# ProPrj_ZYNQ7020_V1_2024-12-31.net
KiCad netlist of a schematic drawn in EasyEDA Pro
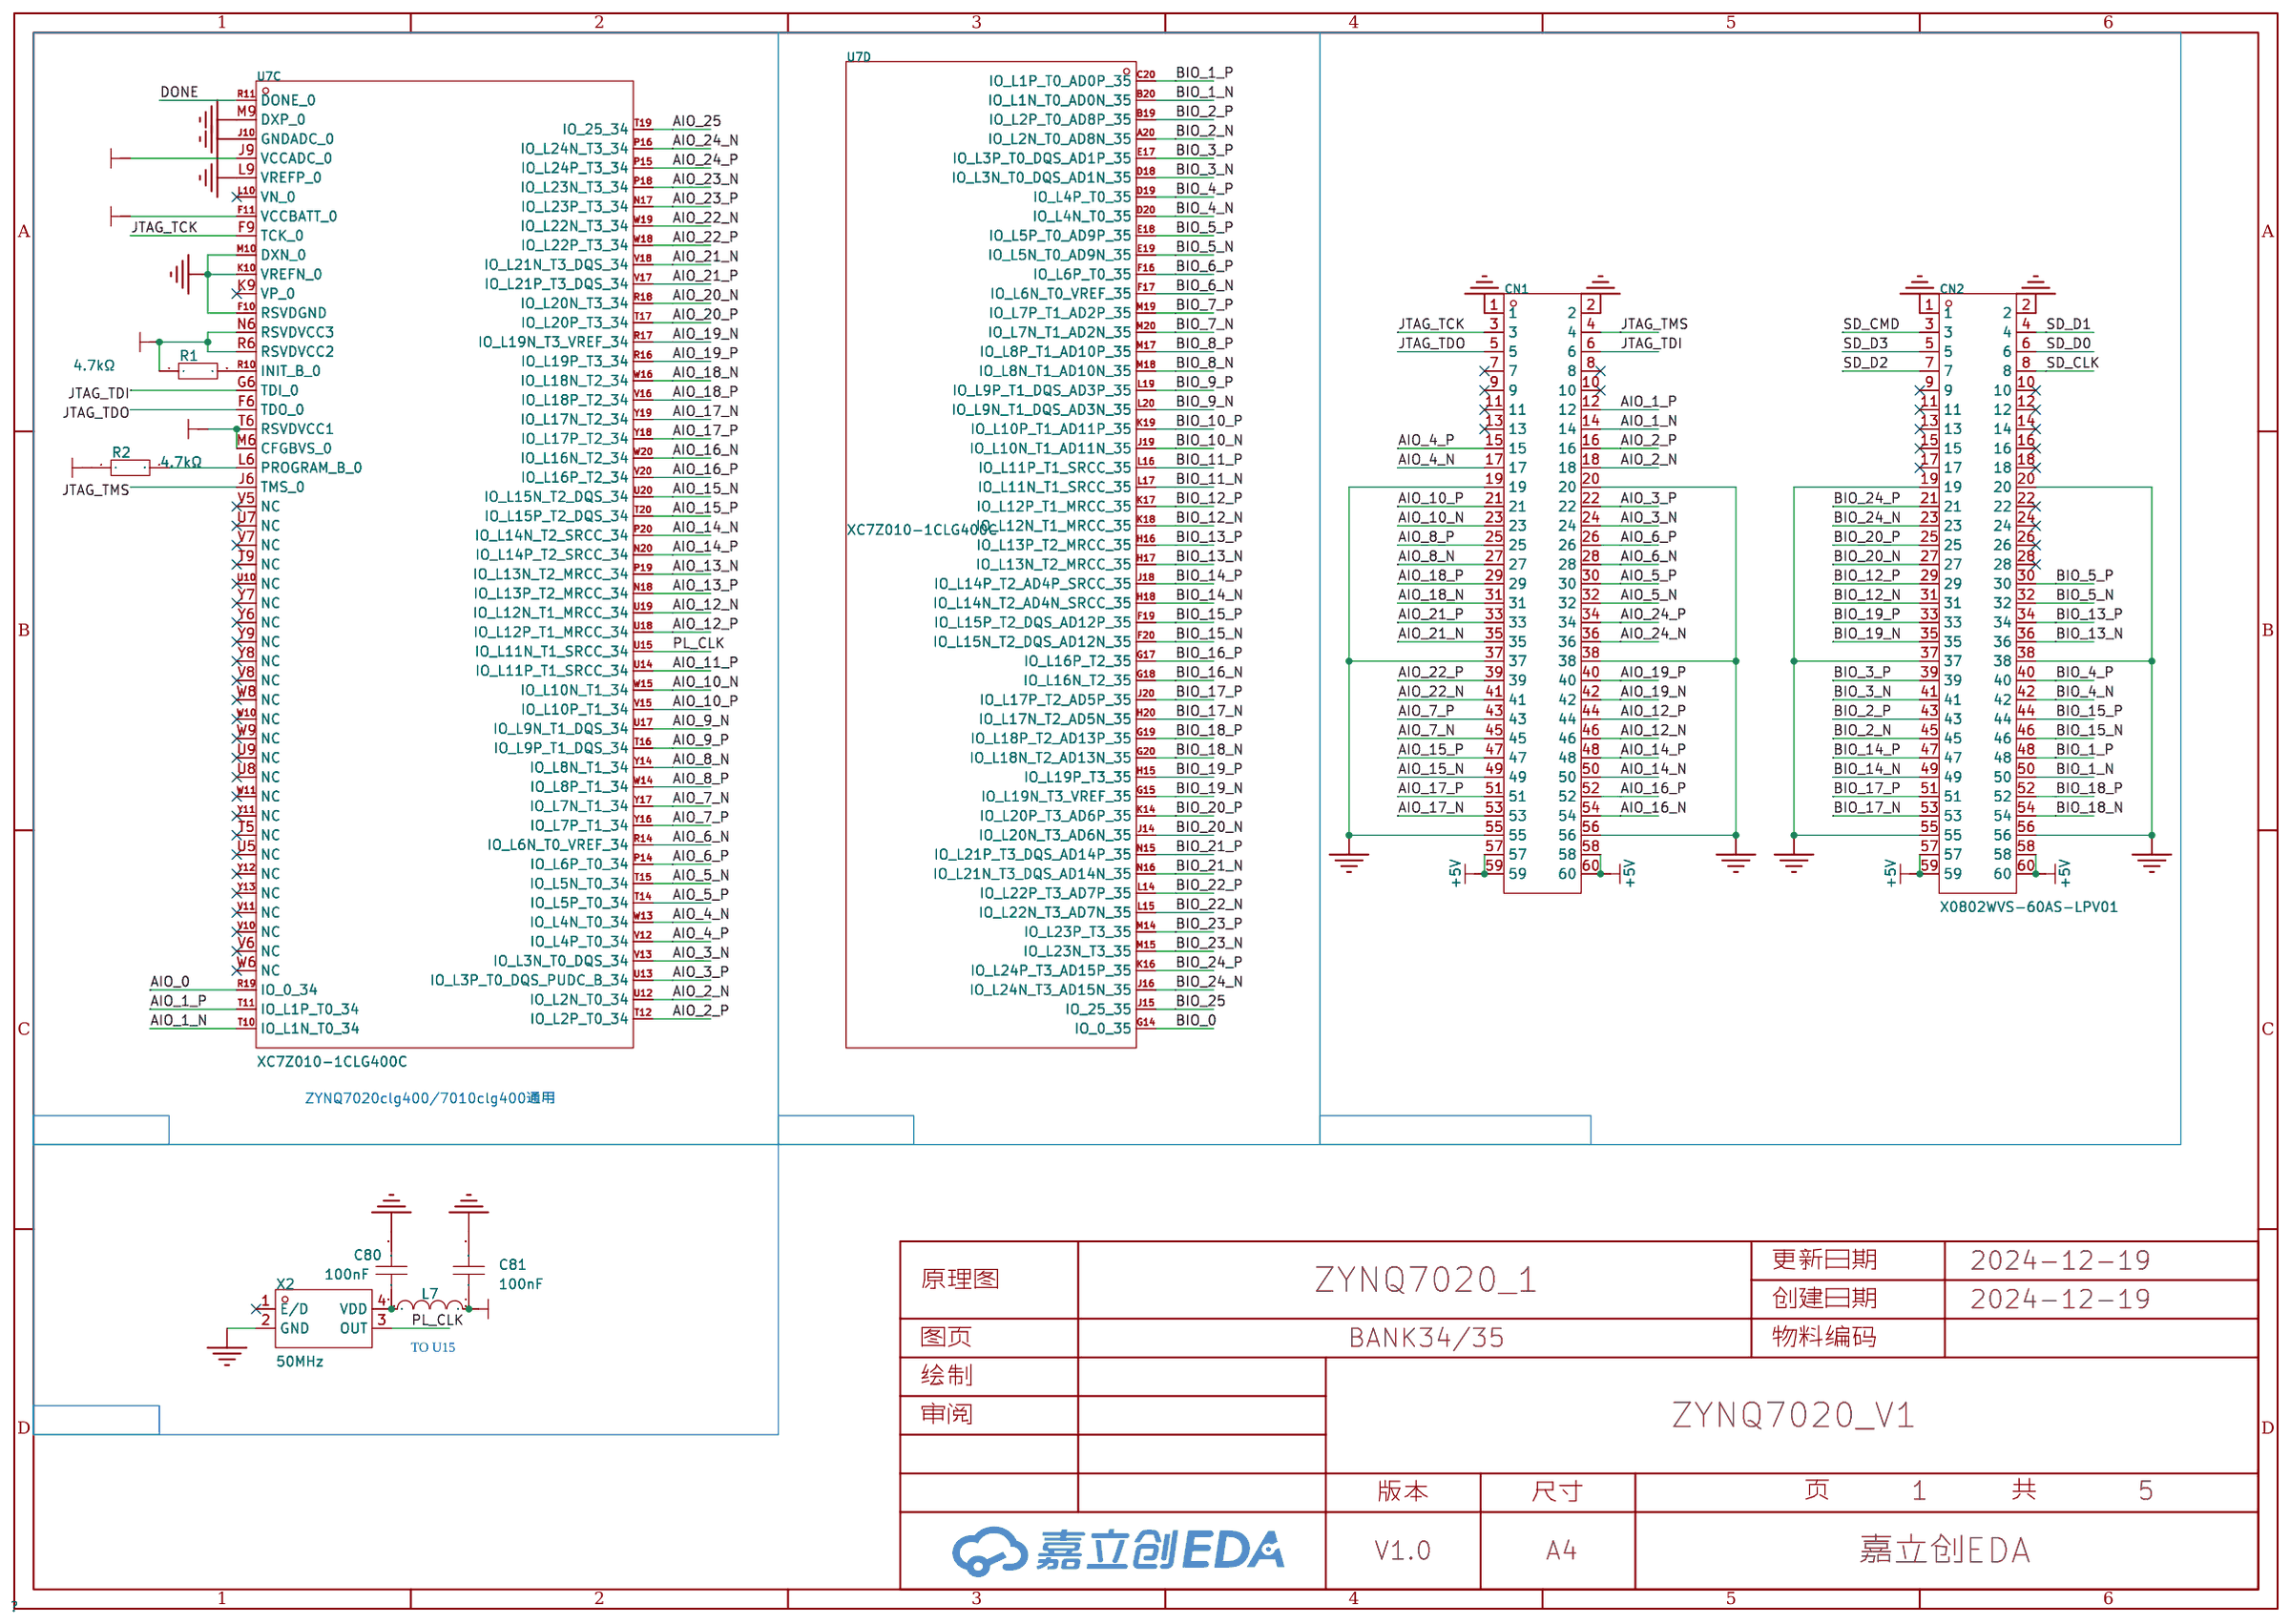
[diagram p0: BANK34/35]
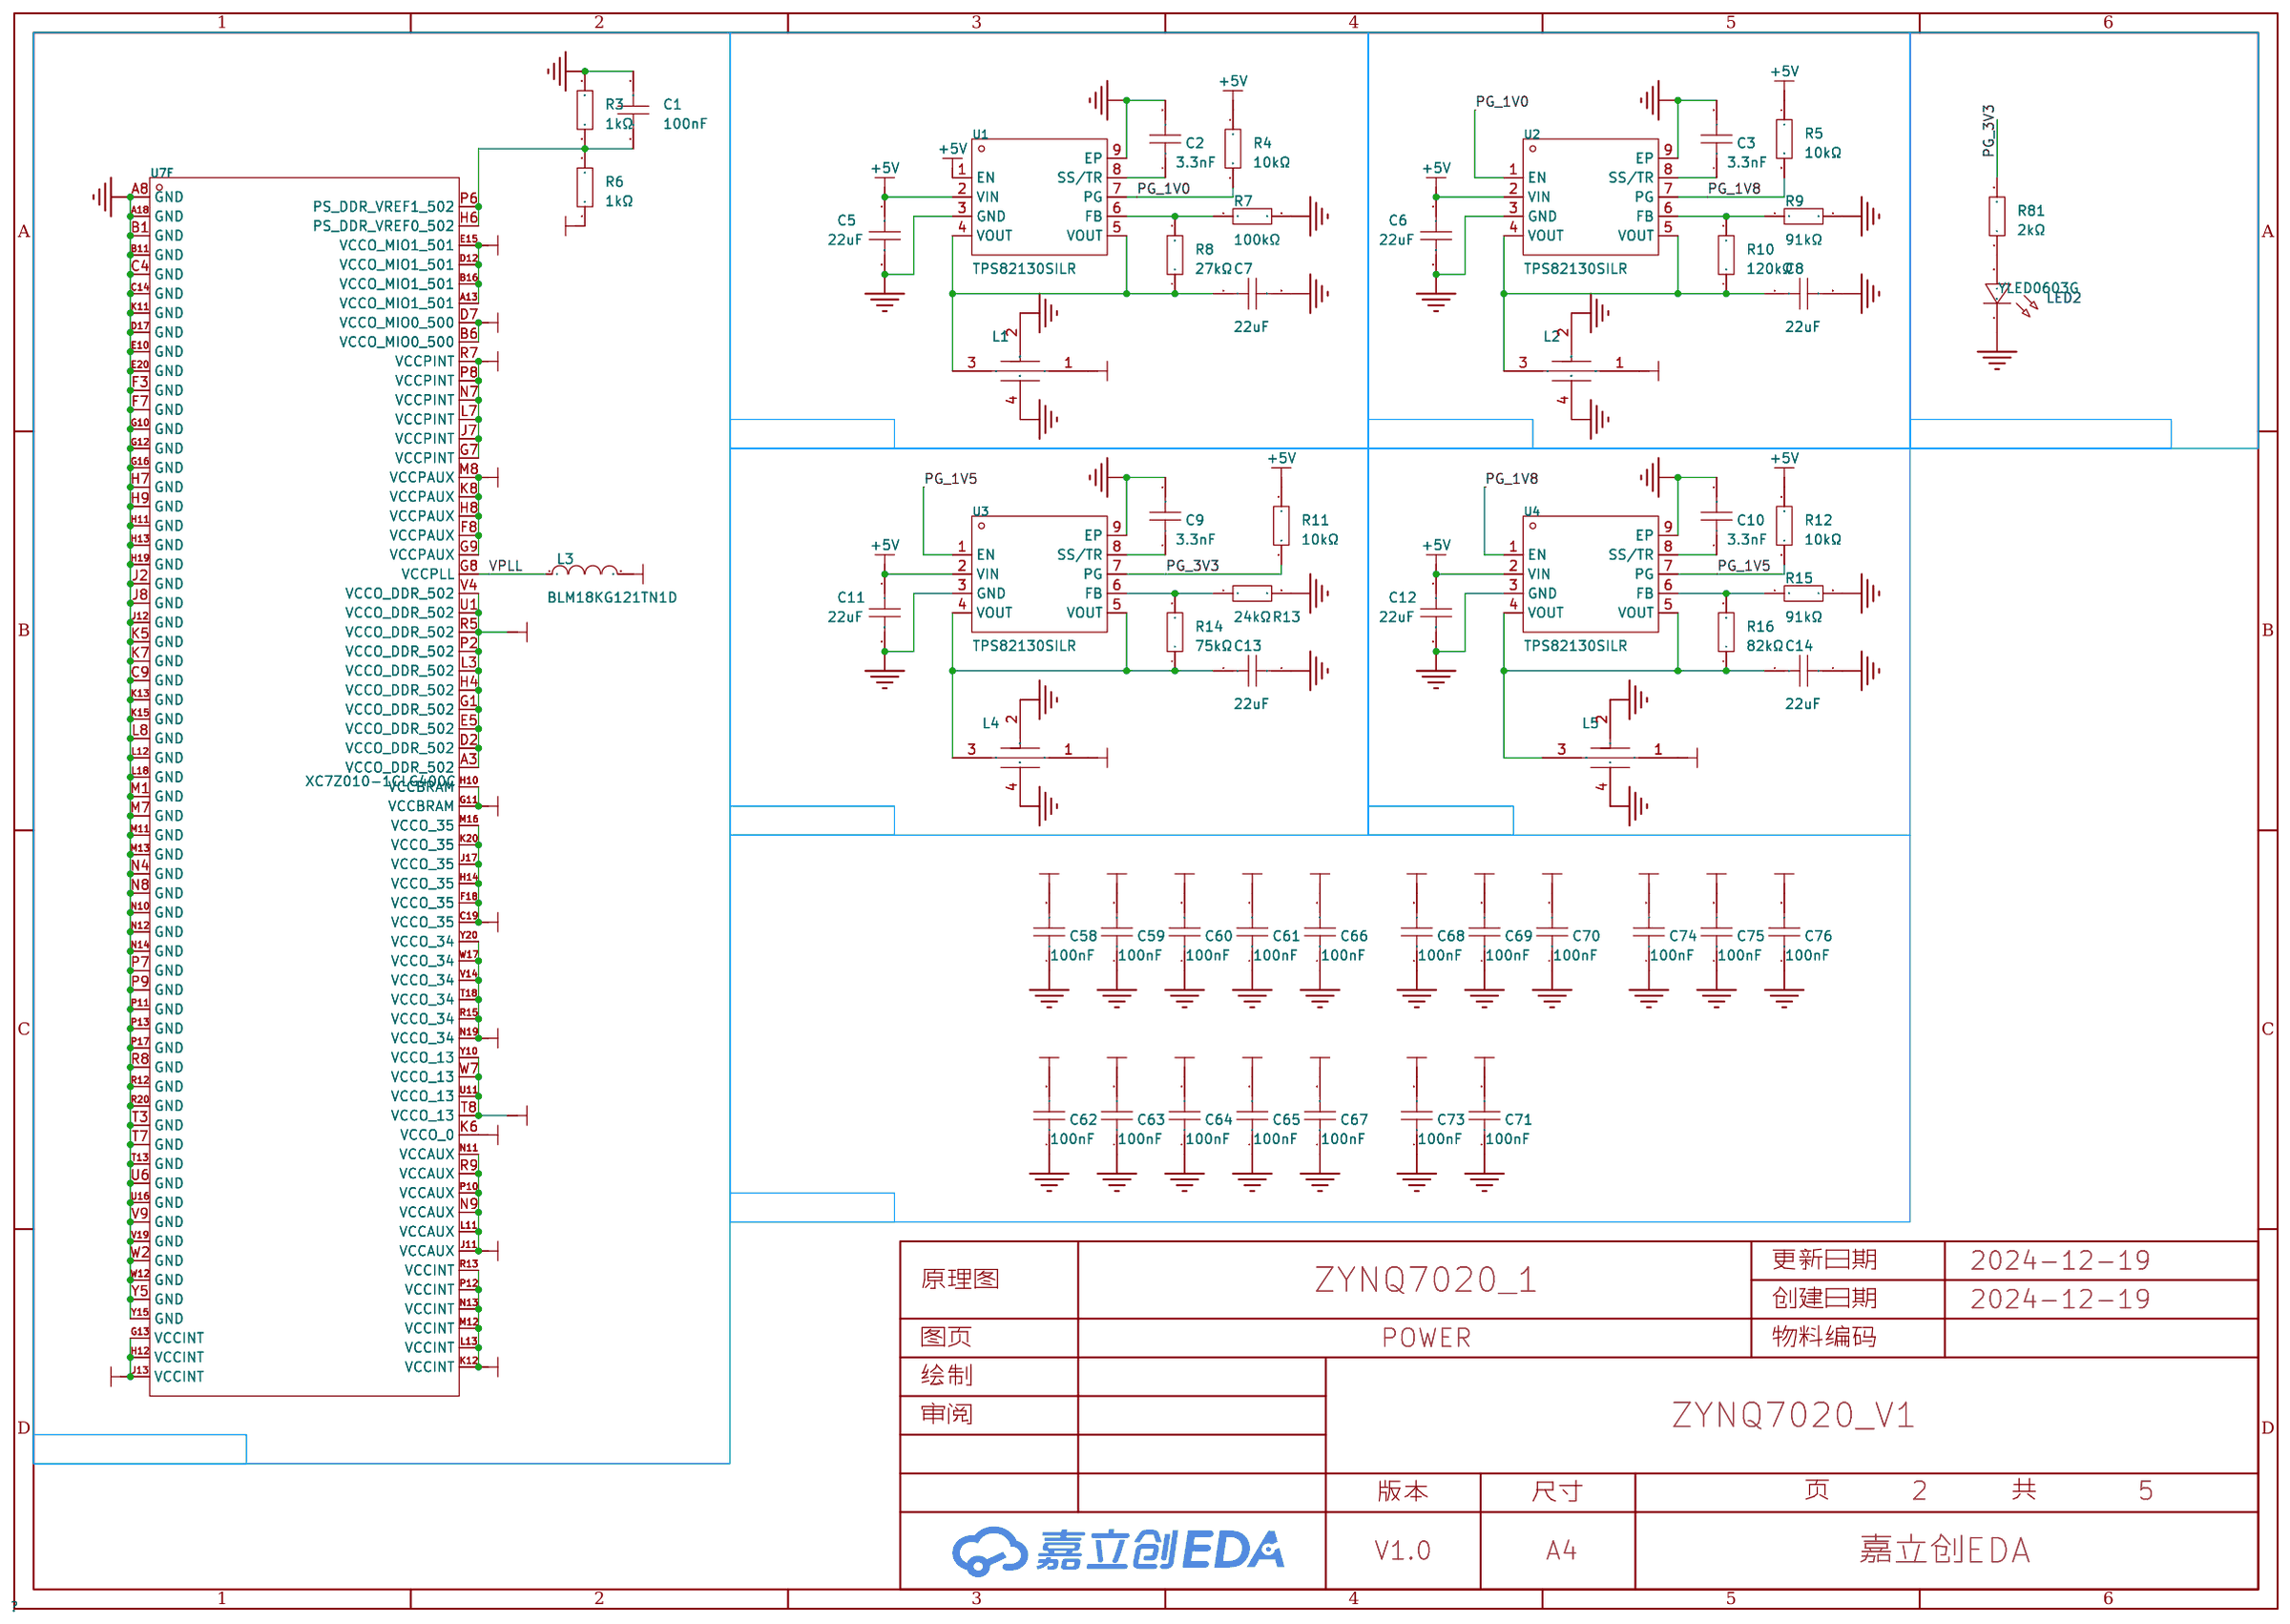
[diagram p1: POWER]
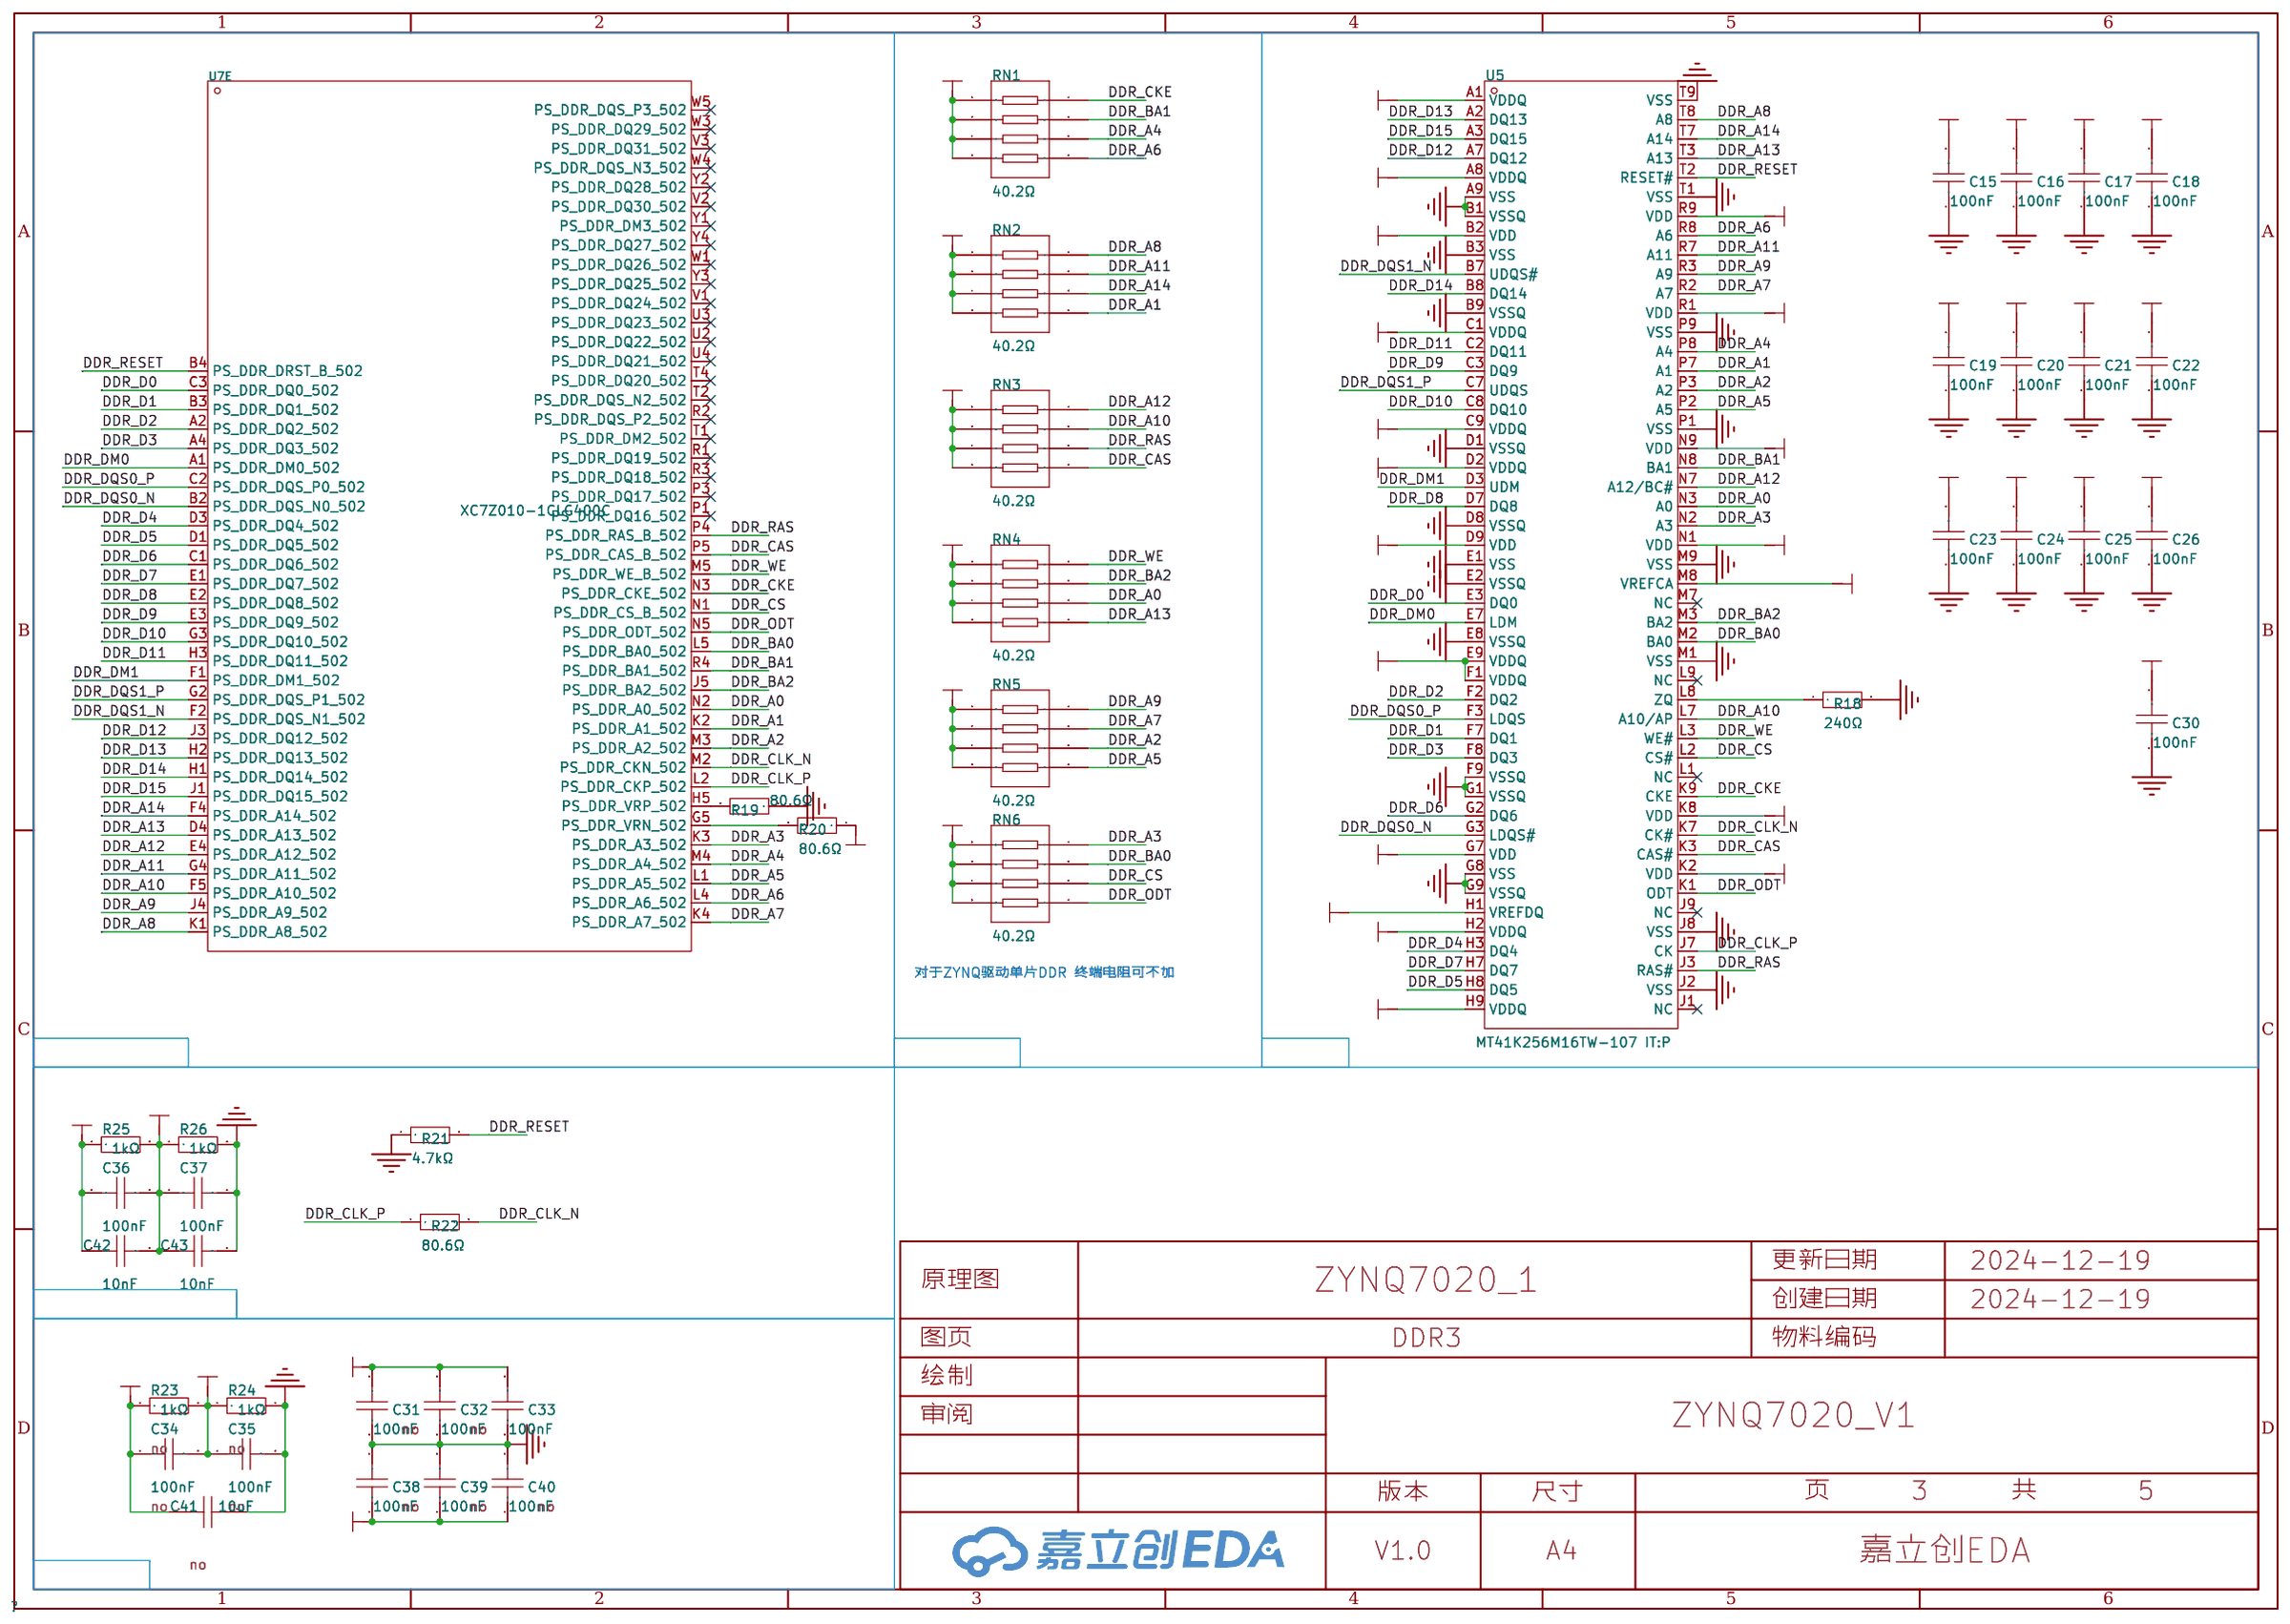
[diagram p2: DDR3]
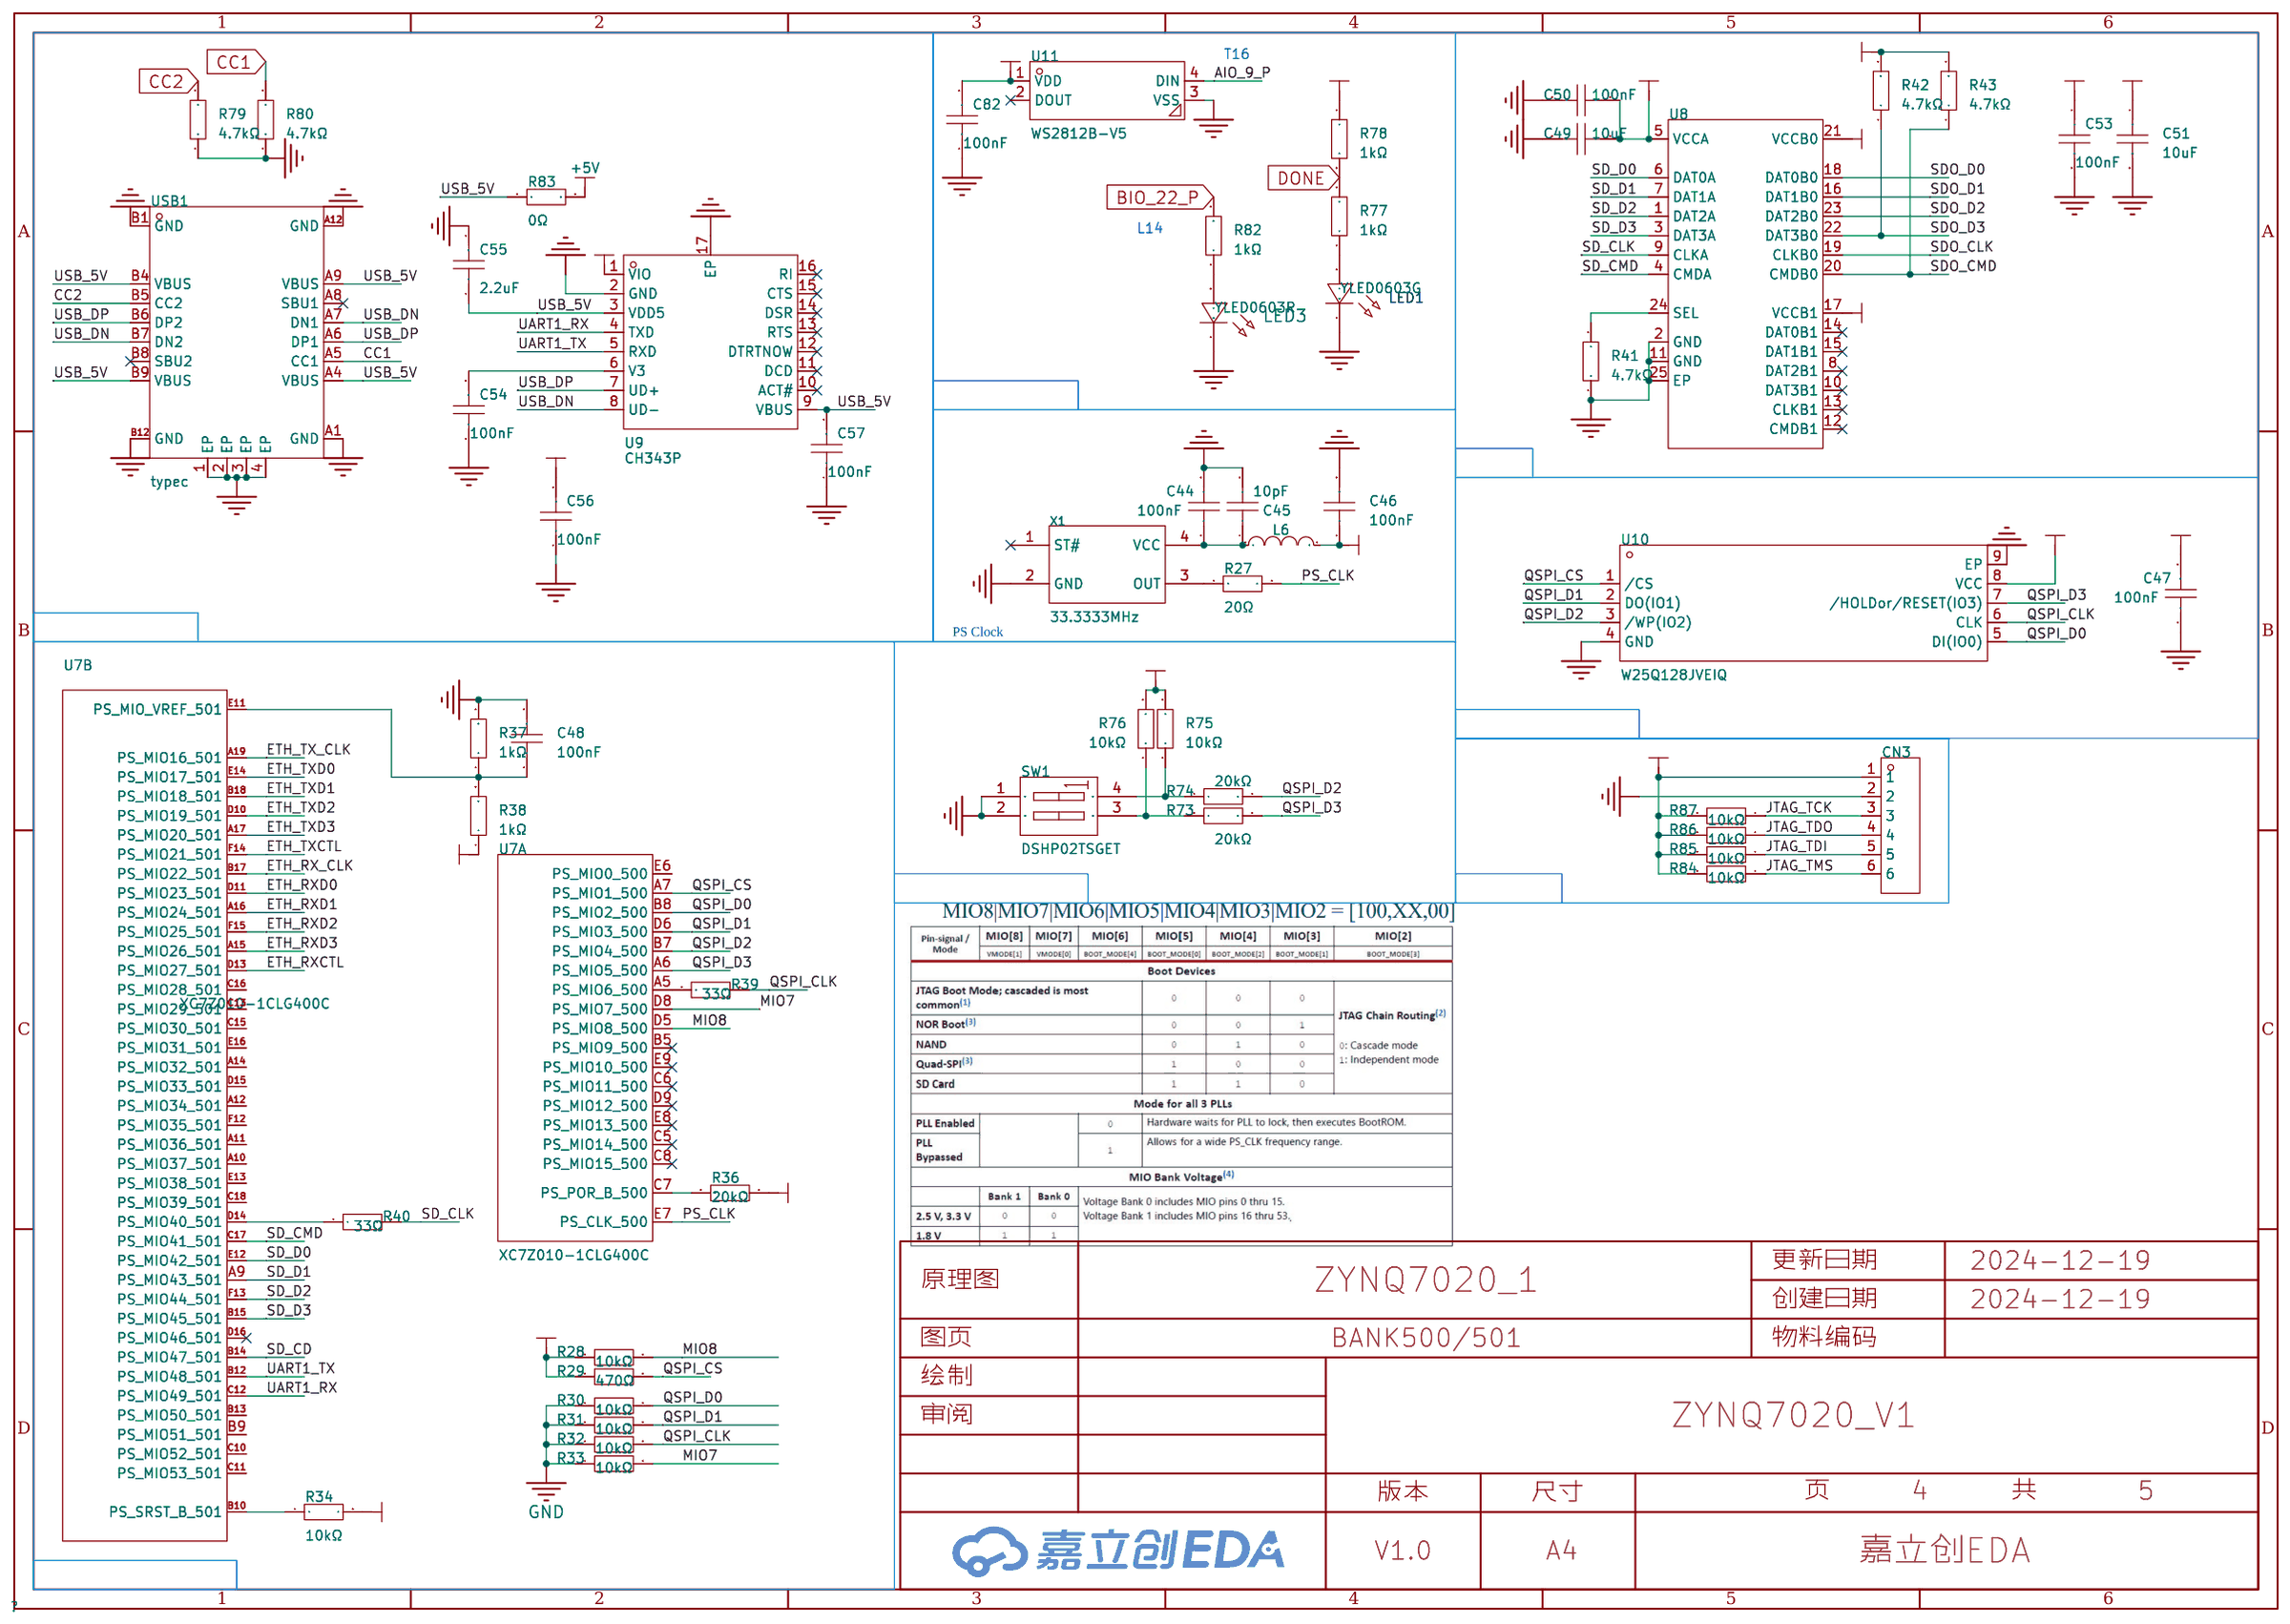
[diagram p3: BANK500/501]
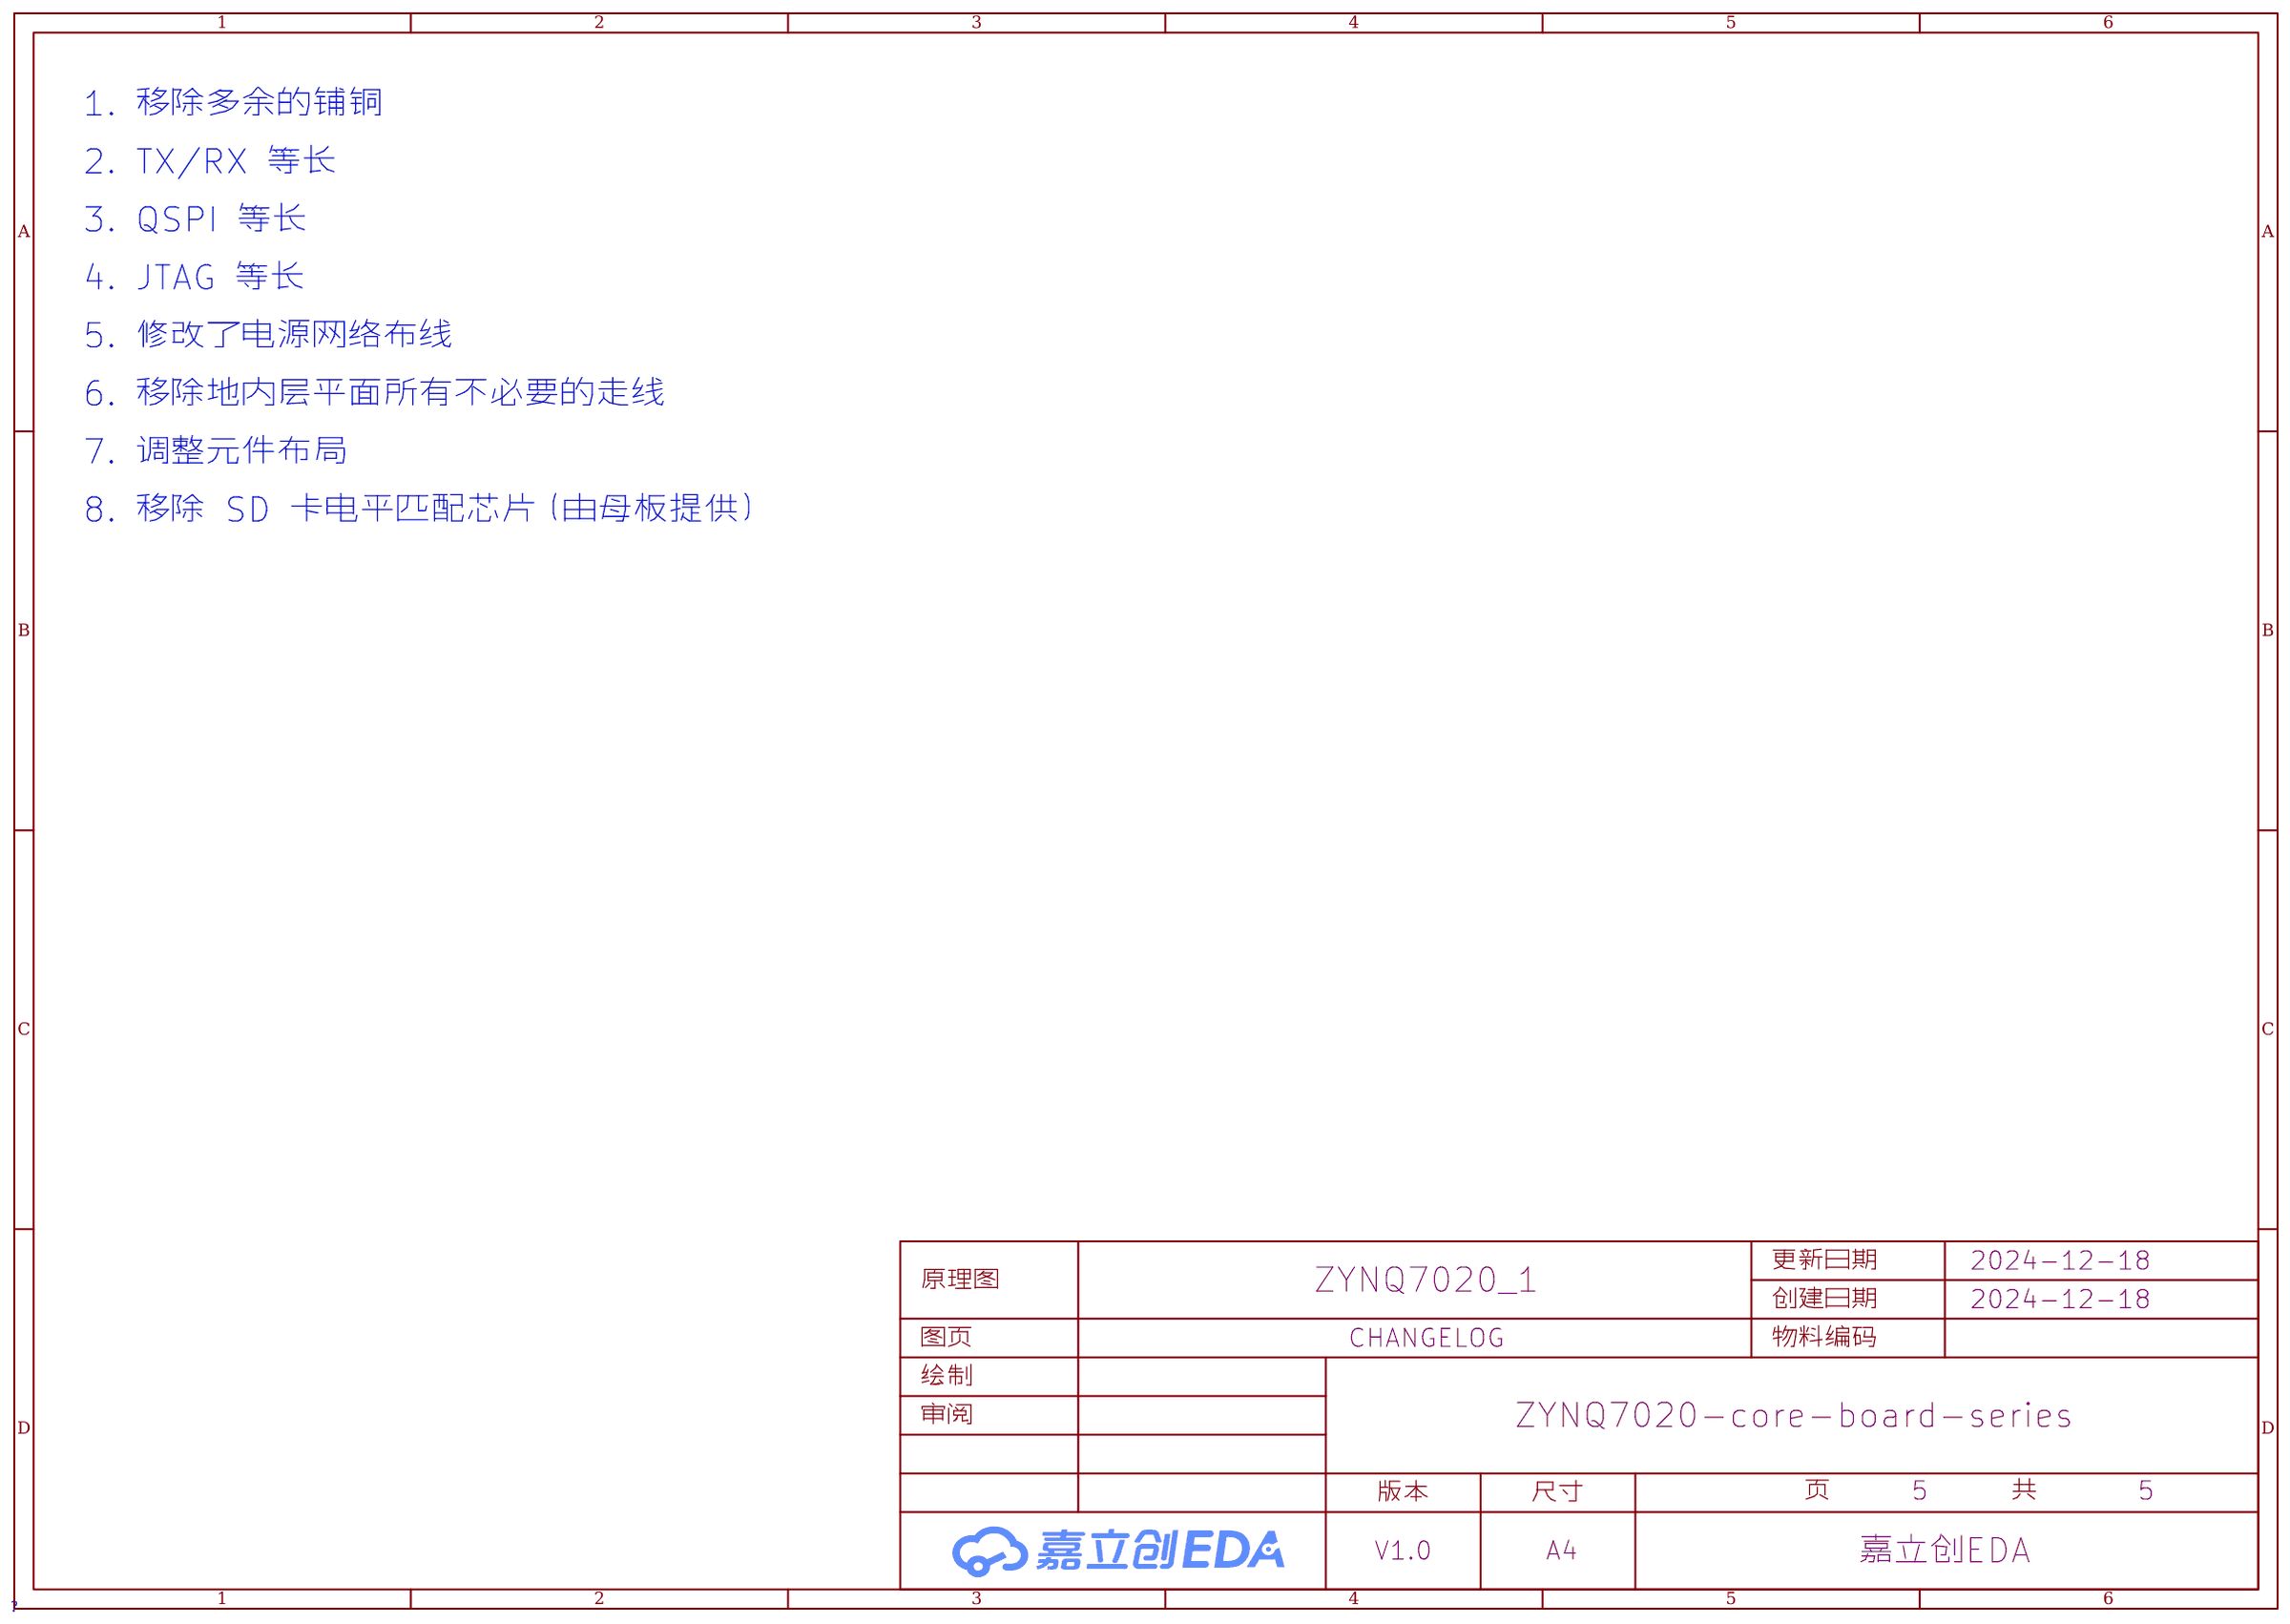
[diagram p4: CHANGELOG]

(export (version "E")
  (design (tool "Eeschema 10.0.6"))
  (components
    (comp (ref "C80")
      (value "100nF")
      (footprint "easyedapro:C0402")
      (fields
        (field (name "Manufacturer Part") "GRM155R71H104KE14D")
        (field (name "Manufacturer") "muRata(村田)")
      )
      (libsource (lib "easyedapro") (part "CapAcitance"))
    )
    (comp (ref "C81")
      (value "100nF")
      (footprint "easyedapro:C0402")
      (fields
        (field (name "Manufacturer Part") "GRM155R71H104KE14D")
        (field (name "Manufacturer") "muRata(村田)")
      )
      (libsource (lib "easyedapro") (part "CapAcitance"))
    )
    (comp (ref "CN1")
      (value "X0802WVS-60AS-LPV01")
      (footprint "easyedapro:CONN-SMD_60P-P0.80_XKB_X0802WVS-60ADS-LPV01")
      (description "PIN总数:60P;间距:0.8mm;公母:公;安装方式:立贴;行数:2;额定电流:500mA;工作温度范围:-25℃~+85℃;")
      (fields (field (name "Manufacturer") "XKB Connection(中国星坤)"))
      (libsource (lib "easyedapro") (part "X0802WVS-60ADS-LPV01"))
    )
    (comp (ref "CN2")
      (value "X0802WVS-60AS-LPV01")
      (footprint "easyedapro:CONN-SMD_60P-P0.80_XKB_X0802WVS-60ADS-LPV01")
      (description "PIN总数:60P;间距:0.8mm;公母:公;安装方式:立贴;行数:2;额定电流:500mA;工作温度范围:-25℃~+85℃;")
      (fields (field (name "Manufacturer") "XKB Connection(中国星坤)"))
      (libsource (lib "easyedapro") (part "X0802WVS-60ADS-LPV01"))
    )
    (comp (ref "L7")
      (value "BLM18KG121TN1D")
      (footprint "easyedapro:L0603")
      (fields (field (name "Manufacturer") "muRata(村田)"))
      (libsource (lib "easyedapro") (part "SDFL1608S100KTF"))
    )
    (comp (ref "R1")
      (value "4.7kΩ")
      (footprint "easyedapro:R0402")
      (fields
        (field (name "Manufacturer Part") "0402WGF4701TCE")
        (field (name "Manufacturer") "UNI-ROYAL(厚声)")
      )
      (libsource (lib "easyedapro") (part "电阻"))
    )
    (comp (ref "R2")
      (value "4.7kΩ")
      (footprint "easyedapro:R0402")
      (fields
        (field (name "Manufacturer Part") "0402WGF4701TCE")
        (field (name "Manufacturer") "UNI-ROYAL(厚声)")
      )
      (libsource (lib "easyedapro") (part "电阻"))
    )
    (comp (ref "U7")
      (value "XC7Z010-1CLG400C")
      (footprint "easyedapro:FBGA-400_L17.0-W17.0-R20-C20-P0.80-TL")
      (fields (field (name "Manufacturer") "XILINX(赛灵思)"))
      (libsource (lib "easyedapro") (part "XC7Z010-1CLG400C"))
    )
    (comp (ref "X2")
      (value "50MHz")
      (footprint "easyedapro:OSC-SMD_4P-L2.5-W2.0-BL")
      (description "频率:50MHz;工作电压:1.8V~3.3V;频率稳定度:±10ppm;")
      (fields (field (name "Manufacturer Part") "OT252050MJBA4SL") (field (name "Manufacturer") "YXC(扬兴晶振)"))
      (libsource (lib "easyedapro") (part "OT252050MJBA4SL"))
    )
    (comp (ref "C1")
      (value "100nF")
      (footprint "easyedapro:C0402")
      (fields
        (field (name "Manufacturer Part") "GRM155R71H104KE14D")
        (field (name "Manufacturer") "muRata(村田)")
      )
      (libsource (lib "easyedapro") (part "CapAcitance"))
    )
    (comp (ref "C2")
      (value "3.3nF")
      (footprint "easyedapro:C0402")
      (fields
        (field (name "Manufacturer Part") "CC0402KRX7R9BB332")
        (field (name "Manufacturer") "YAGEO(国巨)")
      )
      (libsource (lib "easyedapro") (part "CapAcitance"))
    )
    (comp (ref "C3")
      (value "3.3nF")
      (footprint "easyedapro:C0402")
      (fields
        (field (name "Manufacturer Part") "CC0402KRX7R9BB332")
        (field (name "Manufacturer") "YAGEO(国巨)")
      )
      (libsource (lib "easyedapro") (part "CapAcitance"))
    )
    (comp (ref "C5")
      (value "22uF")
      (footprint "easyedapro:C0402")
      (fields
        (field (name "Manufacturer Part") "CL21A226MAQNNNE")
        (field (name "Manufacturer") "SAMSUNG(三星)")
      )
      (libsource (lib "easyedapro") (part "CapAcitance"))
    )
    (comp (ref "C6")
      (value "22uF")
      (footprint "easyedapro:C0402")
      (fields
        (field (name "Manufacturer Part") "CL21A226MAQNNNE")
        (field (name "Manufacturer") "SAMSUNG(三星)")
      )
      (libsource (lib "easyedapro") (part "CapAcitance"))
    )
    (comp (ref "C7")
      (value "22uF")
      (footprint "easyedapro:C0402")
      (fields
        (field (name "Manufacturer Part") "CL21A226MAQNNNE")
        (field (name "Manufacturer") "SAMSUNG(三星)")
      )
      (libsource (lib "easyedapro") (part "CapAcitance"))
    )
    (comp (ref "C8")
      (value "22uF")
      (footprint "easyedapro:C0402")
      (fields
        (field (name "Manufacturer Part") "CL21A226MAQNNNE")
        (field (name "Manufacturer") "SAMSUNG(三星)")
      )
      (libsource (lib "easyedapro") (part "CapAcitance"))
    )
    (comp (ref "C9")
      (value "3.3nF")
      (footprint "easyedapro:C0402")
      (fields
        (field (name "Manufacturer Part") "CC0402KRX7R9BB332")
        (field (name "Manufacturer") "YAGEO(国巨)")
      )
      (libsource (lib "easyedapro") (part "CapAcitance"))
    )
    (comp (ref "C10")
      (value "3.3nF")
      (footprint "easyedapro:C0402")
      (fields
        (field (name "Manufacturer Part") "CC0402KRX7R9BB332")
        (field (name "Manufacturer") "YAGEO(国巨)")
      )
      (libsource (lib "easyedapro") (part "CapAcitance"))
    )
    (comp (ref "C11")
      (value "22uF")
      (footprint "easyedapro:C0402")
      (fields
        (field (name "Manufacturer Part") "CL21A226MAQNNNE")
        (field (name "Manufacturer") "SAMSUNG(三星)")
      )
      (libsource (lib "easyedapro") (part "CapAcitance"))
    )
    (comp (ref "C12")
      (value "22uF")
      (footprint "easyedapro:C0402")
      (fields
        (field (name "Manufacturer Part") "CL21A226MAQNNNE")
        (field (name "Manufacturer") "SAMSUNG(三星)")
      )
      (libsource (lib "easyedapro") (part "CapAcitance"))
    )
    (comp (ref "C13")
      (value "22uF")
      (footprint "easyedapro:C0402")
      (fields
        (field (name "Manufacturer Part") "CL21A226MAQNNNE")
        (field (name "Manufacturer") "SAMSUNG(三星)")
      )
      (libsource (lib "easyedapro") (part "CapAcitance"))
    )
    (comp (ref "C14")
      (value "22uF")
      (footprint "easyedapro:C0402")
      (fields
        (field (name "Manufacturer Part") "CL21A226MAQNNNE")
        (field (name "Manufacturer") "SAMSUNG(三星)")
      )
      (libsource (lib "easyedapro") (part "CapAcitance"))
    )
    (comp (ref "C58")
      (value "100nF")
      (footprint "easyedapro:C0402")
      (fields
        (field (name "Manufacturer Part") "GRM155R71H104KE14D")
        (field (name "Manufacturer") "muRata(村田)")
      )
      (libsource (lib "easyedapro") (part "CapAcitance"))
    )
    (comp (ref "C59")
      (value "100nF")
      (footprint "easyedapro:C0402")
      (fields
        (field (name "Manufacturer Part") "GRM155R71H104KE14D")
        (field (name "Manufacturer") "muRata(村田)")
      )
      (libsource (lib "easyedapro") (part "CapAcitance"))
    )
    (comp (ref "C60")
      (value "100nF")
      (footprint "easyedapro:C0402")
      (fields
        (field (name "Manufacturer Part") "GRM155R71H104KE14D")
        (field (name "Manufacturer") "muRata(村田)")
      )
      (libsource (lib "easyedapro") (part "CapAcitance"))
    )
    (comp (ref "C61")
      (value "100nF")
      (footprint "easyedapro:C0402")
      (fields
        (field (name "Manufacturer Part") "GRM155R71H104KE14D")
        (field (name "Manufacturer") "muRata(村田)")
      )
      (libsource (lib "easyedapro") (part "CapAcitance"))
    )
    (comp (ref "C62")
      (value "100nF")
      (footprint "easyedapro:C0402")
      (fields
        (field (name "Manufacturer Part") "GRM155R71H104KE14D")
        (field (name "Manufacturer") "muRata(村田)")
      )
      (libsource (lib "easyedapro") (part "CapAcitance"))
    )
    (comp (ref "C63")
      (value "100nF")
      (footprint "easyedapro:C0402")
      (fields
        (field (name "Manufacturer Part") "GRM155R71H104KE14D")
        (field (name "Manufacturer") "muRata(村田)")
      )
      (libsource (lib "easyedapro") (part "CapAcitance"))
    )
    (comp (ref "C64")
      (value "100nF")
      (footprint "easyedapro:C0402")
      (fields
        (field (name "Manufacturer Part") "GRM155R71H104KE14D")
        (field (name "Manufacturer") "muRata(村田)")
      )
      (libsource (lib "easyedapro") (part "CapAcitance"))
    )
    (comp (ref "C65")
      (value "100nF")
      (footprint "easyedapro:C0402")
      (fields
        (field (name "Manufacturer Part") "GRM155R71H104KE14D")
        (field (name "Manufacturer") "muRata(村田)")
      )
      (libsource (lib "easyedapro") (part "CapAcitance"))
    )
    (comp (ref "C66")
      (value "100nF")
      (footprint "easyedapro:C0402")
      (fields
        (field (name "Manufacturer Part") "GRM155R71H104KE14D")
        (field (name "Manufacturer") "muRata(村田)")
      )
      (libsource (lib "easyedapro") (part "CapAcitance"))
    )
    (comp (ref "C67")
      (value "100nF")
      (footprint "easyedapro:C0402")
      (fields
        (field (name "Manufacturer Part") "GRM155R71H104KE14D")
        (field (name "Manufacturer") "muRata(村田)")
      )
      (libsource (lib "easyedapro") (part "CapAcitance"))
    )
    (comp (ref "C68")
      (value "100nF")
      (footprint "easyedapro:C0402")
      (fields
        (field (name "Manufacturer Part") "GRM155R71H104KE14D")
        (field (name "Manufacturer") "muRata(村田)")
      )
      (libsource (lib "easyedapro") (part "CapAcitance"))
    )
    (comp (ref "C69")
      (value "100nF")
      (footprint "easyedapro:C0402")
      (fields
        (field (name "Manufacturer Part") "GRM155R71H104KE14D")
        (field (name "Manufacturer") "muRata(村田)")
      )
      (libsource (lib "easyedapro") (part "CapAcitance"))
    )
    (comp (ref "C70")
      (value "100nF")
      (footprint "easyedapro:C0402")
      (fields
        (field (name "Manufacturer Part") "GRM155R71H104KE14D")
        (field (name "Manufacturer") "muRata(村田)")
      )
      (libsource (lib "easyedapro") (part "CapAcitance"))
    )
    (comp (ref "C71")
      (value "100nF")
      (footprint "easyedapro:C0402")
      (fields
        (field (name "Manufacturer Part") "GRM155R71H104KE14D")
        (field (name "Manufacturer") "muRata(村田)")
      )
      (libsource (lib "easyedapro") (part "CapAcitance"))
    )
    (comp (ref "C73")
      (value "100nF")
      (footprint "easyedapro:C0402")
      (fields
        (field (name "Manufacturer Part") "GRM155R71H104KE14D")
        (field (name "Manufacturer") "muRata(村田)")
      )
      (libsource (lib "easyedapro") (part "CapAcitance"))
    )
    (comp (ref "C74")
      (value "100nF")
      (footprint "easyedapro:C0402")
      (fields
        (field (name "Manufacturer Part") "GRM155R71H104KE14D")
        (field (name "Manufacturer") "muRata(村田)")
      )
      (libsource (lib "easyedapro") (part "CapAcitance"))
    )
    (comp (ref "C75")
      (value "100nF")
      (footprint "easyedapro:C0402")
      (fields
        (field (name "Manufacturer Part") "GRM155R71H104KE14D")
        (field (name "Manufacturer") "muRata(村田)")
      )
      (libsource (lib "easyedapro") (part "CapAcitance"))
    )
    (comp (ref "C76")
      (value "100nF")
      (footprint "easyedapro:C0402")
      (fields
        (field (name "Manufacturer Part") "GRM155R71H104KE14D")
        (field (name "Manufacturer") "muRata(村田)")
      )
      (libsource (lib "easyedapro") (part "CapAcitance"))
    )
    (comp (ref "L1")
      (value "NFM21PC104R1E3D")
      (footprint "easyedapro:CAP-SMD_4P-L2.0-W1.25")
      (description "电容量:100nF;精度:±20%;直流电阻:30mΩ;")
      (fields (field (name "Manufacturer") "muRata(村田)"))
      (libsource (lib "easyedapro") (part "NFM21PC104R1E3D"))
    )
    (comp (ref "L2")
      (value "NFM21PC104R1E3D")
      (footprint "easyedapro:CAP-SMD_4P-L2.0-W1.25")
      (description "电容量:100nF;精度:±20%;直流电阻:30mΩ;")
      (fields (field (name "Manufacturer") "muRata(村田)"))
      (libsource (lib "easyedapro") (part "NFM21PC104R1E3D"))
    )
    (comp (ref "L3")
      (value "BLM18KG121TN1D")
      (footprint "easyedapro:L0603")
      (fields (field (name "Manufacturer") "muRata(村田)"))
      (libsource (lib "easyedapro") (part "SDFL1608S100KTF"))
    )
    (comp (ref "L4")
      (value "NFM21PC104R1E3D")
      (footprint "easyedapro:CAP-SMD_4P-L2.0-W1.25")
      (description "电容量:100nF;精度:±20%;直流电阻:30mΩ;")
      (fields (field (name "Manufacturer") "muRata(村田)"))
      (libsource (lib "easyedapro") (part "NFM21PC104R1E3D"))
    )
    (comp (ref "L5")
      (value "NFM21PC104R1E3D")
      (footprint "easyedapro:CAP-SMD_4P-L2.0-W1.25")
      (description "电容量:100nF;精度:±20%;直流电阻:30mΩ;")
      (fields (field (name "Manufacturer") "muRata(村田)"))
      (libsource (lib "easyedapro") (part "NFM21PC104R1E3D"))
    )
    (comp (ref "LED2")
      (value "YLED0603G")
      (footprint "easyedapro:LED_0603")
      (fields (field (name "Manufacturer") "YONGYUTAI(永裕泰)"))
      (libsource (lib "easyedapro") (part "LED_G"))
    )
    (comp (ref "R3")
      (value "1kΩ")
      (footprint "easyedapro:R0402")
      (fields
        (field (name "Manufacturer Part") "0402WGF1001TCE")
        (field (name "Manufacturer") "UNI-ROYAL(厚声)")
      )
      (libsource (lib "easyedapro") (part "电阻"))
    )
    (comp (ref "R4")
      (value "10kΩ")
      (footprint "easyedapro:R0402")
      (fields
        (field (name "Manufacturer Part") "0402WGF1002TCE")
        (field (name "Manufacturer") "UNI-ROYAL(厚声)")
      )
      (libsource (lib "easyedapro") (part "电阻"))
    )
    (comp (ref "R5")
      (value "10kΩ")
      (footprint "easyedapro:R0402")
      (fields
        (field (name "Manufacturer Part") "0402WGF1002TCE")
        (field (name "Manufacturer") "UNI-ROYAL(厚声)")
      )
      (libsource (lib "easyedapro") (part "电阻"))
    )
    (comp (ref "R6")
      (value "1kΩ")
      (footprint "easyedapro:R0402")
      (fields
        (field (name "Manufacturer Part") "0402WGF1001TCE")
        (field (name "Manufacturer") "UNI-ROYAL(厚声)")
      )
      (libsource (lib "easyedapro") (part "电阻"))
    )
    (comp (ref "R7")
      (value "100kΩ")
      (footprint "easyedapro:R0402")
      (fields (field (name "Manufacturer Part") "RC0402FR-07100KL") (field (name "Manufacturer") "YAGEO(国巨)"))
      (libsource (lib "easyedapro") (part "电阻"))
    )
    (comp (ref "R8")
      (value "27kΩ")
      (footprint "easyedapro:R0402")
      (fields
        (field (name "Manufacturer Part") "0402WGF2702TCE")
        (field (name "Manufacturer") "UNI-ROYAL(厚声)")
      )
      (libsource (lib "easyedapro") (part "电阻"))
    )
    (comp (ref "R9")
      (value "91kΩ")
      (footprint "easyedapro:R0402")
      (fields
        (field (name "Manufacturer Part") "0402WGF9102TCE")
        (field (name "Manufacturer") "UNI-ROYAL(厚声)")
      )
      (libsource (lib "easyedapro") (part "电阻"))
    )
    (comp (ref "R10")
      (value "120kΩ")
      (footprint "easyedapro:R0402")
      (fields
        (field (name "Manufacturer Part") "0402WGF1203TCE")
        (field (name "Manufacturer") "UNI-ROYAL(厚声)")
      )
      (libsource (lib "easyedapro") (part "电阻"))
    )
    (comp (ref "R11")
      (value "10kΩ")
      (footprint "easyedapro:R0402")
      (fields
        (field (name "Manufacturer Part") "0402WGF1002TCE")
        (field (name "Manufacturer") "UNI-ROYAL(厚声)")
      )
      (libsource (lib "easyedapro") (part "电阻"))
    )
    (comp (ref "R12")
      (value "10kΩ")
      (footprint "easyedapro:R0402")
      (fields
        (field (name "Manufacturer Part") "0402WGF1002TCE")
        (field (name "Manufacturer") "UNI-ROYAL(厚声)")
      )
      (libsource (lib "easyedapro") (part "电阻"))
    )
    (comp (ref "R13")
      (value "24kΩ")
      (footprint "easyedapro:R0402")
      (fields
        (field (name "Manufacturer Part") "0402WGF2402TCE")
        (field (name "Manufacturer") "UNI-ROYAL(厚声)")
      )
      (libsource (lib "easyedapro") (part "电阻"))
    )
    (comp (ref "R14")
      (value "75kΩ")
      (footprint "easyedapro:R0402")
      (fields
        (field (name "Manufacturer Part") "0402WGF7502TCE")
        (field (name "Manufacturer") "UNI-ROYAL(厚声)")
      )
      (libsource (lib "easyedapro") (part "电阻"))
    )
    (comp (ref "R15")
      (value "91kΩ")
      (footprint "easyedapro:R0402")
      (fields
        (field (name "Manufacturer Part") "0402WGF9102TCE")
        (field (name "Manufacturer") "UNI-ROYAL(厚声)")
      )
      (libsource (lib "easyedapro") (part "电阻"))
    )
    (comp (ref "R16")
      (value "82kΩ")
      (footprint "easyedapro:R0402")
      (fields (field (name "Manufacturer Part") "RC0402FR-0782KL") (field (name "Manufacturer") "YAGEO(国巨)"))
      (libsource (lib "easyedapro") (part "电阻"))
    )
    (comp (ref "R81")
      (value "2kΩ")
      (footprint "easyedapro:R0402")
      (fields
        (field (name "Manufacturer Part") "0402WGF2001TCE")
        (field (name "Manufacturer") "UNI-ROYAL(厚声)")
      )
      (libsource (lib "easyedapro") (part "电阻"))
    )
    (comp (ref "U1")
      (value "TPS82130SILR")
      (footprint "easyedapro:USIP-8_L3.0-W2.8-P0.65-TL-EP")
      (description "输入电压(DC):3V~17V;输出电压:900mV~6V;输出电流(最大值):3A;")
      (fields (field (name "Manufacturer") "TI(德州仪器)"))
      (libsource (lib "easyedapro") (part "TPS82130SILR"))
    )
    (comp (ref "U2")
      (value "TPS82130SILR")
      (footprint "easyedapro:USIP-8_L3.0-W2.8-P0.65-TL-EP")
      (description "输入电压(DC):3V~17V;输出电压:900mV~6V;输出电流(最大值):3A;")
      (fields (field (name "Manufacturer") "TI(德州仪器)"))
      (libsource (lib "easyedapro") (part "TPS82130SILR"))
    )
    (comp (ref "U3")
      (value "TPS82130SILR")
      (footprint "easyedapro:USIP-8_L3.0-W2.8-P0.65-TL-EP")
      (description "输入电压(DC):3V~17V;输出电压:900mV~6V;输出电流(最大值):3A;")
      (fields (field (name "Manufacturer") "TI(德州仪器)"))
      (libsource (lib "easyedapro") (part "TPS82130SILR"))
    )
    (comp (ref "U4")
      (value "TPS82130SILR")
      (footprint "easyedapro:USIP-8_L3.0-W2.8-P0.65-TL-EP")
      (description "输入电压(DC):3V~17V;输出电压:900mV~6V;输出电流(最大值):3A;")
      (fields (field (name "Manufacturer") "TI(德州仪器)"))
      (libsource (lib "easyedapro") (part "TPS82130SILR"))
    )
    (comp (ref "C15")
      (value "100nF")
      (footprint "easyedapro:C0402")
      (fields
        (field (name "Manufacturer Part") "GRM155R71H104KE14D")
        (field (name "Manufacturer") "muRata(村田)")
      )
      (libsource (lib "easyedapro") (part "CapAcitance"))
    )
    (comp (ref "C16")
      (value "100nF")
      (footprint "easyedapro:C0402")
      (fields
        (field (name "Manufacturer Part") "GRM155R71H104KE14D")
        (field (name "Manufacturer") "muRata(村田)")
      )
      (libsource (lib "easyedapro") (part "CapAcitance"))
    )
    (comp (ref "C17")
      (value "100nF")
      (footprint "easyedapro:C0402")
      (fields
        (field (name "Manufacturer Part") "GRM155R71H104KE14D")
        (field (name "Manufacturer") "muRata(村田)")
      )
      (libsource (lib "easyedapro") (part "CapAcitance"))
    )
    (comp (ref "C18")
      (value "100nF")
      (footprint "easyedapro:C0402")
      (fields
        (field (name "Manufacturer Part") "GRM155R71H104KE14D")
        (field (name "Manufacturer") "muRata(村田)")
      )
      (libsource (lib "easyedapro") (part "CapAcitance"))
    )
    (comp (ref "C19")
      (value "100nF")
      (footprint "easyedapro:C0402")
      (fields
        (field (name "Manufacturer Part") "GRM155R71H104KE14D")
        (field (name "Manufacturer") "muRata(村田)")
      )
      (libsource (lib "easyedapro") (part "CapAcitance"))
    )
    (comp (ref "C20")
      (value "100nF")
      (footprint "easyedapro:C0402")
      (fields
        (field (name "Manufacturer Part") "GRM155R71H104KE14D")
        (field (name "Manufacturer") "muRata(村田)")
      )
      (libsource (lib "easyedapro") (part "CapAcitance"))
    )
    (comp (ref "C21")
      (value "100nF")
      (footprint "easyedapro:C0402")
      (fields
        (field (name "Manufacturer Part") "GRM155R71H104KE14D")
        (field (name "Manufacturer") "muRata(村田)")
      )
      (libsource (lib "easyedapro") (part "CapAcitance"))
    )
    (comp (ref "C22")
      (value "100nF")
      (footprint "easyedapro:C0402")
      (fields
        (field (name "Manufacturer Part") "GRM155R71H104KE14D")
        (field (name "Manufacturer") "muRata(村田)")
      )
      (libsource (lib "easyedapro") (part "CapAcitance"))
    )
    (comp (ref "C23")
      (value "100nF")
      (footprint "easyedapro:C0402")
      (fields
        (field (name "Manufacturer Part") "GRM155R71H104KE14D")
        (field (name "Manufacturer") "muRata(村田)")
      )
      (libsource (lib "easyedapro") (part "CapAcitance"))
    )
    (comp (ref "C24")
      (value "100nF")
      (footprint "easyedapro:C0402")
      (fields
        (field (name "Manufacturer Part") "GRM155R71H104KE14D")
        (field (name "Manufacturer") "muRata(村田)")
      )
      (libsource (lib "easyedapro") (part "CapAcitance"))
    )
    (comp (ref "C25")
      (value "100nF")
      (footprint "easyedapro:C0402")
      (fields
        (field (name "Manufacturer Part") "GRM155R71H104KE14D")
        (field (name "Manufacturer") "muRata(村田)")
      )
      (libsource (lib "easyedapro") (part "CapAcitance"))
    )
    (comp (ref "C26")
      (value "100nF")
      (footprint "easyedapro:C0402")
      (fields
        (field (name "Manufacturer Part") "GRM155R71H104KE14D")
        (field (name "Manufacturer") "muRata(村田)")
      )
      (libsource (lib "easyedapro") (part "CapAcitance"))
    )
    (comp (ref "C30")
      (value "100nF")
      (footprint "easyedapro:C0402")
      (fields
        (field (name "Manufacturer Part") "GRM155R71H104KE14D")
        (field (name "Manufacturer") "muRata(村田)")
      )
      (libsource (lib "easyedapro") (part "CapAcitance"))
    )
    (comp (ref "C31")
      (value "100nF")
      (footprint "easyedapro:C0402")
      (fields
        (field (name "Manufacturer Part") "GRM155R71H104KE14D")
        (field (name "Manufacturer") "muRata(村田)")
        (field (name "Convert to PCB") "no")
      )
      (libsource (lib "easyedapro") (part "CapAcitance"))
    )
    (comp (ref "C32")
      (value "100nF")
      (footprint "easyedapro:C0402")
      (fields
        (field (name "Manufacturer Part") "GRM155R71H104KE14D")
        (field (name "Manufacturer") "muRata(村田)")
        (field (name "Convert to PCB") "no")
      )
      (libsource (lib "easyedapro") (part "CapAcitance"))
    )
    (comp (ref "C33")
      (value "100nF")
      (footprint "easyedapro:C0402")
      (fields
        (field (name "Manufacturer Part") "GRM155R71H104KE14D")
        (field (name "Manufacturer") "muRata(村田)")
      )
      (libsource (lib "easyedapro") (part "CapAcitance"))
    )
    (comp (ref "C34")
      (value "100nF")
      (footprint "easyedapro:C0402")
      (fields
        (field (name "Manufacturer Part") "GRM155R71H104KE14D")
        (field (name "Manufacturer") "muRata(村田)")
        (field (name "Convert to PCB") "no")
      )
      (libsource (lib "easyedapro") (part "CapAcitance"))
    )
    (comp (ref "C35")
      (value "100nF")
      (footprint "easyedapro:C0402")
      (fields
        (field (name "Manufacturer Part") "GRM155R71H104KE14D")
        (field (name "Manufacturer") "muRata(村田)")
        (field (name "Convert to PCB") "no")
      )
      (libsource (lib "easyedapro") (part "CapAcitance"))
    )
    (comp (ref "C36")
      (value "100nF")
      (footprint "easyedapro:C0402")
      (fields
        (field (name "Manufacturer Part") "GRM155R71H104KE14D")
        (field (name "Manufacturer") "muRata(村田)")
      )
      (libsource (lib "easyedapro") (part "CapAcitance"))
    )
    (comp (ref "C37")
      (value "100nF")
      (footprint "easyedapro:C0402")
      (fields
        (field (name "Manufacturer Part") "GRM155R71H104KE14D")
        (field (name "Manufacturer") "muRata(村田)")
      )
      (libsource (lib "easyedapro") (part "CapAcitance"))
    )
    (comp (ref "C38")
      (value "100nF")
      (footprint "easyedapro:C0402")
      (fields
        (field (name "Manufacturer Part") "GRM155R71H104KE14D")
        (field (name "Manufacturer") "muRata(村田)")
        (field (name "Convert to PCB") "no")
      )
      (libsource (lib "easyedapro") (part "CapAcitance"))
    )
    (comp (ref "C39")
      (value "100nF")
      (footprint "easyedapro:C0402")
      (fields
        (field (name "Manufacturer Part") "GRM155R71H104KE14D")
        (field (name "Manufacturer") "muRata(村田)")
        (field (name "Convert to PCB") "no")
      )
      (libsource (lib "easyedapro") (part "CapAcitance"))
    )
    (comp (ref "C40")
      (value "100nF")
      (footprint "easyedapro:C0402")
      (fields
        (field (name "Manufacturer Part") "GRM155R71H104KE14D")
        (field (name "Manufacturer") "muRata(村田)")
        (field (name "Convert to PCB") "no")
      )
      (libsource (lib "easyedapro") (part "CapAcitance"))
    )
    (comp (ref "C41")
      (value "10uF")
      (footprint "easyedapro:C0402")
      (fields
        (field (name "Manufacturer Part") "CL05A106MP5NUNC")
        (field (name "Manufacturer") "SAMSUNG(三星)")
        (field (name "Convert to PCB") "no")
      )
      (libsource (lib "easyedapro") (part "CapAcitance"))
    )
    (comp (ref "C42")
      (value "10nF")
      (footprint "easyedapro:C0402")
      (fields
        (field (name "Manufacturer Part") "CC0402KRX7R9BB103")
        (field (name "Manufacturer") "YAGEO(国巨)")
      )
      (libsource (lib "easyedapro") (part "CapAcitance"))
    )
    (comp (ref "C43")
      (value "10nF")
      (footprint "easyedapro:C0402")
      (fields
        (field (name "Manufacturer Part") "CC0402KRX7R9BB103")
        (field (name "Manufacturer") "YAGEO(国巨)")
      )
      (libsource (lib "easyedapro") (part "CapAcitance"))
    )
    (comp (ref "R18")
      (value "240Ω")
      (footprint "easyedapro:R0402")
      (fields
        (field (name "Manufacturer Part") "0402WGF2400TCE")
        (field (name "Manufacturer") "UNI-ROYAL(厚声)")
      )
      (libsource (lib "easyedapro") (part "电阻"))
    )
    (comp (ref "R19")
      (value "80.6Ω")
      (footprint "easyedapro:R0402")
      (fields
        (field (name "Manufacturer Part") "0402WGF806JTCE")
        (field (name "Manufacturer") "UNI-ROYAL(厚声)")
      )
      (libsource (lib "easyedapro") (part "电阻"))
    )
    (comp (ref "R20")
      (value "80.6Ω")
      (footprint "easyedapro:R0402")
      (fields
        (field (name "Manufacturer Part") "0402WGF806JTCE")
        (field (name "Manufacturer") "UNI-ROYAL(厚声)")
      )
      (libsource (lib "easyedapro") (part "电阻"))
    )
    (comp (ref "R21")
      (value "4.7kΩ")
      (footprint "easyedapro:R0402")
      (fields
        (field (name "Manufacturer Part") "0402WGF4701TCE")
        (field (name "Manufacturer") "UNI-ROYAL(厚声)")
      )
      (libsource (lib "easyedapro") (part "电阻"))
    )
    (comp (ref "R22")
      (value "80.6Ω")
      (footprint "easyedapro:R0402")
      (fields
        (field (name "Manufacturer Part") "0402WGF806JTCE")
        (field (name "Manufacturer") "UNI-ROYAL(厚声)")
      )
      (libsource (lib "easyedapro") (part "电阻"))
    )
    (comp (ref "R23")
      (value "1kΩ")
      (footprint "easyedapro:R0402")
      (fields
        (field (name "Manufacturer Part") "0402WGF1001TCE")
        (field (name "Manufacturer") "UNI-ROYAL(厚声)")
        (field (name "Convert to PCB") "no")
      )
      (libsource (lib "easyedapro") (part "电阻"))
    )
    (comp (ref "R24")
      (value "1kΩ")
      (footprint "easyedapro:R0402")
      (fields
        (field (name "Manufacturer Part") "0402WGF1001TCE")
        (field (name "Manufacturer") "UNI-ROYAL(厚声)")
        (field (name "Convert to PCB") "no")
      )
      (libsource (lib "easyedapro") (part "电阻"))
    )
    (comp (ref "R25")
      (value "1kΩ")
      (footprint "easyedapro:R0402")
      (fields
        (field (name "Manufacturer Part") "0402WGF1001TCE")
        (field (name "Manufacturer") "UNI-ROYAL(厚声)")
      )
      (libsource (lib "easyedapro") (part "电阻"))
    )
    (comp (ref "R26")
      (value "1kΩ")
      (footprint "easyedapro:R0402")
      (fields
        (field (name "Manufacturer Part") "0402WGF1001TCE")
        (field (name "Manufacturer") "UNI-ROYAL(厚声)")
      )
      (libsource (lib "easyedapro") (part "电阻"))
    )
    (comp (ref "RN1")
      (value "40.2Ω")
      (footprint "easyedapro:RES-ARRAY-SMD_0402-8P-L2.0-W1.0-BL")
      (description "阻值:49.9Ω;精度:±1%;单个元件功率:62.5mW;电阻器数:4;")
      (fields (field (name "Manufacturer Part") "YC124-FR-0740R2L") (field (name "Manufacturer") "YAGEO(国巨)"))
      (libsource (lib "easyedapro") (part "YC124-FR-0749R9L"))
    )
    (comp (ref "RN2")
      (value "40.2Ω")
      (footprint "easyedapro:RES-ARRAY-SMD_0402-8P-L2.0-W1.0-BL")
      (description "阻值:49.9Ω;精度:±1%;单个元件功率:62.5mW;电阻器数:4;")
      (fields (field (name "Manufacturer Part") "YC124-FR-0740R2L") (field (name "Manufacturer") "YAGEO(国巨)"))
      (libsource (lib "easyedapro") (part "YC124-FR-0749R9L"))
    )
    (comp (ref "RN3")
      (value "40.2Ω")
      (footprint "easyedapro:RES-ARRAY-SMD_0402-8P-L2.0-W1.0-BL")
      (description "阻值:49.9Ω;精度:±1%;单个元件功率:62.5mW;电阻器数:4;")
      (fields (field (name "Manufacturer Part") "YC124-FR-0740R2L") (field (name "Manufacturer") "YAGEO(国巨)"))
      (libsource (lib "easyedapro") (part "YC124-FR-0749R9L"))
    )
    (comp (ref "RN4")
      (value "40.2Ω")
      (footprint "easyedapro:RES-ARRAY-SMD_0402-8P-L2.0-W1.0-BL")
      (description "阻值:49.9Ω;精度:±1%;单个元件功率:62.5mW;电阻器数:4;")
      (fields (field (name "Manufacturer Part") "YC124-FR-0740R2L") (field (name "Manufacturer") "YAGEO(国巨)"))
      (libsource (lib "easyedapro") (part "YC124-FR-0749R9L"))
    )
    (comp (ref "RN5")
      (value "40.2Ω")
      (footprint "easyedapro:RES-ARRAY-SMD_0402-8P-L2.0-W1.0-BL")
      (description "阻值:49.9Ω;精度:±1%;单个元件功率:62.5mW;电阻器数:4;")
      (fields (field (name "Manufacturer Part") "YC124-FR-0740R2L") (field (name "Manufacturer") "YAGEO(国巨)"))
      (libsource (lib "easyedapro") (part "YC124-FR-0749R9L"))
    )
    (comp (ref "RN6")
      (value "40.2Ω")
      (footprint "easyedapro:RES-ARRAY-SMD_0402-8P-L2.0-W1.0-BL")
      (description "阻值:49.9Ω;精度:±1%;单个元件功率:62.5mW;电阻器数:4;")
      (fields (field (name "Manufacturer Part") "YC124-FR-0740R2L") (field (name "Manufacturer") "YAGEO(国巨)"))
      (libsource (lib "easyedapro") (part "YC124-FR-0749R9L"))
    )
    (comp (ref "U5")
      (value "MT41K256M16TW-107 IT:P")
      (footprint "easyedapro:FBGA-96_L14.0-W8.0-R16-C6-P0.80-TL")
      (fields (field (name "Manufacturer") "micron(镁光)"))
      (libsource (lib "easyedapro") (part "MT41K256M16TW-107IT{colon}P"))
    )
    (comp (ref "C44")
      (value "100nF")
      (footprint "easyedapro:C0402")
      (fields
        (field (name "Manufacturer Part") "GRM155R71H104KE14D")
        (field (name "Manufacturer") "muRata(村田)")
      )
      (libsource (lib "easyedapro") (part "CapAcitance"))
    )
    (comp (ref "C45")
      (value "10pF")
      (footprint "easyedapro:C0402")
      (fields
        (field (name "Manufacturer Part") "GJM1555C1H100FB01D")
        (field (name "Manufacturer") "muRata(村田)")
      )
      (libsource (lib "easyedapro") (part "CapAcitance"))
    )
    (comp (ref "C46")
      (value "100nF")
      (footprint "easyedapro:C0402")
      (fields
        (field (name "Manufacturer Part") "GRM155R71H104KE14D")
        (field (name "Manufacturer") "muRata(村田)")
      )
      (libsource (lib "easyedapro") (part "CapAcitance"))
    )
    (comp (ref "C47")
      (value "100nF")
      (footprint "easyedapro:C0402")
      (fields
        (field (name "Manufacturer Part") "GRM155R71H104KE14D")
        (field (name "Manufacturer") "muRata(村田)")
      )
      (libsource (lib "easyedapro") (part "CapAcitance"))
    )
    (comp (ref "C48")
      (value "100nF")
      (footprint "easyedapro:C0402")
      (fields
        (field (name "Manufacturer Part") "GRM155R71H104KE14D")
        (field (name "Manufacturer") "muRata(村田)")
      )
      (libsource (lib "easyedapro") (part "CapAcitance"))
    )
    (comp (ref "C49")
      (value "10uF")
      (footprint "easyedapro:C0402")
      (fields
        (field (name "Manufacturer Part") "CL05A106MP5NUNC")
        (field (name "Manufacturer") "SAMSUNG(三星)")
      )
      (libsource (lib "easyedapro") (part "CapAcitance"))
    )
    (comp (ref "C50")
      (value "100nF")
      (footprint "easyedapro:C0402")
      (fields
        (field (name "Manufacturer Part") "GRM155R71H104KE14D")
        (field (name "Manufacturer") "muRata(村田)")
      )
      (libsource (lib "easyedapro") (part "CapAcitance"))
    )
    (comp (ref "C51")
      (value "10uF")
      (footprint "easyedapro:C0402")
      (fields
        (field (name "Manufacturer Part") "CL05A106MP5NUNC")
        (field (name "Manufacturer") "SAMSUNG(三星)")
      )
      (libsource (lib "easyedapro") (part "CapAcitance"))
    )
    (comp (ref "C53")
      (value "100nF")
      (footprint "easyedapro:C0402")
      (fields
        (field (name "Manufacturer Part") "GRM155R71H104KE14D")
        (field (name "Manufacturer") "muRata(村田)")
      )
      (libsource (lib "easyedapro") (part "CapAcitance"))
    )
    (comp (ref "C54")
      (value "100nF")
      (footprint "easyedapro:C0402")
      (fields
        (field (name "Manufacturer Part") "GRM155R71H104KE14D")
        (field (name "Manufacturer") "muRata(村田)")
      )
      (libsource (lib "easyedapro") (part "CapAcitance"))
    )
    (comp (ref "C55")
      (value "2.2uF")
      (footprint "easyedapro:C0402")
      (fields
        (field (name "Manufacturer Part") "GRM155R61E225KE11D")
        (field (name "Manufacturer") "muRata(村田)")
      )
      (libsource (lib "easyedapro") (part "CapAcitance"))
    )
    (comp (ref "C56")
      (value "100nF")
      (footprint "easyedapro:C0402")
      (fields
        (field (name "Manufacturer Part") "GRM155R71H104KE14D")
        (field (name "Manufacturer") "muRata(村田)")
      )
      (libsource (lib "easyedapro") (part "CapAcitance"))
    )
    (comp (ref "C57")
      (value "100nF")
      (footprint "easyedapro:C0402")
      (fields
        (field (name "Manufacturer Part") "GRM155R71H104KE14D")
        (field (name "Manufacturer") "muRata(村田)")
      )
      (libsource (lib "easyedapro") (part "CapAcitance"))
    )
    (comp (ref "C82")
      (value "100nF")
      (footprint "easyedapro:C0402")
      (fields
        (field (name "Manufacturer Part") "GRM155R71H104KE14D")
        (field (name "Manufacturer") "muRata(村田)")
      )
      (libsource (lib "easyedapro") (part "CapAcitance"))
    )
    (comp (ref "CN3")
      (value "X6511WRS-06H-C60D48")
      (footprint "easyedapro:HDR-SMD_6P-P2.54-H-M-W13.3-N")
      (fields (field (name "Manufacturer") "XKB Connection(中国星坤)"))
      (libsource (lib "easyedapro") (part "X6511WRS-06H-C60D48"))
    )
    (comp (ref "L6")
      (value "BLM18KG121TN1D")
      (footprint "easyedapro:L0603")
      (fields (field (name "Manufacturer") "muRata(村田)"))
      (libsource (lib "easyedapro") (part "SDFL1608S100KTF"))
    )
    (comp (ref "LED1")
      (value "YLED0603G")
      (footprint "easyedapro:LED_0603")
      (fields (field (name "Manufacturer") "YONGYUTAI(永裕泰)"))
      (libsource (lib "easyedapro") (part "LED_G"))
    )
    (comp (ref "LED3")
      (value "YLED0603R")
      (footprint "easyedapro:LED_0603")
      (fields (field (name "Manufacturer") "YONGYUTAI(永裕泰)"))
      (libsource (lib "easyedapro") (part "LED_R"))
    )
    (comp (ref "R27")
      (value "20Ω")
      (footprint "easyedapro:R0402")
      (fields
        (field (name "Manufacturer Part") "0402WGF200JTCE")
        (field (name "Manufacturer") "UNI-ROYAL(厚声)")
      )
      (libsource (lib "easyedapro") (part "电阻"))
    )
    (comp (ref "R28")
      (value "10kΩ")
      (footprint "easyedapro:R0402")
      (description "电阻类型:厚膜电阻;阻值:20kΩ;精度:±1%;功率:62.5mW;")
      (fields
        (field (name "Manufacturer Part") "0402WGF1002TCE")
        (field (name "Manufacturer") "UNI-ROYAL(厚声)")
      )
      (libsource (lib "easyedapro") (part "0402WGF2002TCE"))
    )
    (comp (ref "R29")
      (value "470Ω")
      (footprint "easyedapro:R0402")
      (description "电阻类型:厚膜电阻;阻值:20kΩ;精度:±1%;功率:62.5mW;")
      (fields
        (field (name "Manufacturer Part") "0402WGF4700TCE")
        (field (name "Manufacturer") "UNI-ROYAL(厚声)")
      )
      (libsource (lib "easyedapro") (part "0402WGF2002TCE"))
    )
    (comp (ref "R30")
      (value "10kΩ")
      (footprint "easyedapro:R0402")
      (description "电阻类型:厚膜电阻;阻值:20kΩ;精度:±1%;功率:62.5mW;")
      (fields
        (field (name "Manufacturer Part") "0402WGF1002TCE")
        (field (name "Manufacturer") "UNI-ROYAL(厚声)")
      )
      (libsource (lib "easyedapro") (part "0402WGF2002TCE"))
    )
    (comp (ref "R31")
      (value "10kΩ")
      (footprint "easyedapro:R0402")
      (description "电阻类型:厚膜电阻;阻值:20kΩ;精度:±1%;功率:62.5mW;")
      (fields
        (field (name "Manufacturer Part") "0402WGF1002TCE")
        (field (name "Manufacturer") "UNI-ROYAL(厚声)")
      )
      (libsource (lib "easyedapro") (part "0402WGF2002TCE"))
    )
    (comp (ref "R32")
      (value "10kΩ")
      (footprint "easyedapro:R0402")
      (description "电阻类型:厚膜电阻;阻值:20kΩ;精度:±1%;功率:62.5mW;")
      (fields
        (field (name "Manufacturer Part") "0402WGF1002TCE")
        (field (name "Manufacturer") "UNI-ROYAL(厚声)")
      )
      (libsource (lib "easyedapro") (part "0402WGF2002TCE"))
    )
    (comp (ref "R33")
      (value "10kΩ")
      (footprint "easyedapro:R0402")
      (description "电阻类型:厚膜电阻;阻值:20kΩ;精度:±1%;功率:62.5mW;")
      (fields
        (field (name "Manufacturer Part") "0402WGF1002TCE")
        (field (name "Manufacturer") "UNI-ROYAL(厚声)")
      )
      (libsource (lib "easyedapro") (part "0402WGF2002TCE"))
    )
    (comp (ref "R34")
      (value "10kΩ")
      (footprint "easyedapro:R0402")
      (fields
        (field (name "Manufacturer Part") "0402WGF1002TCE")
        (field (name "Manufacturer") "UNI-ROYAL(厚声)")
      )
      (libsource (lib "easyedapro") (part "电阻"))
    )
    (comp (ref "R36")
      (value "20kΩ")
      (footprint "easyedapro:R0402")
      (description "电阻类型:厚膜电阻;阻值:20kΩ;精度:±1%;功率:62.5mW;最大工作电压:50V;温度系数:±100ppm/℃;")
      (fields
        (field (name "Manufacturer Part") "0402WGF2002TCE")
        (field (name "Manufacturer") "UNI-ROYAL(厚声)")
      )
      (libsource (lib "easyedapro") (part "电阻"))
    )
    (comp (ref "R37")
      (value "1kΩ")
      (footprint "easyedapro:R0402")
      (fields
        (field (name "Manufacturer Part") "0402WGF1001TCE")
        (field (name "Manufacturer") "UNI-ROYAL(厚声)")
      )
      (libsource (lib "easyedapro") (part "电阻"))
    )
    (comp (ref "R38")
      (value "1kΩ")
      (footprint "easyedapro:R0402")
      (fields
        (field (name "Manufacturer Part") "0402WGF1001TCE")
        (field (name "Manufacturer") "UNI-ROYAL(厚声)")
      )
      (libsource (lib "easyedapro") (part "电阻"))
    )
    (comp (ref "R39")
      (value "33Ω")
      (footprint "easyedapro:R0402")
      (fields
        (field (name "Manufacturer Part") "0402WGF330JTCE")
        (field (name "Manufacturer") "UNI-ROYAL(厚声)")
      )
      (libsource (lib "easyedapro") (part "电阻"))
    )
    (comp (ref "R40")
      (value "33Ω")
      (footprint "easyedapro:R0402")
      (fields
        (field (name "Manufacturer Part") "0402WGF330JTCE")
        (field (name "Manufacturer") "UNI-ROYAL(厚声)")
      )
      (libsource (lib "easyedapro") (part "电阻"))
    )
    (comp (ref "R41")
      (value "4.7kΩ")
      (footprint "easyedapro:R0402")
      (fields
        (field (name "Manufacturer Part") "0402WGF4701TCE")
        (field (name "Manufacturer") "UNI-ROYAL(厚声)")
      )
      (libsource (lib "easyedapro") (part "电阻"))
    )
    (comp (ref "R42")
      (value "4.7kΩ")
      (footprint "easyedapro:R0402")
      (fields
        (field (name "Manufacturer Part") "0402WGF4701TCE")
        (field (name "Manufacturer") "UNI-ROYAL(厚声)")
      )
      (libsource (lib "easyedapro") (part "电阻"))
    )
    (comp (ref "R43")
      (value "4.7kΩ")
      (footprint "easyedapro:R0402")
      (fields
        (field (name "Manufacturer Part") "0402WGF4701TCE")
        (field (name "Manufacturer") "UNI-ROYAL(厚声)")
      )
      (libsource (lib "easyedapro") (part "电阻"))
    )
    (comp (ref "R73")
      (value "20kΩ")
      (footprint "easyedapro:R0402")
      (description "电阻类型:厚膜电阻;阻值:20kΩ;精度:±1%;功率:62.5mW;最大工作电压:50V;温度系数:±100ppm/℃;")
      (fields
        (field (name "Manufacturer Part") "0402WGF2002TCE")
        (field (name "Manufacturer") "UNI-ROYAL(厚声)")
      )
      (libsource (lib "easyedapro") (part "0402WGF2002TCE"))
    )
    (comp (ref "R74")
      (value "20kΩ")
      (footprint "easyedapro:R0402")
      (description "电阻类型:厚膜电阻;阻值:20kΩ;精度:±1%;功率:62.5mW;最大工作电压:50V;温度系数:±100ppm/℃;")
      (fields
        (field (name "Manufacturer Part") "0402WGF2002TCE")
        (field (name "Manufacturer") "UNI-ROYAL(厚声)")
      )
      (libsource (lib "easyedapro") (part "0402WGF2002TCE"))
    )
    (comp (ref "R75")
      (value "10kΩ")
      (footprint "easyedapro:R0402")
      (description "电阻类型:厚膜电阻;阻值:20kΩ;精度:±1%;功率:62.5mW;")
      (fields
        (field (name "Manufacturer Part") "0402WGF1002TCE")
        (field (name "Manufacturer") "UNI-ROYAL(厚声)")
      )
      (libsource (lib "easyedapro") (part "0402WGF2002TCE"))
    )
    (comp (ref "R76")
      (value "10kΩ")
      (footprint "easyedapro:R0402")
      (description "电阻类型:厚膜电阻;阻值:20kΩ;精度:±1%;功率:62.5mW;")
      (fields
        (field (name "Manufacturer Part") "0402WGF1002TCE")
        (field (name "Manufacturer") "UNI-ROYAL(厚声)")
      )
      (libsource (lib "easyedapro") (part "0402WGF2002TCE"))
    )
    (comp (ref "R77")
      (value "1kΩ")
      (footprint "easyedapro:R0402")
      (fields
        (field (name "Manufacturer Part") "0402WGF1001TCE")
        (field (name "Manufacturer") "UNI-ROYAL(厚声)")
      )
      (libsource (lib "easyedapro") (part "电阻"))
    )
    (comp (ref "R78")
      (value "1kΩ")
      (footprint "easyedapro:R0402")
      (fields
        (field (name "Manufacturer Part") "0402WGF1001TCE")
        (field (name "Manufacturer") "UNI-ROYAL(厚声)")
      )
      (libsource (lib "easyedapro") (part "电阻"))
    )
    (comp (ref "R79")
      (value "4.7kΩ")
      (footprint "easyedapro:R0402")
      (fields
        (field (name "Manufacturer Part") "0402WGF4701TCE")
        (field (name "Manufacturer") "UNI-ROYAL(厚声)")
      )
      (libsource (lib "easyedapro") (part "电阻"))
    )
    (comp (ref "R80")
      (value "4.7kΩ")
      (footprint "easyedapro:R0402")
      (fields
        (field (name "Manufacturer Part") "0402WGF4701TCE")
        (field (name "Manufacturer") "UNI-ROYAL(厚声)")
      )
      (libsource (lib "easyedapro") (part "电阻"))
    )
    (comp (ref "R82")
      (value "1kΩ")
      (footprint "easyedapro:R0402")
      (fields
        (field (name "Manufacturer Part") "0402WGF1001TCE")
        (field (name "Manufacturer") "UNI-ROYAL(厚声)")
      )
      (libsource (lib "easyedapro") (part "电阻"))
    )
    (comp (ref "R83")
      (value "0Ω")
      (footprint "easyedapro:R0402")
      (fields
        (field (name "Manufacturer Part") "0603WAF0000T5E")
        (field (name "Manufacturer") "UNI-ROYAL(厚声)")
      )
      (libsource (lib "easyedapro") (part "电阻"))
    )
    (comp (ref "R84")
      (value "10kΩ")
      (footprint "easyedapro:R0402")
      (description "电阻类型:厚膜电阻;阻值:20kΩ;精度:±1%;功率:62.5mW;")
      (fields
        (field (name "Manufacturer Part") "0402WGF1002TCE")
        (field (name "Manufacturer") "UNI-ROYAL(厚声)")
      )
      (libsource (lib "easyedapro") (part "0402WGF2002TCE"))
    )
    (comp (ref "R85")
      (value "10kΩ")
      (footprint "easyedapro:R0402")
      (description "电阻类型:厚膜电阻;阻值:20kΩ;精度:±1%;功率:62.5mW;")
      (fields
        (field (name "Manufacturer Part") "0402WGF1002TCE")
        (field (name "Manufacturer") "UNI-ROYAL(厚声)")
      )
      (libsource (lib "easyedapro") (part "0402WGF2002TCE"))
    )
    (comp (ref "R86")
      (value "10kΩ")
      (footprint "easyedapro:R0402")
      (description "电阻类型:厚膜电阻;阻值:20kΩ;精度:±1%;功率:62.5mW;")
      (fields
        (field (name "Manufacturer Part") "0402WGF1002TCE")
        (field (name "Manufacturer") "UNI-ROYAL(厚声)")
      )
      (libsource (lib "easyedapro") (part "0402WGF2002TCE"))
    )
    (comp (ref "R87")
      (value "10kΩ")
      (footprint "easyedapro:R0402")
      (description "电阻类型:厚膜电阻;阻值:20kΩ;精度:±1%;功率:62.5mW;")
      (fields
        (field (name "Manufacturer Part") "0402WGF1002TCE")
        (field (name "Manufacturer") "UNI-ROYAL(厚声)")
      )
      (libsource (lib "easyedapro") (part "0402WGF2002TCE"))
    )
    (comp (ref "SW1")
      (value "DSHP02TSGET")
      (footprint "easyedapro:SW-SMD_4P_DSHP02TSGET")
      (description "类型:平拨，凹槽式;电路结构:单刀单掷;开关位数:2;引脚间距:1.27mm;颜色:黑色;")
      (fields (field (name "Manufacturer") "YE"))
      (libsource (lib "easyedapro") (part "DSHP02TSGET"))
    )
    (comp (ref "U8")
      (value "~")
      (footprint "easyedapro:WQFN-24_L4.0-W4.0-P0.50-TL-EP2.5")
      (description "TXS02612 具有电压电平转换功能的 SDIO 端口扩展器")
      (fields (field (name "Manufacturer Part") "TXS02612RTWR") (field (name "Manufacturer") "TI(德州仪器)"))
      (libsource (lib "easyedapro") (part "TXS02612RTWR"))
    )
    (comp (ref "U9")
      (value "CH343P")
      (footprint "easyedapro:TQFN-16_L3.0-W3.0-P0.50-BL-EP1.7")
      (description "应用功能:-;接口协议:-;")
      (fields (field (name "Manufacturer") "WCH(南京沁恒)"))
      (libsource (lib "easyedapro") (part "CH343P"))
    )
    (comp (ref "U10")
      (value "W25Q128JVEIQ")
      (footprint "easyedapro:WSON-8_L6.0-W8.0-P1.27-BL-EP")
      (fields (field (name "Manufacturer") "WINBOND(华邦)"))
      (libsource (lib "easyedapro") (part "W25Q128JVEIQ"))
    )
    (comp (ref "U11")
      (value "WS2812B-V5")
      (footprint "easyedapro:LED-SMD_4P-L5.0-W5.0-TL_WS2812B-B")
      (libsource (lib "easyedapro") (part "WS2812B-V5"))
    )
    (comp (ref "USB1")
      (value "typec")
      (footprint "easyedapro:USB-C-SMD_KH-TYPE-C-16P")
      (libsource (lib "easyedapro") (part "TYPEC_C9900016956"))
    )
    (comp (ref "X1")
      (value "33.3333MHz")
      (footprint "easyedapro:OSC-SMD_4P-L3.2-W2.5-BL")
      (description "频率:50MHz;工作电压:3.3V;")
      (fields
        (field (name "Manufacturer Part") "OT322533.3333MJBA4SL")
        (field (name "Manufacturer") "YXC(扬兴晶振)")
      )
      (libsource (lib "easyedapro") (part "Q33310F70062200"))
    )
  )
  (nets
    (net (code "1") (name "+5V") (class "Default")
      (node (ref "C11") (pin "1") (pinfunction "1_1") (pintype "input"))
      (node (ref "C12") (pin "1") (pinfunction "1_1") (pintype "input"))
      (node (ref "C5") (pin "1") (pinfunction "1_1") (pintype "input"))
      (node (ref "C6") (pin "1") (pinfunction "1_1") (pintype "input"))
      (node (ref "CN1") (pin "57") (pinfunction "57_57") (pintype "input"))
      (node (ref "CN1") (pin "58") (pinfunction "58_58") (pintype "input"))
      (node (ref "CN1") (pin "59") (pinfunction "59_59") (pintype "input"))
      (node (ref "CN1") (pin "60") (pinfunction "60_60") (pintype "input"))
      (node (ref "CN2") (pin "57") (pinfunction "57_57") (pintype "input"))
      (node (ref "CN2") (pin "58") (pinfunction "58_58") (pintype "input"))
      (node (ref "CN2") (pin "59") (pinfunction "59_59") (pintype "input"))
      (node (ref "CN2") (pin "60") (pinfunction "60_60") (pintype "input"))
      (node (ref "R11") (pin "1") (pinfunction "1_1") (pintype "input"))
      (node (ref "R12") (pin "2") (pinfunction "2_2") (pintype "input"))
      (node (ref "R4") (pin "1") (pinfunction "1_1") (pintype "input"))
      (node (ref "R5") (pin "1") (pinfunction "1_1") (pintype "input"))
      (node (ref "R83") (pin "2") (pinfunction "2_2") (pintype "input"))
      (node (ref "U1") (pin "1") (pinfunction "EN_1") (pintype "input"))
      (node (ref "U1") (pin "2") (pinfunction "VIN_2") (pintype "input"))
      (node (ref "U2") (pin "2") (pinfunction "VIN_2") (pintype "input"))
      (node (ref "U3") (pin "2") (pinfunction "VIN_2") (pintype "input"))
      (node (ref "U4") (pin "2") (pinfunction "VIN_2") (pintype "input"))
    )
    (net (code "2") (name "1V0") (class "Default")
      (node (ref "C68") (pin "2") (pinfunction "2_2") (pintype "input"))
      (node (ref "C69") (pin "2") (pinfunction "2_2") (pintype "input"))
      (node (ref "C70") (pin "2") (pinfunction "2_2") (pintype "input"))
      (node (ref "C71") (pin "2") (pinfunction "2_2") (pintype "input"))
      (node (ref "C73") (pin "2") (pinfunction "2_2") (pintype "input"))
      (node (ref "L1") (pin "1") (pinfunction "IN_1") (pintype "input"))
      (node (ref "U7") (pin "G11") (pinfunction "VCCBRAM_G11") (pintype "input"))
      (node (ref "U7") (pin "G13") (pinfunction "VCCINT_G13") (pintype "input"))
      (node (ref "U7") (pin "G7") (pinfunction "VCCPINT_G7") (pintype "input"))
      (node (ref "U7") (pin "H10") (pinfunction "VCCBRAM_H10") (pintype "input"))
      (node (ref "U7") (pin "H12") (pinfunction "VCCINT_H12") (pintype "input"))
      (node (ref "U7") (pin "J13") (pinfunction "VCCINT_J13") (pintype "input"))
      (node (ref "U7") (pin "J7") (pinfunction "VCCPINT_J7") (pintype "input"))
      (node (ref "U7") (pin "K12") (pinfunction "VCCINT_K12") (pintype "input"))
      (node (ref "U7") (pin "L13") (pinfunction "VCCINT_L13") (pintype "input"))
      (node (ref "U7") (pin "L7") (pinfunction "VCCPINT_L7") (pintype "input"))
      (node (ref "U7") (pin "M12") (pinfunction "VCCINT_M12") (pintype "input"))
      (node (ref "U7") (pin "N13") (pinfunction "VCCINT_N13") (pintype "input"))
      (node (ref "U7") (pin "N7") (pinfunction "VCCPINT_N7") (pintype "input"))
      (node (ref "U7") (pin "P12") (pinfunction "VCCINT_P12") (pintype "input"))
      (node (ref "U7") (pin "P8") (pinfunction "VCCPINT_P8") (pintype "input"))
      (node (ref "U7") (pin "R13") (pinfunction "VCCINT_R13") (pintype "input"))
      (node (ref "U7") (pin "R7") (pinfunction "VCCPINT_R7") (pintype "input"))
    )
    (net (code "3") (name "1V5") (class "Default")
      (node (ref "C15") (pin "2") (pinfunction "2_2") (pintype "input"))
      (node (ref "C16") (pin "2") (pinfunction "2_2") (pintype "input"))
      (node (ref "C17") (pin "2") (pinfunction "2_2") (pintype "input"))
      (node (ref "C18") (pin "2") (pinfunction "2_2") (pintype "input"))
      (node (ref "C19") (pin "2") (pinfunction "2_2") (pintype "input"))
      (node (ref "C20") (pin "2") (pinfunction "2_2") (pintype "input"))
      (node (ref "C21") (pin "2") (pinfunction "2_2") (pintype "input"))
      (node (ref "C22") (pin "2") (pinfunction "2_2") (pintype "input"))
      (node (ref "C23") (pin "2") (pinfunction "2_2") (pintype "input"))
      (node (ref "C24") (pin "2") (pinfunction "2_2") (pintype "input"))
      (node (ref "C25") (pin "2") (pinfunction "2_2") (pintype "input"))
      (node (ref "C26") (pin "2") (pinfunction "2_2") (pintype "input"))
      (node (ref "C30") (pin "2") (pinfunction "2_2") (pintype "input"))
      (node (ref "C34") (pin "1") (pinfunction "1_1") (pintype "input"))
      (node (ref "C36") (pin "1") (pinfunction "1_1") (pintype "input"))
      (node (ref "C41") (pin "1") (pinfunction "1_1") (pintype "input"))
      (node (ref "C42") (pin "1") (pinfunction "1_1") (pintype "input"))
      (node (ref "L5") (pin "1") (pinfunction "IN_1") (pintype "input"))
      (node (ref "R20") (pin "1") (pinfunction "1_1") (pintype "input"))
      (node (ref "R23") (pin "1") (pinfunction "1_1") (pintype "input"))
      (node (ref "R25") (pin "1") (pinfunction "1_1") (pintype "input"))
      (node (ref "R6") (pin "1") (pinfunction "1_1") (pintype "input"))
      (node (ref "U5") (pin "A1") (pinfunction "VDDQ_A1") (pintype "input"))
      (node (ref "U5") (pin "A8") (pinfunction "VDDQ_A8") (pintype "input"))
      (node (ref "U5") (pin "B2") (pinfunction "VDD_B2") (pintype "input"))
      (node (ref "U5") (pin "C1") (pinfunction "VDDQ_C1") (pintype "input"))
      (node (ref "U5") (pin "C9") (pinfunction "VDDQ_C9") (pintype "input"))
      (node (ref "U5") (pin "D2") (pinfunction "VDDQ_D2") (pintype "input"))
      (node (ref "U5") (pin "D9") (pinfunction "VDD_D9") (pintype "input"))
      (node (ref "U5") (pin "E9") (pinfunction "VDDQ_E9") (pintype "input"))
      (node (ref "U5") (pin "F1") (pinfunction "VDDQ_F1") (pintype "input"))
      (node (ref "U5") (pin "G7") (pinfunction "VDD_G7") (pintype "input"))
      (node (ref "U5") (pin "H2") (pinfunction "VDDQ_H2") (pintype "input"))
      (node (ref "U5") (pin "H9") (pinfunction "VDDQ_H9") (pintype "input"))
      (node (ref "U5") (pin "K2") (pinfunction "VDD_K2") (pintype "input"))
      (node (ref "U5") (pin "K8") (pinfunction "VDD_K8") (pintype "input"))
      (node (ref "U5") (pin "N1") (pinfunction "VDD_N1") (pintype "input"))
      (node (ref "U5") (pin "N9") (pinfunction "VDD_N9") (pintype "input"))
      (node (ref "U5") (pin "R1") (pinfunction "VDD_R1") (pintype "input"))
      (node (ref "U5") (pin "R9") (pinfunction "VDD_R9") (pintype "input"))
      (node (ref "U7") (pin "A3") (pinfunction "VCCO_DDR_502_A3") (pintype "input"))
      (node (ref "U7") (pin "D2") (pinfunction "VCCO_DDR_502_D2") (pintype "input"))
      (node (ref "U7") (pin "E5") (pinfunction "VCCO_DDR_502_E5") (pintype "input"))
      (node (ref "U7") (pin "G1") (pinfunction "VCCO_DDR_502_G1") (pintype "input"))
      (node (ref "U7") (pin "H4") (pinfunction "VCCO_DDR_502_H4") (pintype "input"))
      (node (ref "U7") (pin "L3") (pinfunction "VCCO_DDR_502_L3") (pintype "input"))
      (node (ref "U7") (pin "P2") (pinfunction "VCCO_DDR_502_P2") (pintype "input"))
      (node (ref "U7") (pin "R5") (pinfunction "VCCO_DDR_502_R5") (pintype "input"))
      (node (ref "U7") (pin "U1") (pinfunction "VCCO_DDR_502_U1") (pintype "input"))
      (node (ref "U7") (pin "V4") (pinfunction "VCCO_DDR_502_V4") (pintype "input"))
    )
    (net (code "4") (name "1V8") (class "Default")
      (node (ref "C49") (pin "1") (pinfunction "1_1") (pintype "input"))
      (node (ref "C50") (pin "1") (pinfunction "1_1") (pintype "input"))
      (node (ref "C56") (pin "2") (pinfunction "2_2") (pintype "input"))
      (node (ref "C74") (pin "2") (pinfunction "2_2") (pintype "input"))
      (node (ref "C75") (pin "2") (pinfunction "2_2") (pintype "input"))
      (node (ref "C76") (pin "2") (pinfunction "2_2") (pintype "input"))
      (node (ref "L2") (pin "1") (pinfunction "IN_1") (pintype "input"))
      (node (ref "L3") (pin "2") (pinfunction "2_2") (pintype "input"))
      (node (ref "R34") (pin "2") (pinfunction "2_2") (pintype "input"))
      (node (ref "R38") (pin "1") (pinfunction "1_1") (pintype "input"))
      (node (ref "U7") (pin "A13") (pinfunction "VCCO_MIO1_501_A13") (pintype "input"))
      (node (ref "U7") (pin "B16") (pinfunction "VCCO_MIO1_501_B16") (pintype "input"))
      (node (ref "U7") (pin "D12") (pinfunction "VCCO_MIO1_501_D12") (pintype "input"))
      (node (ref "U7") (pin "E15") (pinfunction "VCCO_MIO1_501_E15") (pintype "input"))
      (node (ref "U7") (pin "F11") (pinfunction "VCCBATT_0_F11") (pintype "input"))
      (node (ref "U7") (pin "F8") (pinfunction "VCCPAUX_F8") (pintype "input"))
      (node (ref "U7") (pin "G9") (pinfunction "VCCPAUX_G9") (pintype "input"))
      (node (ref "U7") (pin "H8") (pinfunction "VCCPAUX_H8") (pintype "input"))
      (node (ref "U7") (pin "J11") (pinfunction "VCCAUX_J11") (pintype "input"))
      (node (ref "U7") (pin "J9") (pinfunction "VCCADC_0_J9") (pintype "input"))
      (node (ref "U7") (pin "K8") (pinfunction "VCCPAUX_K8") (pintype "input"))
      (node (ref "U7") (pin "L11") (pinfunction "VCCAUX_L11") (pintype "input"))
      (node (ref "U7") (pin "M8") (pinfunction "VCCPAUX_M8") (pintype "input"))
      (node (ref "U7") (pin "N11") (pinfunction "VCCAUX_N11") (pintype "input"))
      (node (ref "U7") (pin "N9") (pinfunction "VCCAUX_N9") (pintype "input"))
      (node (ref "U7") (pin "P10") (pinfunction "VCCAUX_P10") (pintype "input"))
      (node (ref "U7") (pin "R9") (pinfunction "VCCAUX_R9") (pintype "input"))
      (node (ref "U8") (pin "5") (pinfunction "VCCA_5") (pintype "input"))
      (node (ref "U9") (pin "1") (pinfunction "VIO_1") (pintype "unspecified"))
    )
    (net (code "5") (name "3V3") (class "Default")
      (node (ref "C46") (pin "1") (pinfunction "1_1") (pintype "input"))
      (node (ref "C47") (pin "2") (pinfunction "2_2") (pintype "input"))
      (node (ref "C51") (pin "1") (pinfunction "1_1") (pintype "input"))
      (node (ref "C53") (pin "1") (pinfunction "1_1") (pintype "input"))
      (node (ref "C58") (pin "2") (pinfunction "2_2") (pintype "input"))
      (node (ref "C59") (pin "2") (pinfunction "2_2") (pintype "input"))
      (node (ref "C60") (pin "2") (pinfunction "2_2") (pintype "input"))
      (node (ref "C61") (pin "2") (pinfunction "2_2") (pintype "input"))
      (node (ref "C62") (pin "2") (pinfunction "2_2") (pintype "input"))
      (node (ref "C63") (pin "2") (pinfunction "2_2") (pintype "input"))
      (node (ref "C64") (pin "2") (pinfunction "2_2") (pintype "input"))
      (node (ref "C65") (pin "2") (pinfunction "2_2") (pintype "input"))
      (node (ref "C66") (pin "2") (pinfunction "2_2") (pintype "input"))
      (node (ref "C67") (pin "2") (pinfunction "2_2") (pintype "input"))
      (node (ref "C81") (pin "1") (pinfunction "1_1") (pintype "input"))
      (node (ref "C82") (pin "2") (pinfunction "2_2") (pintype "input"))
      (node (ref "CN3") (pin "1") (pinfunction "1_1") (pintype "unspecified"))
      (node (ref "L4") (pin "1") (pinfunction "IN_1") (pintype "input"))
      (node (ref "L6") (pin "2") (pinfunction "2_2") (pintype "input"))
      (node (ref "L7") (pin "2") (pinfunction "2_2") (pintype "input"))
      (node (ref "R1") (pin "1") (pinfunction "1_1") (pintype "input"))
      (node (ref "R2") (pin "1") (pinfunction "1_1") (pintype "input"))
      (node (ref "R28") (pin "1") (pinfunction "1_1") (pintype "input"))
      (node (ref "R29") (pin "1") (pinfunction "1_1") (pintype "input"))
      (node (ref "R36") (pin "1") (pinfunction "1_1") (pintype "input"))
      (node (ref "R42") (pin "2") (pinfunction "2_2") (pintype "input"))
      (node (ref "R43") (pin "2") (pinfunction "2_2") (pintype "input"))
      (node (ref "R75") (pin "2") (pinfunction "2_2") (pintype "input"))
      (node (ref "R76") (pin "2") (pinfunction "2_2") (pintype "input"))
      (node (ref "R78") (pin "1") (pinfunction "1_1") (pintype "input"))
      (node (ref "R84") (pin "2") (pinfunction "2_2") (pintype "input"))
      (node (ref "R85") (pin "2") (pinfunction "2_2") (pintype "input"))
      (node (ref "R86") (pin "2") (pinfunction "2_2") (pintype "input"))
      (node (ref "R87") (pin "2") (pinfunction "2_2") (pintype "input"))
      (node (ref "U10") (pin "8") (pinfunction "VCC_8") (pintype "input"))
      (node (ref "U11") (pin "1") (pinfunction "VDD_1") (pintype "input"))
      (node (ref "U7") (pin "B6") (pinfunction "VCCO_MIO0_500_B6") (pintype "input"))
      (node (ref "U7") (pin "C19") (pinfunction "VCCO_35_C19") (pintype "input"))
      (node (ref "U7") (pin "D7") (pinfunction "VCCO_MIO0_500_D7") (pintype "input"))
      (node (ref "U7") (pin "F18") (pinfunction "VCCO_35_F18") (pintype "input"))
      (node (ref "U7") (pin "H14") (pinfunction "VCCO_35_H14") (pintype "input"))
      (node (ref "U7") (pin "J17") (pinfunction "VCCO_35_J17") (pintype "input"))
      (node (ref "U7") (pin "K20") (pinfunction "VCCO_35_K20") (pintype "input"))
      (node (ref "U7") (pin "K6") (pinfunction "VCCO_0_K6") (pintype "input"))
      (node (ref "U7") (pin "M16") (pinfunction "VCCO_35_M16") (pintype "input"))
      (node (ref "U7") (pin "M6") (pinfunction "CFGBVS_0_M6") (pintype "input"))
      (node (ref "U7") (pin "N19") (pinfunction "VCCO_34_N19") (pintype "input"))
      (node (ref "U7") (pin "N6") (pinfunction "RSVDVCC3_N6") (pintype "input"))
      (node (ref "U7") (pin "R15") (pinfunction "VCCO_34_R15") (pintype "input"))
      (node (ref "U7") (pin "R6") (pinfunction "RSVDVCC2_R6") (pintype "input"))
      (node (ref "U7") (pin "T18") (pinfunction "VCCO_34_T18") (pintype "input"))
      (node (ref "U7") (pin "T6") (pinfunction "RSVDVCC1_T6") (pintype "input"))
      (node (ref "U7") (pin "T8") (pinfunction "VCCO_13_T8") (pintype "input"))
      (node (ref "U7") (pin "U11") (pinfunction "VCCO_13_U11") (pintype "input"))
      (node (ref "U7") (pin "V14") (pinfunction "VCCO_34_V14") (pintype "input"))
      (node (ref "U7") (pin "W17") (pinfunction "VCCO_34_W17") (pintype "input"))
      (node (ref "U7") (pin "W7") (pinfunction "VCCO_13_W7") (pintype "input"))
      (node (ref "U7") (pin "Y10") (pinfunction "VCCO_13_Y10") (pintype "input"))
      (node (ref "U7") (pin "Y20") (pinfunction "VCCO_34_Y20") (pintype "input"))
      (node (ref "U8") (pin "17") (pinfunction "VCCB1_17") (pintype "input"))
      (node (ref "U8") (pin "21") (pinfunction "VCCB0_21") (pintype "input"))
    )
    (net (code "6") (name "AIO_0") (class "Default")
      (node (ref "U7") (pin "R19") (pinfunction "IO_0_34_R19") (pintype "input"))
    )
    (net (code "7") (name "AIO_1_N") (class "Default")
      (node (ref "CN1") (pin "14") (pinfunction "14_14") (pintype "input"))
      (node (ref "U7") (pin "T10") (pinfunction "IO_L1N_T0_34_T10") (pintype "input"))
    )
    (net (code "8") (name "AIO_1_P") (class "Default")
      (node (ref "CN1") (pin "12") (pinfunction "12_12") (pintype "input"))
      (node (ref "U7") (pin "T11") (pinfunction "IO_L1P_T0_34_T11") (pintype "input"))
    )
    (net (code "9") (name "AIO_2_N") (class "Default")
      (node (ref "CN1") (pin "18") (pinfunction "18_18") (pintype "input"))
      (node (ref "U7") (pin "U12") (pinfunction "IO_L2N_T0_34_U12") (pintype "input"))
    )
    (net (code "10") (name "AIO_2_P") (class "Default")
      (node (ref "CN1") (pin "16") (pinfunction "16_16") (pintype "input"))
      (node (ref "U7") (pin "T12") (pinfunction "IO_L2P_T0_34_T12") (pintype "input"))
    )
    (net (code "11") (name "AIO_3_N") (class "Default")
      (node (ref "CN1") (pin "24") (pinfunction "24_24") (pintype "input"))
      (node (ref "U7") (pin "V13") (pinfunction "IO_L3N_T0_DQS_34_V13") (pintype "input"))
    )
    (net (code "12") (name "AIO_3_P") (class "Default")
      (node (ref "CN1") (pin "22") (pinfunction "22_22") (pintype "input"))
      (node (ref "U7") (pin "U13") (pinfunction "IO_L3P_T0_DQS_PUDC_B_34_U13") (pintype "input"))
    )
    (net (code "13") (name "AIO_4_N") (class "Default")
      (node (ref "CN1") (pin "17") (pinfunction "17_17") (pintype "input"))
      (node (ref "U7") (pin "W13") (pinfunction "IO_L4N_T0_34_W13") (pintype "input"))
    )
    (net (code "14") (name "AIO_4_P") (class "Default")
      (node (ref "CN1") (pin "15") (pinfunction "15_15") (pintype "input"))
      (node (ref "U7") (pin "V12") (pinfunction "IO_L4P_T0_34_V12") (pintype "input"))
    )
    (net (code "15") (name "AIO_5_N") (class "Default")
      (node (ref "CN1") (pin "32") (pinfunction "32_32") (pintype "input"))
      (node (ref "U7") (pin "T15") (pinfunction "IO_L5N_T0_34_T15") (pintype "input"))
    )
    (net (code "16") (name "AIO_5_P") (class "Default")
      (node (ref "CN1") (pin "30") (pinfunction "30_30") (pintype "input"))
      (node (ref "U7") (pin "T14") (pinfunction "IO_L5P_T0_34_T14") (pintype "input"))
    )
    (net (code "17") (name "AIO_6_N") (class "Default")
      (node (ref "CN1") (pin "28") (pinfunction "28_28") (pintype "input"))
      (node (ref "U7") (pin "R14") (pinfunction "IO_L6N_T0_VREF_34_R14") (pintype "input"))
    )
    (net (code "18") (name "AIO_6_P") (class "Default")
      (node (ref "CN1") (pin "26") (pinfunction "26_26") (pintype "input"))
      (node (ref "U7") (pin "P14") (pinfunction "IO_L6P_T0_34_P14") (pintype "input"))
    )
    (net (code "19") (name "AIO_7_N") (class "Default")
      (node (ref "CN1") (pin "45") (pinfunction "45_45") (pintype "input"))
      (node (ref "U7") (pin "Y17") (pinfunction "IO_L7N_T1_34_Y17") (pintype "input"))
    )
    (net (code "20") (name "AIO_7_P") (class "Default")
      (node (ref "CN1") (pin "43") (pinfunction "43_43") (pintype "input"))
      (node (ref "U7") (pin "Y16") (pinfunction "IO_L7P_T1_34_Y16") (pintype "input"))
    )
    (net (code "21") (name "AIO_8_N") (class "Default")
      (node (ref "CN1") (pin "27") (pinfunction "27_27") (pintype "input"))
      (node (ref "U7") (pin "Y14") (pinfunction "IO_L8N_T1_34_Y14") (pintype "input"))
    )
    (net (code "22") (name "AIO_8_P") (class "Default")
      (node (ref "CN1") (pin "25") (pinfunction "25_25") (pintype "input"))
      (node (ref "U7") (pin "W14") (pinfunction "IO_L8P_T1_34_W14") (pintype "input"))
    )
    (net (code "23") (name "AIO_9_N") (class "Default")
      (node (ref "U7") (pin "U17") (pinfunction "IO_L9N_T1_DQS_34_U17") (pintype "input"))
    )
    (net (code "24") (name "AIO_9_P") (class "Default")
      (node (ref "U11") (pin "4") (pinfunction "DIN_4") (pintype "input"))
      (node (ref "U7") (pin "T16") (pinfunction "IO_L9P_T1_DQS_34_T16") (pintype "input"))
    )
    (net (code "25") (name "AIO_10_N") (class "Default")
      (node (ref "CN1") (pin "23") (pinfunction "23_23") (pintype "input"))
      (node (ref "U7") (pin "W15") (pinfunction "IO_L10N_T1_34_W15") (pintype "input"))
    )
    (net (code "26") (name "AIO_10_P") (class "Default")
      (node (ref "CN1") (pin "21") (pinfunction "21_21") (pintype "input"))
      (node (ref "U7") (pin "V15") (pinfunction "IO_L10P_T1_34_V15") (pintype "input"))
    )
    (net (code "27") (name "AIO_11_P") (class "Default")
      (node (ref "U7") (pin "U14") (pinfunction "IO_L11P_T1_SRCC_34_U14") (pintype "input"))
    )
    (net (code "28") (name "AIO_12_N") (class "Default")
      (node (ref "CN1") (pin "46") (pinfunction "46_46") (pintype "input"))
      (node (ref "U7") (pin "U19") (pinfunction "IO_L12N_T1_MRCC_34_U19") (pintype "input"))
    )
    (net (code "29") (name "AIO_12_P") (class "Default")
      (node (ref "CN1") (pin "44") (pinfunction "44_44") (pintype "input"))
      (node (ref "U7") (pin "U18") (pinfunction "IO_L12P_T1_MRCC_34_U18") (pintype "input"))
    )
    (net (code "30") (name "AIO_13_N") (class "Default")
      (node (ref "U7") (pin "P19") (pinfunction "IO_L13N_T2_MRCC_34_P19") (pintype "input"))
    )
    (net (code "31") (name "AIO_13_P") (class "Default")
      (node (ref "U7") (pin "N18") (pinfunction "IO_L13P_T2_MRCC_34_N18") (pintype "input"))
    )
    (net (code "32") (name "AIO_14_N") (class "Default")
      (node (ref "CN1") (pin "50") (pinfunction "50_50") (pintype "input"))
      (node (ref "U7") (pin "P20") (pinfunction "IO_L14N_T2_SRCC_34_P20") (pintype "input"))
    )
    (net (code "33") (name "AIO_14_P") (class "Default")
      (node (ref "CN1") (pin "48") (pinfunction "48_48") (pintype "input"))
      (node (ref "U7") (pin "N20") (pinfunction "IO_L14P_T2_SRCC_34_N20") (pintype "input"))
    )
    (net (code "34") (name "AIO_15_N") (class "Default")
      (node (ref "CN1") (pin "49") (pinfunction "49_49") (pintype "input"))
      (node (ref "U7") (pin "U20") (pinfunction "IO_L15N_T2_DQS_34_U20") (pintype "input"))
    )
    (net (code "35") (name "AIO_15_P") (class "Default")
      (node (ref "CN1") (pin "47") (pinfunction "47_47") (pintype "input"))
      (node (ref "U7") (pin "T20") (pinfunction "IO_L15P_T2_DQS_34_T20") (pintype "input"))
    )
    (net (code "36") (name "AIO_16_N") (class "Default")
      (node (ref "CN1") (pin "54") (pinfunction "54_54") (pintype "input"))
      (node (ref "U7") (pin "W20") (pinfunction "IO_L16N_T2_34_W20") (pintype "input"))
    )
    (net (code "37") (name "AIO_16_P") (class "Default")
      (node (ref "CN1") (pin "52") (pinfunction "52_52") (pintype "input"))
      (node (ref "U7") (pin "V20") (pinfunction "IO_L16P_T2_34_V20") (pintype "input"))
    )
    (net (code "38") (name "AIO_17_N") (class "Default")
      (node (ref "CN1") (pin "53") (pinfunction "53_53") (pintype "input"))
      (node (ref "U7") (pin "Y19") (pinfunction "IO_L17N_T2_34_Y19") (pintype "input"))
    )
    (net (code "39") (name "AIO_17_P") (class "Default")
      (node (ref "CN1") (pin "51") (pinfunction "51_51") (pintype "input"))
      (node (ref "U7") (pin "Y18") (pinfunction "IO_L17P_T2_34_Y18") (pintype "input"))
    )
    (net (code "40") (name "AIO_18_N") (class "Default")
      (node (ref "CN1") (pin "31") (pinfunction "31_31") (pintype "input"))
      (node (ref "U7") (pin "W16") (pinfunction "IO_L18N_T2_34_W16") (pintype "input"))
    )
    (net (code "41") (name "AIO_18_P") (class "Default")
      (node (ref "CN1") (pin "29") (pinfunction "29_29") (pintype "input"))
      (node (ref "U7") (pin "V16") (pinfunction "IO_L18P_T2_34_V16") (pintype "input"))
    )
    (net (code "42") (name "AIO_19_N") (class "Default")
      (node (ref "CN1") (pin "42") (pinfunction "42_42") (pintype "input"))
      (node (ref "U7") (pin "R17") (pinfunction "IO_L19N_T3_VREF_34_R17") (pintype "input"))
    )
    (net (code "43") (name "AIO_19_P") (class "Default")
      (node (ref "CN1") (pin "40") (pinfunction "40_40") (pintype "input"))
      (node (ref "U7") (pin "R16") (pinfunction "IO_L19P_T3_34_R16") (pintype "input"))
    )
    (net (code "44") (name "AIO_20_N") (class "Default")
      (node (ref "U7") (pin "R18") (pinfunction "IO_L20N_T3_34_R18") (pintype "input"))
    )
    (net (code "45") (name "AIO_20_P") (class "Default")
      (node (ref "U7") (pin "T17") (pinfunction "IO_L20P_T3_34_T17") (pintype "input"))
    )
    (net (code "46") (name "AIO_21_N") (class "Default")
      (node (ref "CN1") (pin "35") (pinfunction "35_35") (pintype "input"))
      (node (ref "U7") (pin "V18") (pinfunction "IO_L21N_T3_DQS_34_V18") (pintype "input"))
    )
    (net (code "47") (name "AIO_21_P") (class "Default")
      (node (ref "CN1") (pin "33") (pinfunction "33_33") (pintype "input"))
      (node (ref "U7") (pin "V17") (pinfunction "IO_L21P_T3_DQS_34_V17") (pintype "input"))
    )
    (net (code "48") (name "AIO_22_N") (class "Default")
      (node (ref "CN1") (pin "41") (pinfunction "41_41") (pintype "input"))
      (node (ref "U7") (pin "W19") (pinfunction "IO_L22N_T3_34_W19") (pintype "input"))
    )
    (net (code "49") (name "AIO_22_P") (class "Default")
      (node (ref "CN1") (pin "39") (pinfunction "39_39") (pintype "input"))
      (node (ref "U7") (pin "W18") (pinfunction "IO_L22P_T3_34_W18") (pintype "input"))
    )
    (net (code "50") (name "AIO_23_N") (class "Default")
      (node (ref "U7") (pin "P18") (pinfunction "IO_L23N_T3_34_P18") (pintype "input"))
    )
    (net (code "51") (name "AIO_23_P") (class "Default")
      (node (ref "U7") (pin "N17") (pinfunction "IO_L23P_T3_34_N17") (pintype "input"))
    )
    (net (code "52") (name "AIO_24_N") (class "Default")
      (node (ref "CN1") (pin "36") (pinfunction "36_36") (pintype "input"))
      (node (ref "U7") (pin "P16") (pinfunction "IO_L24N_T3_34_P16") (pintype "input"))
    )
    (net (code "53") (name "AIO_24_P") (class "Default")
      (node (ref "CN1") (pin "34") (pinfunction "34_34") (pintype "input"))
      (node (ref "U7") (pin "P15") (pinfunction "IO_L24P_T3_34_P15") (pintype "input"))
    )
    (net (code "54") (name "AIO_25") (class "Default")
      (node (ref "U7") (pin "T19") (pinfunction "IO_25_34_T19") (pintype "input"))
    )
    (net (code "55") (name "BIO_0") (class "Default")
      (node (ref "U7") (pin "G14") (pinfunction "IO_0_35_G14") (pintype "input"))
    )
    (net (code "56") (name "BIO_1_N") (class "Default")
      (node (ref "CN2") (pin "50") (pinfunction "50_50") (pintype "input"))
      (node (ref "U7") (pin "B20") (pinfunction "IO_L1N_T0_AD0N_35_B20") (pintype "input"))
    )
    (net (code "57") (name "BIO_1_P") (class "Default")
      (node (ref "CN2") (pin "48") (pinfunction "48_48") (pintype "input"))
      (node (ref "U7") (pin "C20") (pinfunction "IO_L1P_T0_AD0P_35_C20") (pintype "input"))
    )
    (net (code "58") (name "BIO_2_N") (class "Default")
      (node (ref "CN2") (pin "45") (pinfunction "45_45") (pintype "input"))
      (node (ref "U7") (pin "A20") (pinfunction "IO_L2N_T0_AD8N_35_A20") (pintype "input"))
    )
    (net (code "59") (name "BIO_2_P") (class "Default")
      (node (ref "CN2") (pin "43") (pinfunction "43_43") (pintype "input"))
      (node (ref "U7") (pin "B19") (pinfunction "IO_L2P_T0_AD8P_35_B19") (pintype "input"))
    )
    (net (code "60") (name "BIO_3_N") (class "Default")
      (node (ref "CN2") (pin "41") (pinfunction "41_41") (pintype "input"))
      (node (ref "U7") (pin "D18") (pinfunction "IO_L3N_T0_DQS_AD1N_35_D18") (pintype "input"))
    )
    (net (code "61") (name "BIO_3_P") (class "Default")
      (node (ref "CN2") (pin "39") (pinfunction "39_39") (pintype "input"))
      (node (ref "U7") (pin "E17") (pinfunction "IO_L3P_T0_DQS_AD1P_35_E17") (pintype "input"))
    )
    (net (code "62") (name "BIO_4_N") (class "Default")
      (node (ref "CN2") (pin "42") (pinfunction "42_42") (pintype "input"))
      (node (ref "U7") (pin "D20") (pinfunction "IO_L4N_T0_35_D20") (pintype "input"))
    )
    (net (code "63") (name "BIO_4_P") (class "Default")
      (node (ref "CN2") (pin "40") (pinfunction "40_40") (pintype "input"))
      (node (ref "U7") (pin "D19") (pinfunction "IO_L4P_T0_35_D19") (pintype "input"))
    )
    (net (code "64") (name "BIO_5_N") (class "Default")
      (node (ref "CN2") (pin "32") (pinfunction "32_32") (pintype "input"))
      (node (ref "U7") (pin "E19") (pinfunction "IO_L5N_T0_AD9N_35_E19") (pintype "input"))
    )
    (net (code "65") (name "BIO_5_P") (class "Default")
      (node (ref "CN2") (pin "30") (pinfunction "30_30") (pintype "input"))
      (node (ref "U7") (pin "E18") (pinfunction "IO_L5P_T0_AD9P_35_E18") (pintype "input"))
    )
    (net (code "66") (name "BIO_6_N") (class "Default")
      (node (ref "U7") (pin "F17") (pinfunction "IO_L6N_T0_VREF_35_F17") (pintype "input"))
    )
    (net (code "67") (name "BIO_6_P") (class "Default")
      (node (ref "U7") (pin "F16") (pinfunction "IO_L6P_T0_35_F16") (pintype "input"))
    )
    (net (code "68") (name "BIO_7_N") (class "Default")
      (node (ref "U7") (pin "M20") (pinfunction "IO_L7N_T1_AD2N_35_M20") (pintype "input"))
    )
    (net (code "69") (name "BIO_7_P") (class "Default")
      (node (ref "U7") (pin "M19") (pinfunction "IO_L7P_T1_AD2P_35_M19") (pintype "input"))
    )
    (net (code "70") (name "BIO_8_N") (class "Default")
      (node (ref "U7") (pin "M18") (pinfunction "IO_L8N_T1_AD10N_35_M18") (pintype "input"))
    )
    (net (code "71") (name "BIO_8_P") (class "Default")
      (node (ref "U7") (pin "M17") (pinfunction "IO_L8P_T1_AD10P_35_M17") (pintype "input"))
    )
    (net (code "72") (name "BIO_9_N") (class "Default")
      (node (ref "U7") (pin "L20") (pinfunction "IO_L9N_T1_DQS_AD3N_35_L20") (pintype "input"))
    )
    (net (code "73") (name "BIO_9_P") (class "Default")
      (node (ref "U7") (pin "L19") (pinfunction "IO_L9P_T1_DQS_AD3P_35_L19") (pintype "input"))
    )
    (net (code "74") (name "BIO_10_N") (class "Default")
      (node (ref "U7") (pin "J19") (pinfunction "IO_L10N_T1_AD11N_35_J19") (pintype "input"))
    )
    (net (code "75") (name "BIO_10_P") (class "Default")
      (node (ref "U7") (pin "K19") (pinfunction "IO_L10P_T1_AD11P_35_K19") (pintype "input"))
    )
    (net (code "76") (name "BIO_11_N") (class "Default")
      (node (ref "U7") (pin "L17") (pinfunction "IO_L11N_T1_SRCC_35_L17") (pintype "input"))
    )
    (net (code "77") (name "BIO_11_P") (class "Default")
      (node (ref "U7") (pin "L16") (pinfunction "IO_L11P_T1_SRCC_35_L16") (pintype "input"))
    )
    (net (code "78") (name "BIO_12_N") (class "Default")
      (node (ref "CN2") (pin "31") (pinfunction "31_31") (pintype "input"))
      (node (ref "U7") (pin "K18") (pinfunction "IO_L12N_T1_MRCC_35_K18") (pintype "input"))
    )
    (net (code "79") (name "BIO_12_P") (class "Default")
      (node (ref "CN2") (pin "29") (pinfunction "29_29") (pintype "input"))
      (node (ref "U7") (pin "K17") (pinfunction "IO_L12P_T1_MRCC_35_K17") (pintype "input"))
    )
    (net (code "80") (name "BIO_13_N") (class "Default")
      (node (ref "CN2") (pin "36") (pinfunction "36_36") (pintype "input"))
      (node (ref "U7") (pin "H17") (pinfunction "IO_L13N_T2_MRCC_35_H17") (pintype "input"))
    )
    (net (code "81") (name "BIO_13_P") (class "Default")
      (node (ref "CN2") (pin "34") (pinfunction "34_34") (pintype "input"))
      (node (ref "U7") (pin "H16") (pinfunction "IO_L13P_T2_MRCC_35_H16") (pintype "input"))
    )
    (net (code "82") (name "BIO_14_N") (class "Default")
      (node (ref "CN2") (pin "49") (pinfunction "49_49") (pintype "input"))
      (node (ref "U7") (pin "H18") (pinfunction "IO_L14N_T2_AD4N_SRCC_35_H18") (pintype "input"))
    )
    (net (code "83") (name "BIO_14_P") (class "Default")
      (node (ref "CN2") (pin "47") (pinfunction "47_47") (pintype "input"))
      (node (ref "U7") (pin "J18") (pinfunction "IO_L14P_T2_AD4P_SRCC_35_J18") (pintype "input"))
    )
    (net (code "84") (name "BIO_15_N") (class "Default")
      (node (ref "CN2") (pin "46") (pinfunction "46_46") (pintype "input"))
      (node (ref "U7") (pin "F20") (pinfunction "IO_L15N_T2_DQS_AD12N_35_F20") (pintype "input"))
    )
    (net (code "85") (name "BIO_15_P") (class "Default")
      (node (ref "CN2") (pin "44") (pinfunction "44_44") (pintype "input"))
      (node (ref "U7") (pin "F19") (pinfunction "IO_L15P_T2_DQS_AD12P_35_F19") (pintype "input"))
    )
    (net (code "86") (name "BIO_16_N") (class "Default")
      (node (ref "U7") (pin "G18") (pinfunction "IO_L16N_T2_35_G18") (pintype "input"))
    )
    (net (code "87") (name "BIO_16_P") (class "Default")
      (node (ref "U7") (pin "G17") (pinfunction "IO_L16P_T2_35_G17") (pintype "input"))
    )
    (net (code "88") (name "BIO_17_N") (class "Default")
      (node (ref "CN2") (pin "53") (pinfunction "53_53") (pintype "input"))
      (node (ref "U7") (pin "H20") (pinfunction "IO_L17N_T2_AD5N_35_H20") (pintype "input"))
    )
    (net (code "89") (name "BIO_17_P") (class "Default")
      (node (ref "CN2") (pin "51") (pinfunction "51_51") (pintype "input"))
      (node (ref "U7") (pin "J20") (pinfunction "IO_L17P_T2_AD5P_35_J20") (pintype "input"))
    )
    (net (code "90") (name "BIO_18_N") (class "Default")
      (node (ref "CN2") (pin "54") (pinfunction "54_54") (pintype "input"))
      (node (ref "U7") (pin "G20") (pinfunction "IO_L18N_T2_AD13N_35_G20") (pintype "input"))
    )
    (net (code "91") (name "BIO_18_P") (class "Default")
      (node (ref "CN2") (pin "52") (pinfunction "52_52") (pintype "input"))
      (node (ref "U7") (pin "G19") (pinfunction "IO_L18P_T2_AD13P_35_G19") (pintype "input"))
    )
    (net (code "92") (name "BIO_19_N") (class "Default")
      (node (ref "CN2") (pin "35") (pinfunction "35_35") (pintype "input"))
      (node (ref "U7") (pin "G15") (pinfunction "IO_L19N_T3_VREF_35_G15") (pintype "input"))
    )
    (net (code "93") (name "BIO_19_P") (class "Default")
      (node (ref "CN2") (pin "33") (pinfunction "33_33") (pintype "input"))
      (node (ref "U7") (pin "H15") (pinfunction "IO_L19P_T3_35_H15") (pintype "input"))
    )
    (net (code "94") (name "BIO_20_N") (class "Default")
      (node (ref "CN2") (pin "27") (pinfunction "27_27") (pintype "input"))
      (node (ref "U7") (pin "J14") (pinfunction "IO_L20N_T3_AD6N_35_J14") (pintype "input"))
    )
    (net (code "95") (name "BIO_20_P") (class "Default")
      (node (ref "CN2") (pin "25") (pinfunction "25_25") (pintype "input"))
      (node (ref "U7") (pin "K14") (pinfunction "IO_L20P_T3_AD6P_35_K14") (pintype "input"))
    )
    (net (code "96") (name "BIO_21_N") (class "Default")
      (node (ref "U7") (pin "N16") (pinfunction "IO_L21N_T3_DQS_AD14N_35_N16") (pintype "input"))
    )
    (net (code "97") (name "BIO_21_P") (class "Default")
      (node (ref "U7") (pin "N15") (pinfunction "IO_L21P_T3_DQS_AD14P_35_N15") (pintype "input"))
    )
    (net (code "98") (name "BIO_22_N") (class "Default")
      (node (ref "U7") (pin "L15") (pinfunction "IO_L22N_T3_AD7N_35_L15") (pintype "input"))
    )
    (net (code "99") (name "BIO_22_P") (class "Default")
      (node (ref "R82") (pin "2") (pinfunction "2_2") (pintype "input"))
      (node (ref "U7") (pin "L14") (pinfunction "IO_L22P_T3_AD7P_35_L14") (pintype "input"))
    )
    (net (code "100") (name "BIO_23_N") (class "Default")
      (node (ref "U7") (pin "M15") (pinfunction "IO_L23N_T3_35_M15") (pintype "input"))
    )
    (net (code "101") (name "BIO_23_P") (class "Default")
      (node (ref "U7") (pin "M14") (pinfunction "IO_L23P_T3_35_M14") (pintype "input"))
    )
    (net (code "102") (name "BIO_24_N") (class "Default")
      (node (ref "CN2") (pin "23") (pinfunction "23_23") (pintype "input"))
      (node (ref "U7") (pin "J16") (pinfunction "IO_L24N_T3_AD15N_35_J16") (pintype "input"))
    )
    (net (code "103") (name "BIO_24_P") (class "Default")
      (node (ref "CN2") (pin "21") (pinfunction "21_21") (pintype "input"))
      (node (ref "U7") (pin "K16") (pinfunction "IO_L24P_T3_AD15P_35_K16") (pintype "input"))
    )
    (net (code "104") (name "BIO_25") (class "Default")
      (node (ref "U7") (pin "J15") (pinfunction "IO_25_35_J15") (pintype "input"))
    )
    (net (code "105") (name "CC1") (class "Default")
      (node (ref "R80") (pin "2") (pinfunction "2_2") (pintype "input"))
      (node (ref "USB1") (pin "A5") (pinfunction "CC1_A5") (pintype "input"))
    )
    (net (code "106") (name "CC2") (class "Default")
      (node (ref "R79") (pin "2") (pinfunction "2_2") (pintype "input"))
      (node (ref "USB1") (pin "B5") (pinfunction "CC2_B5") (pintype "input"))
    )
    (net (code "107") (name "DDRVTT") (class "Default")
      (node (ref "C31") (pin "2") (pinfunction "2_2") (pintype "input"))
      (node (ref "C32") (pin "2") (pinfunction "2_2") (pintype "input"))
      (node (ref "C33") (pin "2") (pinfunction "2_2") (pintype "input"))
      (node (ref "C34") (pin "2") (pinfunction "2_2") (pintype "input"))
      (node (ref "C35") (pin "1") (pinfunction "1_1") (pintype "input"))
      (node (ref "C38") (pin "1") (pinfunction "1_1") (pintype "input"))
      (node (ref "C39") (pin "1") (pinfunction "1_1") (pintype "input"))
      (node (ref "C40") (pin "1") (pinfunction "1_1") (pintype "input"))
      (node (ref "R23") (pin "2") (pinfunction "2_2") (pintype "input"))
      (node (ref "R24") (pin "1") (pinfunction "1_1") (pintype "input"))
      (node (ref "RN1") (pin "5") (pinfunction "5_5") (pintype "input"))
      (node (ref "RN1") (pin "6") (pinfunction "6_6") (pintype "input"))
      (node (ref "RN1") (pin "7") (pinfunction "7_7") (pintype "input"))
      (node (ref "RN1") (pin "8") (pinfunction "8_8") (pintype "input"))
      (node (ref "RN2") (pin "5") (pinfunction "5_5") (pintype "input"))
      (node (ref "RN2") (pin "6") (pinfunction "6_6") (pintype "input"))
      (node (ref "RN2") (pin "7") (pinfunction "7_7") (pintype "input"))
      (node (ref "RN2") (pin "8") (pinfunction "8_8") (pintype "input"))
      (node (ref "RN3") (pin "5") (pinfunction "5_5") (pintype "input"))
      (node (ref "RN3") (pin "6") (pinfunction "6_6") (pintype "input"))
      (node (ref "RN3") (pin "7") (pinfunction "7_7") (pintype "input"))
      (node (ref "RN3") (pin "8") (pinfunction "8_8") (pintype "input"))
      (node (ref "RN4") (pin "5") (pinfunction "5_5") (pintype "input"))
      (node (ref "RN4") (pin "6") (pinfunction "6_6") (pintype "input"))
      (node (ref "RN4") (pin "7") (pinfunction "7_7") (pintype "input"))
      (node (ref "RN4") (pin "8") (pinfunction "8_8") (pintype "input"))
      (node (ref "RN5") (pin "5") (pinfunction "5_5") (pintype "input"))
      (node (ref "RN5") (pin "6") (pinfunction "6_6") (pintype "input"))
      (node (ref "RN5") (pin "7") (pinfunction "7_7") (pintype "input"))
      (node (ref "RN5") (pin "8") (pinfunction "8_8") (pintype "input"))
      (node (ref "RN6") (pin "5") (pinfunction "5_5") (pintype "input"))
      (node (ref "RN6") (pin "6") (pinfunction "6_6") (pintype "input"))
      (node (ref "RN6") (pin "7") (pinfunction "7_7") (pintype "input"))
      (node (ref "RN6") (pin "8") (pinfunction "8_8") (pintype "input"))
    )
    (net (code "108") (name "DDR_A0") (class "Default")
      (node (ref "RN4") (pin "2") (pinfunction "2_2") (pintype "input"))
      (node (ref "U5") (pin "N3") (pinfunction "A0_N3") (pintype "input"))
      (node (ref "U7") (pin "N2") (pinfunction "PS_DDR_A0_502_N2") (pintype "input"))
    )
    (net (code "109") (name "DDR_A1") (class "Default")
      (node (ref "RN2") (pin "1") (pinfunction "1_1") (pintype "input"))
      (node (ref "U5") (pin "P7") (pinfunction "A1_P7") (pintype "input"))
      (node (ref "U7") (pin "K2") (pinfunction "PS_DDR_A1_502_K2") (pintype "input"))
    )
    (net (code "110") (name "DDR_A2") (class "Default")
      (node (ref "RN5") (pin "2") (pinfunction "2_2") (pintype "input"))
      (node (ref "U5") (pin "P3") (pinfunction "A2_P3") (pintype "input"))
      (node (ref "U7") (pin "M3") (pinfunction "PS_DDR_A2_502_M3") (pintype "input"))
    )
    (net (code "111") (name "DDR_A3") (class "Default")
      (node (ref "RN6") (pin "4") (pinfunction "4_4") (pintype "input"))
      (node (ref "U5") (pin "N2") (pinfunction "A3_N2") (pintype "input"))
      (node (ref "U7") (pin "K3") (pinfunction "PS_DDR_A3_502_K3") (pintype "input"))
    )
    (net (code "112") (name "DDR_A4") (class "Default")
      (node (ref "RN1") (pin "2") (pinfunction "2_2") (pintype "input"))
      (node (ref "U5") (pin "P8") (pinfunction "A4_P8") (pintype "input"))
      (node (ref "U7") (pin "M4") (pinfunction "PS_DDR_A4_502_M4") (pintype "input"))
    )
    (net (code "113") (name "DDR_A5") (class "Default")
      (node (ref "RN5") (pin "1") (pinfunction "1_1") (pintype "input"))
      (node (ref "U5") (pin "P2") (pinfunction "A5_P2") (pintype "input"))
      (node (ref "U7") (pin "L1") (pinfunction "PS_DDR_A5_502_L1") (pintype "input"))
    )
    (net (code "114") (name "DDR_A6") (class "Default")
      (node (ref "RN1") (pin "1") (pinfunction "1_1") (pintype "input"))
      (node (ref "U5") (pin "R8") (pinfunction "A6_R8") (pintype "input"))
      (node (ref "U7") (pin "L4") (pinfunction "PS_DDR_A6_502_L4") (pintype "input"))
    )
    (net (code "115") (name "DDR_A7") (class "Default")
      (node (ref "RN5") (pin "3") (pinfunction "3_3") (pintype "input"))
      (node (ref "U5") (pin "R2") (pinfunction "A7_R2") (pintype "input"))
      (node (ref "U7") (pin "K4") (pinfunction "PS_DDR_A7_502_K4") (pintype "input"))
    )
    (net (code "116") (name "DDR_A8") (class "Default")
      (node (ref "RN2") (pin "4") (pinfunction "4_4") (pintype "input"))
      (node (ref "U5") (pin "T8") (pinfunction "A8_T8") (pintype "input"))
      (node (ref "U7") (pin "K1") (pinfunction "PS_DDR_A8_502_K1") (pintype "input"))
    )
    (net (code "117") (name "DDR_A9") (class "Default")
      (node (ref "RN5") (pin "4") (pinfunction "4_4") (pintype "input"))
      (node (ref "U5") (pin "R3") (pinfunction "A9_R3") (pintype "input"))
      (node (ref "U7") (pin "J4") (pinfunction "PS_DDR_A9_502_J4") (pintype "input"))
    )
    (net (code "118") (name "DDR_A10") (class "Default")
      (node (ref "RN3") (pin "3") (pinfunction "3_3") (pintype "input"))
      (node (ref "U5") (pin "L7") (pinfunction "A10/AP_L7") (pintype "input"))
      (node (ref "U7") (pin "F5") (pinfunction "PS_DDR_A10_502_F5") (pintype "input"))
    )
    (net (code "119") (name "DDR_A11") (class "Default")
      (node (ref "RN2") (pin "3") (pinfunction "3_3") (pintype "input"))
      (node (ref "U5") (pin "R7") (pinfunction "A11_R7") (pintype "input"))
      (node (ref "U7") (pin "G4") (pinfunction "PS_DDR_A11_502_G4") (pintype "input"))
    )
    (net (code "120") (name "DDR_A12") (class "Default")
      (node (ref "RN3") (pin "4") (pinfunction "4_4") (pintype "input"))
      (node (ref "U5") (pin "N7") (pinfunction "A12/BC#_N7") (pintype "input"))
      (node (ref "U7") (pin "E4") (pinfunction "PS_DDR_A12_502_E4") (pintype "input"))
    )
    (net (code "121") (name "DDR_A13") (class "Default")
      (node (ref "RN4") (pin "1") (pinfunction "1_1") (pintype "input"))
      (node (ref "U5") (pin "T3") (pinfunction "A13_T3") (pintype "input"))
      (node (ref "U7") (pin "D4") (pinfunction "PS_DDR_A13_502_D4") (pintype "input"))
    )
    (net (code "122") (name "DDR_A14") (class "Default")
      (node (ref "RN2") (pin "2") (pinfunction "2_2") (pintype "input"))
      (node (ref "U5") (pin "T7") (pinfunction "A14_T7") (pintype "input"))
      (node (ref "U7") (pin "F4") (pinfunction "PS_DDR_A14_502_F4") (pintype "input"))
    )
    (net (code "123") (name "DDR_BA0") (class "Default")
      (node (ref "RN6") (pin "3") (pinfunction "3_3") (pintype "input"))
      (node (ref "U5") (pin "M2") (pinfunction "BA0_M2") (pintype "input"))
      (node (ref "U7") (pin "L5") (pinfunction "PS_DDR_BA0_502_L5") (pintype "input"))
    )
    (net (code "124") (name "DDR_BA1") (class "Default")
      (node (ref "RN1") (pin "3") (pinfunction "3_3") (pintype "input"))
      (node (ref "U5") (pin "N8") (pinfunction "BA1_N8") (pintype "input"))
      (node (ref "U7") (pin "R4") (pinfunction "PS_DDR_BA1_502_R4") (pintype "input"))
    )
    (net (code "125") (name "DDR_BA2") (class "Default")
      (node (ref "RN4") (pin "3") (pinfunction "3_3") (pintype "input"))
      (node (ref "U5") (pin "M3") (pinfunction "BA2_M3") (pintype "input"))
      (node (ref "U7") (pin "J5") (pinfunction "PS_DDR_BA2_502_J5") (pintype "input"))
    )
    (net (code "126") (name "DDR_CAS") (class "Default")
      (node (ref "RN3") (pin "1") (pinfunction "1_1") (pintype "input"))
      (node (ref "U5") (pin "K3") (pinfunction "CAS#_K3") (pintype "input"))
      (node (ref "U7") (pin "P5") (pinfunction "PS_DDR_CAS_B_502_P5") (pintype "input"))
    )
    (net (code "127") (name "DDR_CKE") (class "Default")
      (node (ref "RN1") (pin "4") (pinfunction "4_4") (pintype "input"))
      (node (ref "U5") (pin "K9") (pinfunction "CKE_K9") (pintype "input"))
      (node (ref "U7") (pin "N3") (pinfunction "PS_DDR_CKE_502_N3") (pintype "input"))
    )
    (net (code "128") (name "DDR_CLK_N") (class "Default")
      (node (ref "R22") (pin "2") (pinfunction "2_2") (pintype "input"))
      (node (ref "U5") (pin "K7") (pinfunction "CK#_K7") (pintype "input"))
      (node (ref "U7") (pin "M2") (pinfunction "PS_DDR_CKN_502_M2") (pintype "input"))
    )
    (net (code "129") (name "DDR_CLK_P") (class "Default")
      (node (ref "R22") (pin "1") (pinfunction "1_1") (pintype "input"))
      (node (ref "U5") (pin "J7") (pinfunction "CK_J7") (pintype "input"))
      (node (ref "U7") (pin "L2") (pinfunction "PS_DDR_CKP_502_L2") (pintype "input"))
    )
    (net (code "130") (name "DDR_CS") (class "Default")
      (node (ref "RN6") (pin "2") (pinfunction "2_2") (pintype "input"))
      (node (ref "U5") (pin "L2") (pinfunction "CS#_L2") (pintype "input"))
      (node (ref "U7") (pin "N1") (pinfunction "PS_DDR_CS_B_502_N1") (pintype "input"))
    )
    (net (code "131") (name "DDR_D0") (class "Default")
      (node (ref "U5") (pin "E3") (pinfunction "DQ0_E3") (pintype "input"))
      (node (ref "U7") (pin "C3") (pinfunction "PS_DDR_DQ0_502_C3") (pintype "input"))
    )
    (net (code "132") (name "DDR_D1") (class "Default")
      (node (ref "U5") (pin "F7") (pinfunction "DQ1_F7") (pintype "input"))
      (node (ref "U7") (pin "B3") (pinfunction "PS_DDR_DQ1_502_B3") (pintype "input"))
    )
    (net (code "133") (name "DDR_D2") (class "Default")
      (node (ref "U5") (pin "F2") (pinfunction "DQ2_F2") (pintype "input"))
      (node (ref "U7") (pin "A2") (pinfunction "PS_DDR_DQ2_502_A2") (pintype "input"))
    )
    (net (code "134") (name "DDR_D3") (class "Default")
      (node (ref "U5") (pin "F8") (pinfunction "DQ3_F8") (pintype "input"))
      (node (ref "U7") (pin "A4") (pinfunction "PS_DDR_DQ3_502_A4") (pintype "input"))
    )
    (net (code "135") (name "DDR_D4") (class "Default")
      (node (ref "U5") (pin "H3") (pinfunction "DQ4_H3") (pintype "input"))
      (node (ref "U7") (pin "D3") (pinfunction "PS_DDR_DQ4_502_D3") (pintype "input"))
    )
    (net (code "136") (name "DDR_D5") (class "Default")
      (node (ref "U5") (pin "H8") (pinfunction "DQ5_H8") (pintype "input"))
      (node (ref "U7") (pin "D1") (pinfunction "PS_DDR_DQ5_502_D1") (pintype "input"))
    )
    (net (code "137") (name "DDR_D6") (class "Default")
      (node (ref "U5") (pin "G2") (pinfunction "DQ6_G2") (pintype "input"))
      (node (ref "U7") (pin "C1") (pinfunction "PS_DDR_DQ6_502_C1") (pintype "input"))
    )
    (net (code "138") (name "DDR_D7") (class "Default")
      (node (ref "U5") (pin "H7") (pinfunction "DQ7_H7") (pintype "input"))
      (node (ref "U7") (pin "E1") (pinfunction "PS_DDR_DQ7_502_E1") (pintype "input"))
    )
    (net (code "139") (name "DDR_D8") (class "Default")
      (node (ref "U5") (pin "D7") (pinfunction "DQ8_D7") (pintype "input"))
      (node (ref "U7") (pin "E2") (pinfunction "PS_DDR_DQ8_502_E2") (pintype "input"))
    )
    (net (code "140") (name "DDR_D9") (class "Default")
      (node (ref "U5") (pin "C3") (pinfunction "DQ9_C3") (pintype "input"))
      (node (ref "U7") (pin "E3") (pinfunction "PS_DDR_DQ9_502_E3") (pintype "input"))
    )
    (net (code "141") (name "DDR_D10") (class "Default")
      (node (ref "U5") (pin "C8") (pinfunction "DQ10_C8") (pintype "input"))
      (node (ref "U7") (pin "G3") (pinfunction "PS_DDR_DQ10_502_G3") (pintype "input"))
    )
    (net (code "142") (name "DDR_D11") (class "Default")
      (node (ref "U5") (pin "C2") (pinfunction "DQ11_C2") (pintype "input"))
      (node (ref "U7") (pin "H3") (pinfunction "PS_DDR_DQ11_502_H3") (pintype "input"))
    )
    (net (code "143") (name "DDR_D12") (class "Default")
      (node (ref "U5") (pin "A7") (pinfunction "DQ12_A7") (pintype "input"))
      (node (ref "U7") (pin "J3") (pinfunction "PS_DDR_DQ12_502_J3") (pintype "input"))
    )
    (net (code "144") (name "DDR_D13") (class "Default")
      (node (ref "U5") (pin "A2") (pinfunction "DQ13_A2") (pintype "input"))
      (node (ref "U7") (pin "H2") (pinfunction "PS_DDR_DQ13_502_H2") (pintype "input"))
    )
    (net (code "145") (name "DDR_D14") (class "Default")
      (node (ref "U5") (pin "B8") (pinfunction "DQ14_B8") (pintype "input"))
      (node (ref "U7") (pin "H1") (pinfunction "PS_DDR_DQ14_502_H1") (pintype "input"))
    )
    (net (code "146") (name "DDR_D15") (class "Default")
      (node (ref "U5") (pin "A3") (pinfunction "DQ15_A3") (pintype "input"))
      (node (ref "U7") (pin "J1") (pinfunction "PS_DDR_DQ15_502_J1") (pintype "input"))
    )
    (net (code "147") (name "DDR_DM0") (class "Default")
      (node (ref "U5") (pin "E7") (pinfunction "LDM_E7") (pintype "input"))
      (node (ref "U7") (pin "A1") (pinfunction "PS_DDR_DM0_502_A1") (pintype "input"))
    )
    (net (code "148") (name "DDR_DM1") (class "Default")
      (node (ref "U5") (pin "D3") (pinfunction "UDM_D3") (pintype "input"))
      (node (ref "U7") (pin "F1") (pinfunction "PS_DDR_DM1_502_F1") (pintype "input"))
    )
    (net (code "149") (name "DDR_DQS0_N") (class "Default")
      (node (ref "U5") (pin "G3") (pinfunction "LDQS#_G3") (pintype "input"))
      (node (ref "U7") (pin "B2") (pinfunction "PS_DDR_DQS_N0_502_B2") (pintype "input"))
    )
    (net (code "150") (name "DDR_DQS0_P") (class "Default")
      (node (ref "U5") (pin "F3") (pinfunction "LDQS_F3") (pintype "input"))
      (node (ref "U7") (pin "C2") (pinfunction "PS_DDR_DQS_P0_502_C2") (pintype "input"))
    )
    (net (code "151") (name "DDR_DQS1_N") (class "Default")
      (node (ref "U5") (pin "B7") (pinfunction "UDQS#_B7") (pintype "input"))
      (node (ref "U7") (pin "F2") (pinfunction "PS_DDR_DQS_N1_502_F2") (pintype "input"))
    )
    (net (code "152") (name "DDR_DQS1_P") (class "Default")
      (node (ref "U5") (pin "C7") (pinfunction "UDQS_C7") (pintype "input"))
      (node (ref "U7") (pin "G2") (pinfunction "PS_DDR_DQS_P1_502_G2") (pintype "input"))
    )
    (net (code "153") (name "DDR_ODT") (class "Default")
      (node (ref "RN6") (pin "1") (pinfunction "1_1") (pintype "input"))
      (node (ref "U5") (pin "K1") (pinfunction "ODT_K1") (pintype "input"))
      (node (ref "U7") (pin "N5") (pinfunction "PS_DDR_ODT_502_N5") (pintype "input"))
    )
    (net (code "154") (name "DDR_RAS") (class "Default")
      (node (ref "RN3") (pin "2") (pinfunction "2_2") (pintype "input"))
      (node (ref "U5") (pin "J3") (pinfunction "RAS#_J3") (pintype "input"))
      (node (ref "U7") (pin "P4") (pinfunction "PS_DDR_RAS_B_502_P4") (pintype "input"))
    )
    (net (code "155") (name "DDR_RESET") (class "Default")
      (node (ref "R21") (pin "2") (pinfunction "2_2") (pintype "input"))
      (node (ref "U5") (pin "T2") (pinfunction "RESET#_T2") (pintype "input"))
      (node (ref "U7") (pin "B4") (pinfunction "PS_DDR_DRST_B_502_B4") (pintype "input"))
    )
    (net (code "156") (name "DDR_WE") (class "Default")
      (node (ref "RN4") (pin "4") (pinfunction "4_4") (pintype "input"))
      (node (ref "U5") (pin "L3") (pinfunction "WE#_L3") (pintype "input"))
      (node (ref "U7") (pin "M5") (pinfunction "PS_DDR_WE_B_502_M5") (pintype "input"))
    )
    (net (code "157") (name "DONE") (class "Default")
      (node (ref "R77") (pin "2") (pinfunction "2_2") (pintype "input"))
      (node (ref "R78") (pin "2") (pinfunction "2_2") (pintype "input"))
      (node (ref "U7") (pin "R11") (pinfunction "DONE_0_R11") (pintype "input"))
    )
    (net (code "158") (name "ETH_RXCTL") (class "Default")
      (node (ref "U7") (pin "D13") (pinfunction "PS_MIO27_501_D13") (pintype "input"))
    )
    (net (code "159") (name "ETH_RXD0") (class "Default")
      (node (ref "U7") (pin "D11") (pinfunction "PS_MIO23_501_D11") (pintype "input"))
    )
    (net (code "160") (name "ETH_RXD1") (class "Default")
      (node (ref "U7") (pin "A16") (pinfunction "PS_MIO24_501_A16") (pintype "input"))
    )
    (net (code "161") (name "ETH_RXD2") (class "Default")
      (node (ref "U7") (pin "F15") (pinfunction "PS_MIO25_501_F15") (pintype "input"))
    )
    (net (code "162") (name "ETH_RXD3") (class "Default")
      (node (ref "U7") (pin "A15") (pinfunction "PS_MIO26_501_A15") (pintype "input"))
    )
    (net (code "163") (name "ETH_RX_CLK") (class "Default")
      (node (ref "U7") (pin "B17") (pinfunction "PS_MIO22_501_B17") (pintype "input"))
    )
    (net (code "164") (name "ETH_TXCTL") (class "Default")
      (node (ref "U7") (pin "F14") (pinfunction "PS_MIO21_501_F14") (pintype "input"))
    )
    (net (code "165") (name "ETH_TXD0") (class "Default")
      (node (ref "U7") (pin "E14") (pinfunction "PS_MIO17_501_E14") (pintype "input"))
    )
    (net (code "166") (name "ETH_TXD1") (class "Default")
      (node (ref "U7") (pin "B18") (pinfunction "PS_MIO18_501_B18") (pintype "input"))
    )
    (net (code "167") (name "ETH_TXD2") (class "Default")
      (node (ref "U7") (pin "D10") (pinfunction "PS_MIO19_501_D10") (pintype "input"))
    )
    (net (code "168") (name "ETH_TXD3") (class "Default")
      (node (ref "U7") (pin "A17") (pinfunction "PS_MIO20_501_A17") (pintype "input"))
    )
    (net (code "169") (name "ETH_TX_CLK") (class "Default")
      (node (ref "U7") (pin "A19") (pinfunction "PS_MIO16_501_A19") (pintype "input"))
    )
    (net (code "170") (name "GND") (class "Default")
      (node (ref "C1") (pin "2") (pinfunction "2_2") (pintype "input"))
      (node (ref "C10") (pin "2") (pinfunction "2_2") (pintype "input"))
      (node (ref "C11") (pin "2") (pinfunction "2_2") (pintype "input"))
      (node (ref "C12") (pin "2") (pinfunction "2_2") (pintype "input"))
      (node (ref "C13") (pin "2") (pinfunction "2_2") (pintype "input"))
      (node (ref "C14") (pin "2") (pinfunction "2_2") (pintype "input"))
      (node (ref "C15") (pin "1") (pinfunction "1_1") (pintype "input"))
      (node (ref "C16") (pin "1") (pinfunction "1_1") (pintype "input"))
      (node (ref "C17") (pin "1") (pinfunction "1_1") (pintype "input"))
      (node (ref "C18") (pin "1") (pinfunction "1_1") (pintype "input"))
      (node (ref "C19") (pin "1") (pinfunction "1_1") (pintype "input"))
      (node (ref "C2") (pin "2") (pinfunction "2_2") (pintype "input"))
      (node (ref "C20") (pin "1") (pinfunction "1_1") (pintype "input"))
      (node (ref "C21") (pin "1") (pinfunction "1_1") (pintype "input"))
      (node (ref "C22") (pin "1") (pinfunction "1_1") (pintype "input"))
      (node (ref "C23") (pin "1") (pinfunction "1_1") (pintype "input"))
      (node (ref "C24") (pin "1") (pinfunction "1_1") (pintype "input"))
      (node (ref "C25") (pin "1") (pinfunction "1_1") (pintype "input"))
      (node (ref "C26") (pin "1") (pinfunction "1_1") (pintype "input"))
      (node (ref "C3") (pin "2") (pinfunction "2_2") (pintype "input"))
      (node (ref "C30") (pin "1") (pinfunction "1_1") (pintype "input"))
      (node (ref "C31") (pin "1") (pinfunction "1_1") (pintype "input"))
      (node (ref "C32") (pin "1") (pinfunction "1_1") (pintype "input"))
      (node (ref "C33") (pin "1") (pinfunction "1_1") (pintype "input"))
      (node (ref "C35") (pin "2") (pinfunction "2_2") (pintype "input"))
      (node (ref "C37") (pin "2") (pinfunction "2_2") (pintype "input"))
      (node (ref "C38") (pin "2") (pinfunction "2_2") (pintype "input"))
      (node (ref "C39") (pin "2") (pinfunction "2_2") (pintype "input"))
      (node (ref "C40") (pin "2") (pinfunction "2_2") (pintype "input"))
      (node (ref "C41") (pin "2") (pinfunction "2_2") (pintype "input"))
      (node (ref "C43") (pin "2") (pinfunction "2_2") (pintype "input"))
      (node (ref "C44") (pin "2") (pinfunction "2_2") (pintype "input"))
      (node (ref "C45") (pin "2") (pinfunction "2_2") (pintype "input"))
      (node (ref "C46") (pin "2") (pinfunction "2_2") (pintype "input"))
      (node (ref "C47") (pin "1") (pinfunction "1_1") (pintype "input"))
      (node (ref "C48") (pin "2") (pinfunction "2_2") (pintype "input"))
      (node (ref "C49") (pin "2") (pinfunction "2_2") (pintype "input"))
      (node (ref "C5") (pin "2") (pinfunction "2_2") (pintype "input"))
      (node (ref "C50") (pin "2") (pinfunction "2_2") (pintype "input"))
      (node (ref "C51") (pin "2") (pinfunction "2_2") (pintype "input"))
      (node (ref "C53") (pin "2") (pinfunction "2_2") (pintype "input"))
      (node (ref "C54") (pin "1") (pinfunction "1_1") (pintype "input"))
      (node (ref "C55") (pin "2") (pinfunction "2_2") (pintype "input"))
      (node (ref "C56") (pin "1") (pinfunction "1_1") (pintype "input"))
      (node (ref "C57") (pin "1") (pinfunction "1_1") (pintype "input"))
      (node (ref "C58") (pin "1") (pinfunction "1_1") (pintype "input"))
      (node (ref "C59") (pin "1") (pinfunction "1_1") (pintype "input"))
      (node (ref "C6") (pin "2") (pinfunction "2_2") (pintype "input"))
      (node (ref "C60") (pin "1") (pinfunction "1_1") (pintype "input"))
      (node (ref "C61") (pin "1") (pinfunction "1_1") (pintype "input"))
      (node (ref "C62") (pin "1") (pinfunction "1_1") (pintype "input"))
      (node (ref "C63") (pin "1") (pinfunction "1_1") (pintype "input"))
      (node (ref "C64") (pin "1") (pinfunction "1_1") (pintype "input"))
      (node (ref "C65") (pin "1") (pinfunction "1_1") (pintype "input"))
      (node (ref "C66") (pin "1") (pinfunction "1_1") (pintype "input"))
      (node (ref "C67") (pin "1") (pinfunction "1_1") (pintype "input"))
      (node (ref "C68") (pin "1") (pinfunction "1_1") (pintype "input"))
      (node (ref "C69") (pin "1") (pinfunction "1_1") (pintype "input"))
      (node (ref "C7") (pin "2") (pinfunction "2_2") (pintype "input"))
      (node (ref "C70") (pin "1") (pinfunction "1_1") (pintype "input"))
      (node (ref "C71") (pin "1") (pinfunction "1_1") (pintype "input"))
      (node (ref "C73") (pin "1") (pinfunction "1_1") (pintype "input"))
      (node (ref "C74") (pin "1") (pinfunction "1_1") (pintype "input"))
      (node (ref "C75") (pin "1") (pinfunction "1_1") (pintype "input"))
      (node (ref "C76") (pin "1") (pinfunction "1_1") (pintype "input"))
      (node (ref "C8") (pin "2") (pinfunction "2_2") (pintype "input"))
      (node (ref "C80") (pin "2") (pinfunction "2_2") (pintype "input"))
      (node (ref "C81") (pin "2") (pinfunction "2_2") (pintype "input"))
      (node (ref "C82") (pin "1") (pinfunction "1_1") (pintype "input"))
      (node (ref "C9") (pin "2") (pinfunction "2_2") (pintype "input"))
      (node (ref "CN1") (pin "1") (pinfunction "1_1") (pintype "input"))
      (node (ref "CN1") (pin "19") (pinfunction "19_19") (pintype "input"))
      (node (ref "CN1") (pin "2") (pinfunction "2_2") (pintype "input"))
      (node (ref "CN1") (pin "20") (pinfunction "20_20") (pintype "input"))
      (node (ref "CN1") (pin "37") (pinfunction "37_37") (pintype "input"))
      (node (ref "CN1") (pin "38") (pinfunction "38_38") (pintype "input"))
      (node (ref "CN1") (pin "55") (pinfunction "55_55") (pintype "input"))
      (node (ref "CN1") (pin "56") (pinfunction "56_56") (pintype "input"))
      (node (ref "CN2") (pin "1") (pinfunction "1_1") (pintype "input"))
      (node (ref "CN2") (pin "19") (pinfunction "19_19") (pintype "input"))
      (node (ref "CN2") (pin "2") (pinfunction "2_2") (pintype "input"))
      (node (ref "CN2") (pin "20") (pinfunction "20_20") (pintype "input"))
      (node (ref "CN2") (pin "37") (pinfunction "37_37") (pintype "input"))
      (node (ref "CN2") (pin "38") (pinfunction "38_38") (pintype "input"))
      (node (ref "CN2") (pin "55") (pinfunction "55_55") (pintype "input"))
      (node (ref "CN2") (pin "56") (pinfunction "56_56") (pintype "input"))
      (node (ref "CN3") (pin "2") (pinfunction "2_2") (pintype "unspecified"))
      (node (ref "L1") (pin "2") (pinfunction "GND_2") (pintype "input"))
      (node (ref "L1") (pin "4") (pinfunction "GND_4") (pintype "input"))
      (node (ref "L2") (pin "2") (pinfunction "GND_2") (pintype "input"))
      (node (ref "L2") (pin "4") (pinfunction "GND_4") (pintype "input"))
      (node (ref "L4") (pin "2") (pinfunction "GND_2") (pintype "input"))
      (node (ref "L4") (pin "4") (pinfunction "GND_4") (pintype "input"))
      (node (ref "L5") (pin "2") (pinfunction "GND_2") (pintype "input"))
      (node (ref "L5") (pin "4") (pinfunction "GND_4") (pintype "input"))
      (node (ref "LED1") (pin "1") (pinfunction "C_1") (pintype "input"))
      (node (ref "LED2") (pin "1") (pinfunction "C_1") (pintype "input"))
      (node (ref "LED3") (pin "1") (pinfunction "C_1") (pintype "input"))
      (node (ref "R13") (pin "2") (pinfunction "2_2") (pintype "input"))
      (node (ref "R15") (pin "2") (pinfunction "2_2") (pintype "input"))
      (node (ref "R18") (pin "2") (pinfunction "2_2") (pintype "input"))
      (node (ref "R19") (pin "1") (pinfunction "1_1") (pintype "input"))
      (node (ref "R21") (pin "1") (pinfunction "1_1") (pintype "input"))
      (node (ref "R24") (pin "2") (pinfunction "2_2") (pintype "input"))
      (node (ref "R26") (pin "2") (pinfunction "2_2") (pintype "input"))
      (node (ref "R3") (pin "2") (pinfunction "2_2") (pintype "input"))
      (node (ref "R30") (pin "1") (pinfunction "1_1") (pintype "input"))
      (node (ref "R31") (pin "1") (pinfunction "1_1") (pintype "input"))
      (node (ref "R32") (pin "1") (pinfunction "1_1") (pintype "input"))
      (node (ref "R33") (pin "1") (pinfunction "1_1") (pintype "input"))
      (node (ref "R37") (pin "2") (pinfunction "2_2") (pintype "input"))
      (node (ref "R41") (pin "1") (pinfunction "1_1") (pintype "input"))
      (node (ref "R7") (pin "2") (pinfunction "2_2") (pintype "input"))
      (node (ref "R79") (pin "1") (pinfunction "1_1") (pintype "input"))
      (node (ref "R80") (pin "1") (pinfunction "1_1") (pintype "input"))
      (node (ref "R9") (pin "2") (pinfunction "2_2") (pintype "input"))
      (node (ref "SW1") (pin "1") (pinfunction "A1_1") (pintype "input"))
      (node (ref "SW1") (pin "2") (pinfunction "A2_2") (pintype "input"))
      (node (ref "U1") (pin "3") (pinfunction "GND_3") (pintype "input"))
      (node (ref "U1") (pin "9") (pinfunction "EP_9") (pintype "input"))
      (node (ref "U10") (pin "4") (pinfunction "GND_4") (pintype "input"))
      (node (ref "U10") (pin "9") (pinfunction "EP_9") (pintype "input"))
      (node (ref "U11") (pin "3") (pinfunction "VSS_3") (pintype "input"))
      (node (ref "U2") (pin "3") (pinfunction "GND_3") (pintype "input"))
      (node (ref "U2") (pin "9") (pinfunction "EP_9") (pintype "input"))
      (node (ref "U3") (pin "3") (pinfunction "GND_3") (pintype "input"))
      (node (ref "U3") (pin "9") (pinfunction "EP_9") (pintype "input"))
      (node (ref "U4") (pin "3") (pinfunction "GND_3") (pintype "input"))
      (node (ref "U4") (pin "9") (pinfunction "EP_9") (pintype "input"))
      (node (ref "U5") (pin "A9") (pinfunction "VSS_A9") (pintype "input"))
      (node (ref "U5") (pin "B1") (pinfunction "VSSQ_B1") (pintype "input"))
      (node (ref "U5") (pin "B3") (pinfunction "VSS_B3") (pintype "input"))
      (node (ref "U5") (pin "B9") (pinfunction "VSSQ_B9") (pintype "input"))
      (node (ref "U5") (pin "D1") (pinfunction "VSSQ_D1") (pintype "input"))
      (node (ref "U5") (pin "D8") (pinfunction "VSSQ_D8") (pintype "input"))
      (node (ref "U5") (pin "E1") (pinfunction "VSS_E1") (pintype "input"))
      (node (ref "U5") (pin "E2") (pinfunction "VSSQ_E2") (pintype "input"))
      (node (ref "U5") (pin "E8") (pinfunction "VSSQ_E8") (pintype "input"))
      (node (ref "U5") (pin "F9") (pinfunction "VSSQ_F9") (pintype "input"))
      (node (ref "U5") (pin "G1") (pinfunction "VSSQ_G1") (pintype "input"))
      (node (ref "U5") (pin "G8") (pinfunction "VSS_G8") (pintype "input"))
      (node (ref "U5") (pin "G9") (pinfunction "VSSQ_G9") (pintype "input"))
      (node (ref "U5") (pin "J2") (pinfunction "VSS_J2") (pintype "input"))
      (node (ref "U5") (pin "J8") (pinfunction "VSS_J8") (pintype "input"))
      (node (ref "U5") (pin "M1") (pinfunction "VSS_M1") (pintype "input"))
      (node (ref "U5") (pin "M9") (pinfunction "VSS_M9") (pintype "input"))
      (node (ref "U5") (pin "P1") (pinfunction "VSS_P1") (pintype "input"))
      (node (ref "U5") (pin "P9") (pinfunction "VSS_P9") (pintype "input"))
      (node (ref "U5") (pin "T1") (pinfunction "VSS_T1") (pintype "input"))
      (node (ref "U5") (pin "T9") (pinfunction "VSS_T9") (pintype "input"))
      (node (ref "U7") (pin "A18") (pinfunction "GND_A18") (pintype "input"))
      (node (ref "U7") (pin "A8") (pinfunction "GND_A8") (pintype "input"))
      (node (ref "U7") (pin "B1") (pinfunction "GND_B1") (pintype "input"))
      (node (ref "U7") (pin "B11") (pinfunction "GND_B11") (pintype "input"))
      (node (ref "U7") (pin "C14") (pinfunction "GND_C14") (pintype "input"))
      (node (ref "U7") (pin "C4") (pinfunction "GND_C4") (pintype "input"))
      (node (ref "U7") (pin "C9") (pinfunction "GND_C9") (pintype "input"))
      (node (ref "U7") (pin "D17") (pinfunction "GND_D17") (pintype "input"))
      (node (ref "U7") (pin "E10") (pinfunction "GND_E10") (pintype "input"))
      (node (ref "U7") (pin "E20") (pinfunction "GND_E20") (pintype "input"))
      (node (ref "U7") (pin "F10") (pinfunction "RSVDGND_F10") (pintype "input"))
      (node (ref "U7") (pin "F3") (pinfunction "GND_F3") (pintype "input"))
      (node (ref "U7") (pin "F7") (pinfunction "GND_F7") (pintype "input"))
      (node (ref "U7") (pin "G10") (pinfunction "GND_G10") (pintype "input"))
      (node (ref "U7") (pin "G12") (pinfunction "GND_G12") (pintype "input"))
      (node (ref "U7") (pin "G16") (pinfunction "GND_G16") (pintype "input"))
      (node (ref "U7") (pin "H11") (pinfunction "GND_H11") (pintype "input"))
      (node (ref "U7") (pin "H13") (pinfunction "GND_H13") (pintype "input"))
      (node (ref "U7") (pin "H19") (pinfunction "GND_H19") (pintype "input"))
      (node (ref "U7") (pin "H7") (pinfunction "GND_H7") (pintype "input"))
      (node (ref "U7") (pin "H9") (pinfunction "GND_H9") (pintype "input"))
      (node (ref "U7") (pin "J10") (pinfunction "GNDADC_0_J10") (pintype "input"))
      (node (ref "U7") (pin "J12") (pinfunction "GND_J12") (pintype "input"))
      (node (ref "U7") (pin "J2") (pinfunction "GND_J2") (pintype "input"))
      (node (ref "U7") (pin "J8") (pinfunction "GND_J8") (pintype "input"))
      (node (ref "U7") (pin "K10") (pinfunction "VREFN_0_K10") (pintype "input"))
      (node (ref "U7") (pin "K11") (pinfunction "GND_K11") (pintype "input"))
      (node (ref "U7") (pin "K13") (pinfunction "GND_K13") (pintype "input"))
      (node (ref "U7") (pin "K15") (pinfunction "GND_K15") (pintype "input"))
      (node (ref "U7") (pin "K5") (pinfunction "GND_K5") (pintype "input"))
      (node (ref "U7") (pin "K7") (pinfunction "GND_K7") (pintype "input"))
      (node (ref "U7") (pin "L12") (pinfunction "GND_L12") (pintype "input"))
      (node (ref "U7") (pin "L18") (pinfunction "GND_L18") (pintype "input"))
      (node (ref "U7") (pin "L8") (pinfunction "GND_L8") (pintype "input"))
      (node (ref "U7") (pin "L9") (pinfunction "VREFP_0_L9") (pintype "input"))
      (node (ref "U7") (pin "M1") (pinfunction "GND_M1") (pintype "input"))
      (node (ref "U7") (pin "M10") (pinfunction "DXN_0_M10") (pintype "input"))
      (node (ref "U7") (pin "M11") (pinfunction "GND_M11") (pintype "input"))
      (node (ref "U7") (pin "M13") (pinfunction "GND_M13") (pintype "input"))
      (node (ref "U7") (pin "M7") (pinfunction "GND_M7") (pintype "input"))
      (node (ref "U7") (pin "M9") (pinfunction "DXP_0_M9") (pintype "input"))
      (node (ref "U7") (pin "N10") (pinfunction "GND_N10") (pintype "input"))
      (node (ref "U7") (pin "N12") (pinfunction "GND_N12") (pintype "input"))
      (node (ref "U7") (pin "N14") (pinfunction "GND_N14") (pintype "input"))
      (node (ref "U7") (pin "N4") (pinfunction "GND_N4") (pintype "input"))
      (node (ref "U7") (pin "N8") (pinfunction "GND_N8") (pintype "input"))
      (node (ref "U7") (pin "P11") (pinfunction "GND_P11") (pintype "input"))
      (node (ref "U7") (pin "P13") (pinfunction "GND_P13") (pintype "input"))
      (node (ref "U7") (pin "P17") (pinfunction "GND_P17") (pintype "input"))
      (node (ref "U7") (pin "P7") (pinfunction "GND_P7") (pintype "input"))
      (node (ref "U7") (pin "P9") (pinfunction "GND_P9") (pintype "input"))
      (node (ref "U7") (pin "R12") (pinfunction "GND_R12") (pintype "input"))
      (node (ref "U7") (pin "R20") (pinfunction "GND_R20") (pintype "input"))
      (node (ref "U7") (pin "R8") (pinfunction "GND_R8") (pintype "input"))
      (node (ref "U7") (pin "T13") (pinfunction "GND_T13") (pintype "input"))
      (node (ref "U7") (pin "T3") (pinfunction "GND_T3") (pintype "input"))
      (node (ref "U7") (pin "T7") (pinfunction "GND_T7") (pintype "input"))
      (node (ref "U7") (pin "U16") (pinfunction "GND_U16") (pintype "input"))
      (node (ref "U7") (pin "U6") (pinfunction "GND_U6") (pintype "input"))
      (node (ref "U7") (pin "V19") (pinfunction "GND_V19") (pintype "input"))
      (node (ref "U7") (pin "V9") (pinfunction "GND_V9") (pintype "input"))
      (node (ref "U7") (pin "W12") (pinfunction "GND_W12") (pintype "input"))
      (node (ref "U7") (pin "W2") (pinfunction "GND_W2") (pintype "input"))
      (node (ref "U7") (pin "Y15") (pinfunction "GND_Y15") (pintype "input"))
      (node (ref "U7") (pin "Y5") (pinfunction "GND_Y5") (pintype "input"))
      (node (ref "U8") (pin "11") (pinfunction "GND_11") (pintype "input"))
      (node (ref "U8") (pin "2") (pinfunction "GND_2") (pintype "input"))
      (node (ref "U8") (pin "25") (pinfunction "EP_25") (pintype "input"))
      (node (ref "U9") (pin "17") (pinfunction "EP_17") (pintype "unspecified"))
      (node (ref "U9") (pin "2") (pinfunction "GND_2") (pintype "unspecified"))
      (node (ref "USB1") (pin "1") (pinfunction "EP_1") (pintype "input"))
      (node (ref "USB1") (pin "2") (pinfunction "EP_2") (pintype "input"))
      (node (ref "USB1") (pin "3") (pinfunction "EP_3") (pintype "input"))
      (node (ref "USB1") (pin "4") (pinfunction "EP_4") (pintype "input"))
      (node (ref "USB1") (pin "A1") (pinfunction "GND_A1") (pintype "input"))
      (node (ref "USB1") (pin "A12") (pinfunction "GND_A12") (pintype "input"))
      (node (ref "USB1") (pin "B1") (pinfunction "GND_B1") (pintype "input"))
      (node (ref "USB1") (pin "B12") (pinfunction "GND_B12") (pintype "input"))
      (node (ref "X1") (pin "2") (pinfunction "GND_2") (pintype "input"))
      (node (ref "X2") (pin "2") (pinfunction "GND_2") (pintype "unspecified"))
    )
    (net (code "171") (name "JTAG_TCK") (class "Default")
      (node (ref "CN1") (pin "3") (pinfunction "3_3") (pintype "input"))
      (node (ref "CN3") (pin "3") (pinfunction "3_3") (pintype "unspecified"))
      (node (ref "R87") (pin "1") (pinfunction "1_1") (pintype "input"))
      (node (ref "U7") (pin "F9") (pinfunction "TCK_0_F9") (pintype "input"))
    )
    (net (code "172") (name "JTAG_TDI") (class "Default")
      (node (ref "CN1") (pin "6") (pinfunction "6_6") (pintype "input"))
      (node (ref "CN3") (pin "5") (pinfunction "5_5") (pintype "unspecified"))
      (node (ref "R85") (pin "1") (pinfunction "1_1") (pintype "input"))
      (node (ref "U7") (pin "G6") (pinfunction "TDI_0_G6") (pintype "input"))
    )
    (net (code "173") (name "JTAG_TDO") (class "Default")
      (node (ref "CN1") (pin "5") (pinfunction "5_5") (pintype "input"))
      (node (ref "CN3") (pin "4") (pinfunction "4_4") (pintype "unspecified"))
      (node (ref "R86") (pin "1") (pinfunction "1_1") (pintype "input"))
      (node (ref "U7") (pin "F6") (pinfunction "TDO_0_F6") (pintype "input"))
    )
    (net (code "174") (name "JTAG_TMS") (class "Default")
      (node (ref "CN1") (pin "4") (pinfunction "4_4") (pintype "input"))
      (node (ref "CN3") (pin "6") (pinfunction "6_6") (pintype "unspecified"))
      (node (ref "R84") (pin "1") (pinfunction "1_1") (pintype "input"))
      (node (ref "U7") (pin "J6") (pinfunction "TMS_0_J6") (pintype "input"))
    )
    (net (code "175") (name "MIO7") (class "Default")
      (node (ref "R33") (pin "2") (pinfunction "2_2") (pintype "input"))
      (node (ref "U7") (pin "D8") (pinfunction "PS_MIO7_500_D8") (pintype "input"))
    )
    (net (code "176") (name "MIO8") (class "Default")
      (node (ref "R28") (pin "2") (pinfunction "2_2") (pintype "input"))
      (node (ref "U7") (pin "D5") (pinfunction "PS_MIO8_500_D5") (pintype "input"))
    )
    (net (code "177") (name "Net-(L1-OUT)") (class "Default")
      (node (ref "C7") (pin "1") (pinfunction "1_1") (pintype "input"))
      (node (ref "L1") (pin "3") (pinfunction "OUT_3") (pintype "input"))
      (node (ref "R8") (pin "1") (pinfunction "1_1") (pintype "input"))
      (node (ref "U1") (pin "4") (pinfunction "VOUT_4") (pintype "input"))
      (node (ref "U1") (pin "5") (pinfunction "VOUT_5") (pintype "input"))
    )
    (net (code "178") (name "Net-(L2-OUT)") (class "Default")
      (node (ref "C8") (pin "1") (pinfunction "1_1") (pintype "input"))
      (node (ref "L2") (pin "3") (pinfunction "OUT_3") (pintype "input"))
      (node (ref "R10") (pin "1") (pinfunction "1_1") (pintype "input"))
      (node (ref "U2") (pin "4") (pinfunction "VOUT_4") (pintype "input"))
      (node (ref "U2") (pin "5") (pinfunction "VOUT_5") (pintype "input"))
    )
    (net (code "179") (name "Net-(L4-OUT)") (class "Default")
      (node (ref "C13") (pin "1") (pinfunction "1_1") (pintype "input"))
      (node (ref "L4") (pin "3") (pinfunction "OUT_3") (pintype "input"))
      (node (ref "R14") (pin "1") (pinfunction "1_1") (pintype "input"))
      (node (ref "U3") (pin "4") (pinfunction "VOUT_4") (pintype "input"))
      (node (ref "U3") (pin "5") (pinfunction "VOUT_5") (pintype "input"))
    )
    (net (code "180") (name "Net-(L5-OUT)") (class "Default")
      (node (ref "C14") (pin "1") (pinfunction "1_1") (pintype "input"))
      (node (ref "L5") (pin "3") (pinfunction "OUT_3") (pintype "input"))
      (node (ref "R16") (pin "1") (pinfunction "1_1") (pintype "input"))
      (node (ref "U4") (pin "4") (pinfunction "VOUT_4") (pintype "input"))
      (node (ref "U4") (pin "5") (pinfunction "VOUT_5") (pintype "input"))
    )
    (net (code "181") (name "Net-(LED1-A)") (class "Default")
      (node (ref "LED1") (pin "2") (pinfunction "A_2") (pintype "input"))
      (node (ref "R77") (pin "1") (pinfunction "1_1") (pintype "input"))
    )
    (net (code "182") (name "Net-(LED2-A)") (class "Default")
      (node (ref "LED2") (pin "2") (pinfunction "A_2") (pintype "input"))
      (node (ref "R81") (pin "1") (pinfunction "1_1") (pintype "input"))
    )
    (net (code "183") (name "Net-(LED3-A)") (class "Default")
      (node (ref "LED3") (pin "2") (pinfunction "A_2") (pintype "input"))
      (node (ref "R82") (pin "1") (pinfunction "1_1") (pintype "input"))
    )
    (net (code "184") (name "Net-(SW1-B1)") (class "Default")
      (node (ref "R74") (pin "1") (pinfunction "1_1") (pintype "input"))
      (node (ref "R75") (pin "1") (pinfunction "1_1") (pintype "input"))
      (node (ref "SW1") (pin "4") (pinfunction "B1_4") (pintype "input"))
    )
    (net (code "185") (name "Net-(SW1-B2)") (class "Default")
      (node (ref "R73") (pin "1") (pinfunction "1_1") (pintype "input"))
      (node (ref "R76") (pin "1") (pinfunction "1_1") (pintype "input"))
      (node (ref "SW1") (pin "3") (pinfunction "B2_3") (pintype "input"))
    )
    (net (code "186") (name "Net-(U1-FB)") (class "Default")
      (node (ref "R7") (pin "1") (pinfunction "1_1") (pintype "input"))
      (node (ref "R8") (pin "2") (pinfunction "2_2") (pintype "input"))
      (node (ref "U1") (pin "6") (pinfunction "FB_6") (pintype "input"))
    )
    (net (code "187") (name "Net-(U1-SS{slash}TR)") (class "Default")
      (node (ref "C2") (pin "1") (pinfunction "1_1") (pintype "input"))
      (node (ref "U1") (pin "8") (pinfunction "SS/TR_8") (pintype "input"))
    )
    (net (code "188") (name "Net-(U2-FB)") (class "Default")
      (node (ref "R10") (pin "2") (pinfunction "2_2") (pintype "input"))
      (node (ref "R9") (pin "1") (pinfunction "1_1") (pintype "input"))
      (node (ref "U2") (pin "6") (pinfunction "FB_6") (pintype "input"))
    )
    (net (code "189") (name "Net-(U2-SS{slash}TR)") (class "Default")
      (node (ref "C3") (pin "1") (pinfunction "1_1") (pintype "input"))
      (node (ref "U2") (pin "8") (pinfunction "SS/TR_8") (pintype "input"))
    )
    (net (code "190") (name "Net-(U3-FB)") (class "Default")
      (node (ref "R13") (pin "1") (pinfunction "1_1") (pintype "input"))
      (node (ref "R14") (pin "2") (pinfunction "2_2") (pintype "input"))
      (node (ref "U3") (pin "6") (pinfunction "FB_6") (pintype "input"))
    )
    (net (code "191") (name "Net-(U3-SS{slash}TR)") (class "Default")
      (node (ref "C9") (pin "1") (pinfunction "1_1") (pintype "input"))
      (node (ref "U3") (pin "8") (pinfunction "SS/TR_8") (pintype "input"))
    )
    (net (code "192") (name "Net-(U4-FB)") (class "Default")
      (node (ref "R15") (pin "1") (pinfunction "1_1") (pintype "input"))
      (node (ref "R16") (pin "2") (pinfunction "2_2") (pintype "input"))
      (node (ref "U4") (pin "6") (pinfunction "FB_6") (pintype "input"))
    )
    (net (code "193") (name "Net-(U4-SS{slash}TR)") (class "Default")
      (node (ref "C10") (pin "1") (pinfunction "1_1") (pintype "input"))
      (node (ref "U4") (pin "8") (pinfunction "SS/TR_8") (pintype "input"))
    )
    (net (code "194") (name "Net-(U5-ZQ)") (class "Default")
      (node (ref "R18") (pin "1") (pinfunction "1_1") (pintype "input"))
      (node (ref "U5") (pin "L8") (pinfunction "ZQ_L8") (pintype "input"))
    )
    (net (code "195") (name "Net-(U7A-PS_MIO6_500)") (class "Default")
      (node (ref "R39") (pin "1") (pinfunction "1_1") (pintype "input"))
      (node (ref "U7") (pin "A5") (pinfunction "PS_MIO6_500_A5") (pintype "input"))
    )
    (net (code "196") (name "Net-(U7A-PS_POR_B_500)") (class "Default")
      (node (ref "R36") (pin "2") (pinfunction "2_2") (pintype "input"))
      (node (ref "U7") (pin "C7") (pinfunction "PS_POR_B_500_C7") (pintype "input"))
    )
    (net (code "197") (name "Net-(U7B-PS_MIO40_501)") (class "Default")
      (node (ref "R40") (pin "1") (pinfunction "1_1") (pintype "input"))
      (node (ref "U7") (pin "D14") (pinfunction "PS_MIO40_501_D14") (pintype "input"))
    )
    (net (code "198") (name "Net-(U7B-PS_MIO_VREF_501)") (class "Default")
      (node (ref "C48") (pin "1") (pinfunction "1_1") (pintype "input"))
      (node (ref "R37") (pin "1") (pinfunction "1_1") (pintype "input"))
      (node (ref "R38") (pin "2") (pinfunction "2_2") (pintype "input"))
      (node (ref "U7") (pin "E11") (pinfunction "PS_MIO_VREF_501_E11") (pintype "input"))
    )
    (net (code "199") (name "Net-(U7B-PS_SRST_B_501)") (class "Default")
      (node (ref "R34") (pin "1") (pinfunction "1_1") (pintype "input"))
      (node (ref "U7") (pin "B10") (pinfunction "PS_SRST_B_501_B10") (pintype "input"))
    )
    (net (code "200") (name "Net-(U7C-INIT_B_0)") (class "Default")
      (node (ref "R1") (pin "2") (pinfunction "2_2") (pintype "input"))
      (node (ref "U7") (pin "R10") (pinfunction "INIT_B_0_R10") (pintype "input"))
    )
    (net (code "201") (name "Net-(U7C-PROGRAM_B_0)") (class "Default")
      (node (ref "R2") (pin "2") (pinfunction "2_2") (pintype "input"))
      (node (ref "U7") (pin "L6") (pinfunction "PROGRAM_B_0_L6") (pintype "input"))
    )
    (net (code "202") (name "Net-(U7E-PS_DDR_VRN_502)") (class "Default")
      (node (ref "R20") (pin "2") (pinfunction "2_2") (pintype "input"))
      (node (ref "U7") (pin "G5") (pinfunction "PS_DDR_VRN_502_G5") (pintype "input"))
    )
    (net (code "203") (name "Net-(U7E-PS_DDR_VRP_502)") (class "Default")
      (node (ref "R19") (pin "2") (pinfunction "2_2") (pintype "input"))
      (node (ref "U7") (pin "H5") (pinfunction "PS_DDR_VRP_502_H5") (pintype "input"))
    )
    (net (code "204") (name "Net-(U7F-PS_DDR_VREF0_502)") (class "Default")
      (node (ref "C1") (pin "1") (pinfunction "1_1") (pintype "input"))
      (node (ref "R3") (pin "1") (pinfunction "1_1") (pintype "input"))
      (node (ref "R6") (pin "2") (pinfunction "2_2") (pintype "input"))
      (node (ref "U7") (pin "H6") (pinfunction "PS_DDR_VREF0_502_H6") (pintype "input"))
      (node (ref "U7") (pin "P6") (pinfunction "PS_DDR_VREF1_502_P6") (pintype "input"))
    )
    (net (code "205") (name "Net-(U8-SEL)") (class "Default")
      (node (ref "R41") (pin "2") (pinfunction "2_2") (pintype "input"))
      (node (ref "U8") (pin "24") (pinfunction "SEL_24") (pintype "input"))
    )
    (net (code "206") (name "Net-(U9-V3)") (class "Default")
      (node (ref "C54") (pin "2") (pinfunction "2_2") (pintype "input"))
      (node (ref "U9") (pin "6") (pinfunction "V3_6") (pintype "unspecified"))
    )
    (net (code "207") (name "Net-(X1-OUT)") (class "Default")
      (node (ref "R27") (pin "1") (pinfunction "1_1") (pintype "input"))
      (node (ref "X1") (pin "3") (pinfunction "OUT_3") (pintype "input"))
    )
    (net (code "208") (name "Net-(X1-VCC)") (class "Default")
      (node (ref "C44") (pin "1") (pinfunction "1_1") (pintype "input"))
      (node (ref "C45") (pin "1") (pinfunction "1_1") (pintype "input"))
      (node (ref "L6") (pin "1") (pinfunction "1_1") (pintype "input"))
      (node (ref "X1") (pin "4") (pinfunction "VCC_4") (pintype "input"))
    )
    (net (code "209") (name "Net-(X2-VDD)") (class "Default")
      (node (ref "C80") (pin "1") (pinfunction "1_1") (pintype "input"))
      (node (ref "L7") (pin "1") (pinfunction "1_1") (pintype "input"))
      (node (ref "X2") (pin "4") (pinfunction "VDD_4") (pintype "unspecified"))
    )
    (net (code "210") (name "PG_1V0") (class "Default")
      (node (ref "R4") (pin "2") (pinfunction "2_2") (pintype "input"))
      (node (ref "U1") (pin "7") (pinfunction "PG_7") (pintype "input"))
      (node (ref "U2") (pin "1") (pinfunction "EN_1") (pintype "input"))
    )
    (net (code "211") (name "PG_1V5") (class "Default")
      (node (ref "R12") (pin "1") (pinfunction "1_1") (pintype "input"))
      (node (ref "U3") (pin "1") (pinfunction "EN_1") (pintype "input"))
      (node (ref "U4") (pin "7") (pinfunction "PG_7") (pintype "input"))
    )
    (net (code "212") (name "PG_1V8") (class "Default")
      (node (ref "R5") (pin "2") (pinfunction "2_2") (pintype "input"))
      (node (ref "U2") (pin "7") (pinfunction "PG_7") (pintype "input"))
      (node (ref "U4") (pin "1") (pinfunction "EN_1") (pintype "input"))
    )
    (net (code "213") (name "PG_3V3") (class "Default")
      (node (ref "R11") (pin "2") (pinfunction "2_2") (pintype "input"))
      (node (ref "R81") (pin "2") (pinfunction "2_2") (pintype "input"))
      (node (ref "U3") (pin "7") (pinfunction "PG_7") (pintype "input"))
    )
    (net (code "214") (name "PL_CLK") (class "Default")
      (node (ref "U7") (pin "U15") (pinfunction "IO_L11N_T1_SRCC_34_U15") (pintype "input"))
      (node (ref "X2") (pin "3") (pinfunction "OUT_3") (pintype "unspecified"))
    )
    (net (code "215") (name "PS_CLK") (class "Default")
      (node (ref "R27") (pin "2") (pinfunction "2_2") (pintype "input"))
      (node (ref "U7") (pin "E7") (pinfunction "PS_CLK_500_E7") (pintype "input"))
    )
    (net (code "216") (name "QSPI_CLK") (class "Default")
      (node (ref "R32") (pin "2") (pinfunction "2_2") (pintype "input"))
      (node (ref "R39") (pin "2") (pinfunction "2_2") (pintype "input"))
      (node (ref "U10") (pin "6") (pinfunction "CLK_6") (pintype "input"))
    )
    (net (code "217") (name "QSPI_CS") (class "Default")
      (node (ref "R29") (pin "2") (pinfunction "2_2") (pintype "input"))
      (node (ref "U10") (pin "1") (pinfunction "/CS_1") (pintype "input"))
      (node (ref "U7") (pin "A7") (pinfunction "PS_MIO1_500_A7") (pintype "input"))
    )
    (net (code "218") (name "QSPI_D0") (class "Default")
      (node (ref "R30") (pin "2") (pinfunction "2_2") (pintype "input"))
      (node (ref "U10") (pin "5") (pinfunction "DI(IO0)_5") (pintype "input"))
      (node (ref "U7") (pin "B8") (pinfunction "PS_MIO2_500_B8") (pintype "input"))
    )
    (net (code "219") (name "QSPI_D1") (class "Default")
      (node (ref "R31") (pin "2") (pinfunction "2_2") (pintype "input"))
      (node (ref "U10") (pin "2") (pinfunction "DO(IO1)_2") (pintype "input"))
      (node (ref "U7") (pin "D6") (pinfunction "PS_MIO3_500_D6") (pintype "input"))
    )
    (net (code "220") (name "QSPI_D2") (class "Default")
      (node (ref "R74") (pin "2") (pinfunction "2_2") (pintype "input"))
      (node (ref "U10") (pin "3") (pinfunction "/WP(IO2)_3") (pintype "input"))
      (node (ref "U7") (pin "B7") (pinfunction "PS_MIO4_500_B7") (pintype "input"))
    )
    (net (code "221") (name "QSPI_D3") (class "Default")
      (node (ref "R73") (pin "2") (pinfunction "2_2") (pintype "input"))
      (node (ref "U10") (pin "7") (pinfunction "/HOLDor/RESET(IO3)_7") (pintype "input"))
      (node (ref "U7") (pin "A6") (pinfunction "PS_MIO5_500_A6") (pintype "input"))
    )
    (net (code "222") (name "SDO_CLK") (class "Default")
      (node (ref "U8") (pin "19") (pinfunction "CLKB0_19") (pintype "input"))
    )
    (net (code "223") (name "SDO_CMD") (class "Default")
      (node (ref "R43") (pin "1") (pinfunction "1_1") (pintype "input"))
      (node (ref "U8") (pin "20") (pinfunction "CMDB0_20") (pintype "input"))
    )
    (net (code "224") (name "SDO_D0") (class "Default")
      (node (ref "U8") (pin "18") (pinfunction "DAT0B0_18") (pintype "input"))
    )
    (net (code "225") (name "SDO_D1") (class "Default")
      (node (ref "U8") (pin "16") (pinfunction "DAT1B0_16") (pintype "input"))
    )
    (net (code "226") (name "SDO_D2") (class "Default")
      (node (ref "U8") (pin "23") (pinfunction "DAT2B0_23") (pintype "input"))
    )
    (net (code "227") (name "SDO_D3") (class "Default")
      (node (ref "R42") (pin "1") (pinfunction "1_1") (pintype "input"))
      (node (ref "U8") (pin "22") (pinfunction "DAT3B0_22") (pintype "input"))
    )
    (net (code "228") (name "SD_CD") (class "Default")
      (node (ref "U7") (pin "B14") (pinfunction "PS_MIO47_501_B14") (pintype "input"))
    )
    (net (code "229") (name "SD_CLK") (class "Default")
      (node (ref "CN2") (pin "8") (pinfunction "8_8") (pintype "input"))
      (node (ref "R40") (pin "2") (pinfunction "2_2") (pintype "input"))
      (node (ref "U8") (pin "9") (pinfunction "CLKA_9") (pintype "input"))
    )
    (net (code "230") (name "SD_CMD") (class "Default")
      (node (ref "CN2") (pin "3") (pinfunction "3_3") (pintype "input"))
      (node (ref "U7") (pin "C17") (pinfunction "PS_MIO41_501_C17") (pintype "input"))
      (node (ref "U8") (pin "4") (pinfunction "CMDA_4") (pintype "input"))
    )
    (net (code "231") (name "SD_D0") (class "Default")
      (node (ref "CN2") (pin "6") (pinfunction "6_6") (pintype "input"))
      (node (ref "U7") (pin "E12") (pinfunction "PS_MIO42_501_E12") (pintype "input"))
      (node (ref "U8") (pin "6") (pinfunction "DAT0A_6") (pintype "input"))
    )
    (net (code "232") (name "SD_D1") (class "Default")
      (node (ref "CN2") (pin "4") (pinfunction "4_4") (pintype "input"))
      (node (ref "U7") (pin "A9") (pinfunction "PS_MIO43_501_A9") (pintype "input"))
      (node (ref "U8") (pin "7") (pinfunction "DAT1A_7") (pintype "input"))
    )
    (net (code "233") (name "SD_D2") (class "Default")
      (node (ref "CN2") (pin "7") (pinfunction "7_7") (pintype "input"))
      (node (ref "U7") (pin "F13") (pinfunction "PS_MIO44_501_F13") (pintype "input"))
      (node (ref "U8") (pin "1") (pinfunction "DAT2A_1") (pintype "input"))
    )
    (net (code "234") (name "SD_D3") (class "Default")
      (node (ref "CN2") (pin "5") (pinfunction "5_5") (pintype "input"))
      (node (ref "U7") (pin "B15") (pinfunction "PS_MIO45_501_B15") (pintype "input"))
      (node (ref "U8") (pin "3") (pinfunction "DAT3A_3") (pintype "input"))
    )
    (net (code "235") (name "UART1_RX") (class "Default")
      (node (ref "U7") (pin "C12") (pinfunction "PS_MIO49_501_C12") (pintype "input"))
      (node (ref "U9") (pin "4") (pinfunction "TXD_4") (pintype "unspecified"))
    )
    (net (code "236") (name "UART1_TX") (class "Default")
      (node (ref "U7") (pin "B12") (pinfunction "PS_MIO48_501_B12") (pintype "input"))
      (node (ref "U9") (pin "5") (pinfunction "RXD_5") (pintype "unspecified"))
    )
    (net (code "237") (name "USB_5V") (class "Default")
      (node (ref "C55") (pin "1") (pinfunction "1_1") (pintype "input"))
      (node (ref "C57") (pin "2") (pinfunction "2_2") (pintype "input"))
      (node (ref "R83") (pin "1") (pinfunction "1_1") (pintype "input"))
      (node (ref "U9") (pin "3") (pinfunction "VDD5_3") (pintype "unspecified"))
      (node (ref "U9") (pin "9") (pinfunction "VBUS_9") (pintype "unspecified"))
      (node (ref "USB1") (pin "A4") (pinfunction "VBUS_A4") (pintype "input"))
      (node (ref "USB1") (pin "A9") (pinfunction "VBUS_A9") (pintype "input"))
      (node (ref "USB1") (pin "B4") (pinfunction "VBUS_B4") (pintype "input"))
      (node (ref "USB1") (pin "B9") (pinfunction "VBUS_B9") (pintype "input"))
    )
    (net (code "238") (name "USB_DN") (class "Default")
      (node (ref "U9") (pin "8") (pinfunction "UD-_8") (pintype "unspecified"))
      (node (ref "USB1") (pin "A7") (pinfunction "DN1_A7") (pintype "input"))
      (node (ref "USB1") (pin "B7") (pinfunction "DN2_B7") (pintype "input"))
    )
    (net (code "239") (name "USB_DP") (class "Default")
      (node (ref "U9") (pin "7") (pinfunction "UD+_7") (pintype "unspecified"))
      (node (ref "USB1") (pin "A6") (pinfunction "DP1_A6") (pintype "input"))
      (node (ref "USB1") (pin "B6") (pinfunction "DP2_B6") (pintype "input"))
    )
    (net (code "240") (name "VPLL") (class "Default")
      (node (ref "L3") (pin "1") (pinfunction "1_1") (pintype "input"))
      (node (ref "U7") (pin "G8") (pinfunction "VCCPLL_G8") (pintype "input"))
    )
    (net (code "241") (name "VREF_DDR") (class "Default")
      (node (ref "C36") (pin "2") (pinfunction "2_2") (pintype "input"))
      (node (ref "C37") (pin "1") (pinfunction "1_1") (pintype "input"))
      (node (ref "C42") (pin "2") (pinfunction "2_2") (pintype "input"))
      (node (ref "C43") (pin "1") (pinfunction "1_1") (pintype "input"))
      (node (ref "R25") (pin "2") (pinfunction "2_2") (pintype "input"))
      (node (ref "R26") (pin "1") (pinfunction "1_1") (pintype "input"))
      (node (ref "U5") (pin "H1") (pinfunction "VREFDQ_H1") (pintype "input"))
      (node (ref "U5") (pin "M8") (pinfunction "VREFCA_M8") (pintype "input"))
    )
    (net (code "242") (name "unconnected-(CN1-Pad7)") (class "Default")
      (node (ref "CN1") (pin "7") (pinfunction "7_7") (pintype "input+no_connect"))
    )
    (net (code "243") (name "unconnected-(CN1-Pad8)") (class "Default")
      (node (ref "CN1") (pin "8") (pinfunction "8_8") (pintype "input+no_connect"))
    )
    (net (code "244") (name "unconnected-(CN1-Pad9)") (class "Default")
      (node (ref "CN1") (pin "9") (pinfunction "9_9") (pintype "input+no_connect"))
    )
    (net (code "245") (name "unconnected-(CN1-Pad10)") (class "Default")
      (node (ref "CN1") (pin "10") (pinfunction "10_10") (pintype "input+no_connect"))
    )
    (net (code "246") (name "unconnected-(CN1-Pad11)") (class "Default")
      (node (ref "CN1") (pin "11") (pinfunction "11_11") (pintype "input+no_connect"))
    )
    (net (code "247") (name "unconnected-(CN1-Pad13)") (class "Default")
      (node (ref "CN1") (pin "13") (pinfunction "13_13") (pintype "input+no_connect"))
    )
    (net (code "248") (name "unconnected-(CN2-Pad9)") (class "Default")
      (node (ref "CN2") (pin "9") (pinfunction "9_9") (pintype "input+no_connect"))
    )
    (net (code "249") (name "unconnected-(CN2-Pad10)") (class "Default")
      (node (ref "CN2") (pin "10") (pinfunction "10_10") (pintype "input+no_connect"))
    )
    (net (code "250") (name "unconnected-(CN2-Pad11)") (class "Default")
      (node (ref "CN2") (pin "11") (pinfunction "11_11") (pintype "input+no_connect"))
    )
    (net (code "251") (name "unconnected-(CN2-Pad12)") (class "Default")
      (node (ref "CN2") (pin "12") (pinfunction "12_12") (pintype "input+no_connect"))
    )
    (net (code "252") (name "unconnected-(CN2-Pad13)") (class "Default")
      (node (ref "CN2") (pin "13") (pinfunction "13_13") (pintype "input+no_connect"))
    )
    (net (code "253") (name "unconnected-(CN2-Pad14)") (class "Default")
      (node (ref "CN2") (pin "14") (pinfunction "14_14") (pintype "input+no_connect"))
    )
    (net (code "254") (name "unconnected-(CN2-Pad15)") (class "Default")
      (node (ref "CN2") (pin "15") (pinfunction "15_15") (pintype "input+no_connect"))
    )
    (net (code "255") (name "unconnected-(CN2-Pad16)") (class "Default")
      (node (ref "CN2") (pin "16") (pinfunction "16_16") (pintype "input+no_connect"))
    )
    (net (code "256") (name "unconnected-(CN2-Pad17)") (class "Default")
      (node (ref "CN2") (pin "17") (pinfunction "17_17") (pintype "input+no_connect"))
    )
    (net (code "257") (name "unconnected-(CN2-Pad18)") (class "Default")
      (node (ref "CN2") (pin "18") (pinfunction "18_18") (pintype "input+no_connect"))
    )
    (net (code "258") (name "unconnected-(CN2-Pad22)") (class "Default")
      (node (ref "CN2") (pin "22") (pinfunction "22_22") (pintype "input+no_connect"))
    )
    (net (code "259") (name "unconnected-(CN2-Pad24)") (class "Default")
      (node (ref "CN2") (pin "24") (pinfunction "24_24") (pintype "input+no_connect"))
    )
    (net (code "260") (name "unconnected-(CN2-Pad26)") (class "Default")
      (node (ref "CN2") (pin "26") (pinfunction "26_26") (pintype "input+no_connect"))
    )
    (net (code "261") (name "unconnected-(CN2-Pad28)") (class "Default")
      (node (ref "CN2") (pin "28") (pinfunction "28_28") (pintype "input+no_connect"))
    )
    (net (code "262") (name "unconnected-(U5-NC-PadJ1)") (class "Default")
      (node (ref "U5") (pin "J1") (pinfunction "NC_J1") (pintype "input+no_connect"))
    )
    (net (code "263") (name "unconnected-(U5-NC-PadJ9)") (class "Default")
      (node (ref "U5") (pin "J9") (pinfunction "NC_J9") (pintype "input+no_connect"))
    )
    (net (code "264") (name "unconnected-(U5-NC-PadL1)") (class "Default")
      (node (ref "U5") (pin "L1") (pinfunction "NC_L1") (pintype "input+no_connect"))
    )
    (net (code "265") (name "unconnected-(U5-NC-PadL9)") (class "Default")
      (node (ref "U5") (pin "L9") (pinfunction "NC_L9") (pintype "input+no_connect"))
    )
    (net (code "266") (name "unconnected-(U5-NC-PadM7)") (class "Default")
      (node (ref "U5") (pin "M7") (pinfunction "NC_M7") (pintype "input+no_connect"))
    )
    (net (code "267") (name "unconnected-(U7A-PS_MIO0_500-PadE6)") (class "Default")
      (node (ref "U7") (pin "E6") (pinfunction "PS_MIO0_500_E6") (pintype "input"))
    )
    (net (code "268") (name "unconnected-(U7A-PS_MIO9_500-PadB5)") (class "Default")
      (node (ref "U7") (pin "B5") (pinfunction "PS_MIO9_500_B5") (pintype "input+no_connect"))
    )
    (net (code "269") (name "unconnected-(U7A-PS_MIO10_500-PadE9)") (class "Default")
      (node (ref "U7") (pin "E9") (pinfunction "PS_MIO10_500_E9") (pintype "input+no_connect"))
    )
    (net (code "270") (name "unconnected-(U7A-PS_MIO11_500-PadC6)") (class "Default")
      (node (ref "U7") (pin "C6") (pinfunction "PS_MIO11_500_C6") (pintype "input+no_connect"))
    )
    (net (code "271") (name "unconnected-(U7A-PS_MIO12_500-PadD9)") (class "Default")
      (node (ref "U7") (pin "D9") (pinfunction "PS_MIO12_500_D9") (pintype "input+no_connect"))
    )
    (net (code "272") (name "unconnected-(U7A-PS_MIO13_500-PadE8)") (class "Default")
      (node (ref "U7") (pin "E8") (pinfunction "PS_MIO13_500_E8") (pintype "input+no_connect"))
    )
    (net (code "273") (name "unconnected-(U7A-PS_MIO14_500-PadC5)") (class "Default")
      (node (ref "U7") (pin "C5") (pinfunction "PS_MIO14_500_C5") (pintype "input+no_connect"))
    )
    (net (code "274") (name "unconnected-(U7A-PS_MIO15_500-PadC8)") (class "Default")
      (node (ref "U7") (pin "C8") (pinfunction "PS_MIO15_500_C8") (pintype "input+no_connect"))
    )
    (net (code "275") (name "unconnected-(U7B-PS_MIO28_501-PadC16)") (class "Default")
      (node (ref "U7") (pin "C16") (pinfunction "PS_MIO28_501_C16") (pintype "input"))
    )
    (net (code "276") (name "unconnected-(U7B-PS_MIO29_501-PadC13)") (class "Default")
      (node (ref "U7") (pin "C13") (pinfunction "PS_MIO29_501_C13") (pintype "input"))
    )
    (net (code "277") (name "unconnected-(U7B-PS_MIO30_501-PadC15)") (class "Default")
      (node (ref "U7") (pin "C15") (pinfunction "PS_MIO30_501_C15") (pintype "input"))
    )
    (net (code "278") (name "unconnected-(U7B-PS_MIO31_501-PadE16)") (class "Default")
      (node (ref "U7") (pin "E16") (pinfunction "PS_MIO31_501_E16") (pintype "input"))
    )
    (net (code "279") (name "unconnected-(U7B-PS_MIO32_501-PadA14)") (class "Default")
      (node (ref "U7") (pin "A14") (pinfunction "PS_MIO32_501_A14") (pintype "input"))
    )
    (net (code "280") (name "unconnected-(U7B-PS_MIO33_501-PadD15)") (class "Default")
      (node (ref "U7") (pin "D15") (pinfunction "PS_MIO33_501_D15") (pintype "input"))
    )
    (net (code "281") (name "unconnected-(U7B-PS_MIO34_501-PadA12)") (class "Default")
      (node (ref "U7") (pin "A12") (pinfunction "PS_MIO34_501_A12") (pintype "input"))
    )
    (net (code "282") (name "unconnected-(U7B-PS_MIO35_501-PadF12)") (class "Default")
      (node (ref "U7") (pin "F12") (pinfunction "PS_MIO35_501_F12") (pintype "input"))
    )
    (net (code "283") (name "unconnected-(U7B-PS_MIO36_501-PadA11)") (class "Default")
      (node (ref "U7") (pin "A11") (pinfunction "PS_MIO36_501_A11") (pintype "input"))
    )
    (net (code "284") (name "unconnected-(U7B-PS_MIO37_501-PadA10)") (class "Default")
      (node (ref "U7") (pin "A10") (pinfunction "PS_MIO37_501_A10") (pintype "input"))
    )
    (net (code "285") (name "unconnected-(U7B-PS_MIO38_501-PadE13)") (class "Default")
      (node (ref "U7") (pin "E13") (pinfunction "PS_MIO38_501_E13") (pintype "input"))
    )
    (net (code "286") (name "unconnected-(U7B-PS_MIO39_501-PadC18)") (class "Default")
      (node (ref "U7") (pin "C18") (pinfunction "PS_MIO39_501_C18") (pintype "input"))
    )
    (net (code "287") (name "unconnected-(U7B-PS_MIO46_501-PadD16)") (class "Default")
      (node (ref "U7") (pin "D16") (pinfunction "PS_MIO46_501_D16") (pintype "input+no_connect"))
    )
    (net (code "288") (name "unconnected-(U7B-PS_MIO50_501-PadB13)") (class "Default")
      (node (ref "U7") (pin "B13") (pinfunction "PS_MIO50_501_B13") (pintype "input"))
    )
    (net (code "289") (name "unconnected-(U7B-PS_MIO51_501-PadB9)") (class "Default")
      (node (ref "U7") (pin "B9") (pinfunction "PS_MIO51_501_B9") (pintype "input"))
    )
    (net (code "290") (name "unconnected-(U7B-PS_MIO52_501-PadC10)") (class "Default")
      (node (ref "U7") (pin "C10") (pinfunction "PS_MIO52_501_C10") (pintype "input"))
    )
    (net (code "291") (name "unconnected-(U7B-PS_MIO53_501-PadC11)") (class "Default")
      (node (ref "U7") (pin "C11") (pinfunction "PS_MIO53_501_C11") (pintype "input"))
    )
    (net (code "292") (name "unconnected-(U7C-NC-PadT5)") (class "Default")
      (node (ref "U7") (pin "T5") (pinfunction "NC_T5") (pintype "input+no_connect"))
    )
    (net (code "293") (name "unconnected-(U7C-NC-PadT9)") (class "Default")
      (node (ref "U7") (pin "T9") (pinfunction "NC_T9") (pintype "input+no_connect"))
    )
    (net (code "294") (name "unconnected-(U7C-NC-PadU5)") (class "Default")
      (node (ref "U7") (pin "U5") (pinfunction "NC_U5") (pintype "input+no_connect"))
    )
    (net (code "295") (name "unconnected-(U7C-NC-PadU7)") (class "Default")
      (node (ref "U7") (pin "U7") (pinfunction "NC_U7") (pintype "input+no_connect"))
    )
    (net (code "296") (name "unconnected-(U7C-NC-PadU8)") (class "Default")
      (node (ref "U7") (pin "U8") (pinfunction "NC_U8") (pintype "input+no_connect"))
    )
    (net (code "297") (name "unconnected-(U7C-NC-PadU9)") (class "Default")
      (node (ref "U7") (pin "U9") (pinfunction "NC_U9") (pintype "input+no_connect"))
    )
    (net (code "298") (name "unconnected-(U7C-NC-PadU10)") (class "Default")
      (node (ref "U7") (pin "U10") (pinfunction "NC_U10") (pintype "input+no_connect"))
    )
    (net (code "299") (name "unconnected-(U7C-NC-PadV5)") (class "Default")
      (node (ref "U7") (pin "V5") (pinfunction "NC_V5") (pintype "input+no_connect"))
    )
    (net (code "300") (name "unconnected-(U7C-NC-PadV6)") (class "Default")
      (node (ref "U7") (pin "V6") (pinfunction "NC_V6") (pintype "input+no_connect"))
    )
    (net (code "301") (name "unconnected-(U7C-NC-PadV7)") (class "Default")
      (node (ref "U7") (pin "V7") (pinfunction "NC_V7") (pintype "input+no_connect"))
    )
    (net (code "302") (name "unconnected-(U7C-NC-PadV8)") (class "Default")
      (node (ref "U7") (pin "V8") (pinfunction "NC_V8") (pintype "input+no_connect"))
    )
    (net (code "303") (name "unconnected-(U7C-NC-PadV10)") (class "Default")
      (node (ref "U7") (pin "V10") (pinfunction "NC_V10") (pintype "input+no_connect"))
    )
    (net (code "304") (name "unconnected-(U7C-NC-PadV11)") (class "Default")
      (node (ref "U7") (pin "V11") (pinfunction "NC_V11") (pintype "input+no_connect"))
    )
    (net (code "305") (name "unconnected-(U7C-NC-PadW6)") (class "Default")
      (node (ref "U7") (pin "W6") (pinfunction "NC_W6") (pintype "input+no_connect"))
    )
    (net (code "306") (name "unconnected-(U7C-NC-PadW8)") (class "Default")
      (node (ref "U7") (pin "W8") (pinfunction "NC_W8") (pintype "input+no_connect"))
    )
    (net (code "307") (name "unconnected-(U7C-NC-PadW9)") (class "Default")
      (node (ref "U7") (pin "W9") (pinfunction "NC_W9") (pintype "input+no_connect"))
    )
    (net (code "308") (name "unconnected-(U7C-NC-PadW10)") (class "Default")
      (node (ref "U7") (pin "W10") (pinfunction "NC_W10") (pintype "input+no_connect"))
    )
    (net (code "309") (name "unconnected-(U7C-NC-PadW11)") (class "Default")
      (node (ref "U7") (pin "W11") (pinfunction "NC_W11") (pintype "input+no_connect"))
    )
    (net (code "310") (name "unconnected-(U7C-NC-PadY6)") (class "Default")
      (node (ref "U7") (pin "Y6") (pinfunction "NC_Y6") (pintype "input+no_connect"))
    )
    (net (code "311") (name "unconnected-(U7C-NC-PadY7)") (class "Default")
      (node (ref "U7") (pin "Y7") (pinfunction "NC_Y7") (pintype "input+no_connect"))
    )
    (net (code "312") (name "unconnected-(U7C-NC-PadY8)") (class "Default")
      (node (ref "U7") (pin "Y8") (pinfunction "NC_Y8") (pintype "input+no_connect"))
    )
    (net (code "313") (name "unconnected-(U7C-NC-PadY9)") (class "Default")
      (node (ref "U7") (pin "Y9") (pinfunction "NC_Y9") (pintype "input+no_connect"))
    )
    (net (code "314") (name "unconnected-(U7C-NC-PadY11)") (class "Default")
      (node (ref "U7") (pin "Y11") (pinfunction "NC_Y11") (pintype "input+no_connect"))
    )
    (net (code "315") (name "unconnected-(U7C-NC-PadY12)") (class "Default")
      (node (ref "U7") (pin "Y12") (pinfunction "NC_Y12") (pintype "input+no_connect"))
    )
    (net (code "316") (name "unconnected-(U7C-NC-PadY13)") (class "Default")
      (node (ref "U7") (pin "Y13") (pinfunction "NC_Y13") (pintype "input+no_connect"))
    )
    (net (code "317") (name "unconnected-(U7C-VN_0-PadL10)") (class "Default")
      (node (ref "U7") (pin "L10") (pinfunction "VN_0_L10") (pintype "input+no_connect"))
    )
    (net (code "318") (name "unconnected-(U7C-VP_0-PadK9)") (class "Default")
      (node (ref "U7") (pin "K9") (pinfunction "VP_0_K9") (pintype "input+no_connect"))
    )
    (net (code "319") (name "unconnected-(U7E-PS_DDR_DM2_502-PadT1)") (class "Default")
      (node (ref "U7") (pin "T1") (pinfunction "PS_DDR_DM2_502_T1") (pintype "input+no_connect"))
    )
    (net (code "320") (name "unconnected-(U7E-PS_DDR_DM3_502-PadY1)") (class "Default")
      (node (ref "U7") (pin "Y1") (pinfunction "PS_DDR_DM3_502_Y1") (pintype "input+no_connect"))
    )
    (net (code "321") (name "unconnected-(U7E-PS_DDR_DQ16_502-PadP1)") (class "Default")
      (node (ref "U7") (pin "P1") (pinfunction "PS_DDR_DQ16_502_P1") (pintype "input+no_connect"))
    )
    (net (code "322") (name "unconnected-(U7E-PS_DDR_DQ17_502-PadP3)") (class "Default")
      (node (ref "U7") (pin "P3") (pinfunction "PS_DDR_DQ17_502_P3") (pintype "input+no_connect"))
    )
    (net (code "323") (name "unconnected-(U7E-PS_DDR_DQ18_502-PadR3)") (class "Default")
      (node (ref "U7") (pin "R3") (pinfunction "PS_DDR_DQ18_502_R3") (pintype "input+no_connect"))
    )
    (net (code "324") (name "unconnected-(U7E-PS_DDR_DQ19_502-PadR1)") (class "Default")
      (node (ref "U7") (pin "R1") (pinfunction "PS_DDR_DQ19_502_R1") (pintype "input+no_connect"))
    )
    (net (code "325") (name "unconnected-(U7E-PS_DDR_DQ20_502-PadT4)") (class "Default")
      (node (ref "U7") (pin "T4") (pinfunction "PS_DDR_DQ20_502_T4") (pintype "input+no_connect"))
    )
    (net (code "326") (name "unconnected-(U7E-PS_DDR_DQ21_502-PadU4)") (class "Default")
      (node (ref "U7") (pin "U4") (pinfunction "PS_DDR_DQ21_502_U4") (pintype "input+no_connect"))
    )
    (net (code "327") (name "unconnected-(U7E-PS_DDR_DQ22_502-PadU2)") (class "Default")
      (node (ref "U7") (pin "U2") (pinfunction "PS_DDR_DQ22_502_U2") (pintype "input+no_connect"))
    )
    (net (code "328") (name "unconnected-(U7E-PS_DDR_DQ23_502-PadU3)") (class "Default")
      (node (ref "U7") (pin "U3") (pinfunction "PS_DDR_DQ23_502_U3") (pintype "input+no_connect"))
    )
    (net (code "329") (name "unconnected-(U7E-PS_DDR_DQ24_502-PadV1)") (class "Default")
      (node (ref "U7") (pin "V1") (pinfunction "PS_DDR_DQ24_502_V1") (pintype "input+no_connect"))
    )
    (net (code "330") (name "unconnected-(U7E-PS_DDR_DQ25_502-PadY3)") (class "Default")
      (node (ref "U7") (pin "Y3") (pinfunction "PS_DDR_DQ25_502_Y3") (pintype "input+no_connect"))
    )
    (net (code "331") (name "unconnected-(U7E-PS_DDR_DQ26_502-PadW1)") (class "Default")
      (node (ref "U7") (pin "W1") (pinfunction "PS_DDR_DQ26_502_W1") (pintype "input+no_connect"))
    )
    (net (code "332") (name "unconnected-(U7E-PS_DDR_DQ27_502-PadY4)") (class "Default")
      (node (ref "U7") (pin "Y4") (pinfunction "PS_DDR_DQ27_502_Y4") (pintype "input+no_connect"))
    )
    (net (code "333") (name "unconnected-(U7E-PS_DDR_DQ28_502-PadY2)") (class "Default")
      (node (ref "U7") (pin "Y2") (pinfunction "PS_DDR_DQ28_502_Y2") (pintype "input+no_connect"))
    )
    (net (code "334") (name "unconnected-(U7E-PS_DDR_DQ29_502-PadW3)") (class "Default")
      (node (ref "U7") (pin "W3") (pinfunction "PS_DDR_DQ29_502_W3") (pintype "input+no_connect"))
    )
    (net (code "335") (name "unconnected-(U7E-PS_DDR_DQ30_502-PadV2)") (class "Default")
      (node (ref "U7") (pin "V2") (pinfunction "PS_DDR_DQ30_502_V2") (pintype "input+no_connect"))
    )
    (net (code "336") (name "unconnected-(U7E-PS_DDR_DQ31_502-PadV3)") (class "Default")
      (node (ref "U7") (pin "V3") (pinfunction "PS_DDR_DQ31_502_V3") (pintype "input+no_connect"))
    )
    (net (code "337") (name "unconnected-(U7E-PS_DDR_DQS_N2_502-PadT2)") (class "Default")
      (node (ref "U7") (pin "T2") (pinfunction "PS_DDR_DQS_N2_502_T2") (pintype "input+no_connect"))
    )
    (net (code "338") (name "unconnected-(U7E-PS_DDR_DQS_N3_502-PadW4)") (class "Default")
      (node (ref "U7") (pin "W4") (pinfunction "PS_DDR_DQS_N3_502_W4") (pintype "input+no_connect"))
    )
    (net (code "339") (name "unconnected-(U7E-PS_DDR_DQS_P2_502-PadR2)") (class "Default")
      (node (ref "U7") (pin "R2") (pinfunction "PS_DDR_DQS_P2_502_R2") (pintype "input+no_connect"))
    )
    (net (code "340") (name "unconnected-(U7E-PS_DDR_DQS_P3_502-PadW5)") (class "Default")
      (node (ref "U7") (pin "W5") (pinfunction "PS_DDR_DQS_P3_502_W5") (pintype "input+no_connect"))
    )
    (net (code "341") (name "unconnected-(U8-CLKB1-Pad13)") (class "Default")
      (node (ref "U8") (pin "13") (pinfunction "CLKB1_13") (pintype "input+no_connect"))
    )
    (net (code "342") (name "unconnected-(U8-CMDB1-Pad12)") (class "Default")
      (node (ref "U8") (pin "12") (pinfunction "CMDB1_12") (pintype "input+no_connect"))
    )
    (net (code "343") (name "unconnected-(U8-DAT0B1-Pad14)") (class "Default")
      (node (ref "U8") (pin "14") (pinfunction "DAT0B1_14") (pintype "input+no_connect"))
    )
    (net (code "344") (name "unconnected-(U8-DAT1B1-Pad15)") (class "Default")
      (node (ref "U8") (pin "15") (pinfunction "DAT1B1_15") (pintype "input+no_connect"))
    )
    (net (code "345") (name "unconnected-(U8-DAT2B1-Pad8)") (class "Default")
      (node (ref "U8") (pin "8") (pinfunction "DAT2B1_8") (pintype "input+no_connect"))
    )
    (net (code "346") (name "unconnected-(U8-DAT3B1-Pad10)") (class "Default")
      (node (ref "U8") (pin "10") (pinfunction "DAT3B1_10") (pintype "input+no_connect"))
    )
    (net (code "347") (name "unconnected-(U9-ACT#-Pad10)") (class "Default")
      (node (ref "U9") (pin "10") (pinfunction "ACT#_10") (pintype "unspecified+no_connect"))
    )
    (net (code "348") (name "unconnected-(U9-CTS-Pad15)") (class "Default")
      (node (ref "U9") (pin "15") (pinfunction "CTS_15") (pintype "unspecified+no_connect"))
    )
    (net (code "349") (name "unconnected-(U9-DCD-Pad11)") (class "Default")
      (node (ref "U9") (pin "11") (pinfunction "DCD_11") (pintype "unspecified+no_connect"))
    )
    (net (code "350") (name "unconnected-(U9-DSR-Pad14)") (class "Default")
      (node (ref "U9") (pin "14") (pinfunction "DSR_14") (pintype "unspecified+no_connect"))
    )
    (net (code "351") (name "unconnected-(U9-DTRTNOW-Pad12)") (class "Default")
      (node (ref "U9") (pin "12") (pinfunction "DTRTNOW_12") (pintype "unspecified+no_connect"))
    )
    (net (code "352") (name "unconnected-(U9-RI-Pad16)") (class "Default")
      (node (ref "U9") (pin "16") (pinfunction "RI_16") (pintype "unspecified+no_connect"))
    )
    (net (code "353") (name "unconnected-(U9-RTS-Pad13)") (class "Default")
      (node (ref "U9") (pin "13") (pinfunction "RTS_13") (pintype "unspecified+no_connect"))
    )
    (net (code "354") (name "unconnected-(U11-DOUT-Pad2)") (class "Default")
      (node (ref "U11") (pin "2") (pinfunction "DOUT_2") (pintype "input+no_connect"))
    )
    (net (code "355") (name "unconnected-(USB1-SBU1-PadA8)") (class "Default")
      (node (ref "USB1") (pin "A8") (pinfunction "SBU1_A8") (pintype "input+no_connect"))
    )
    (net (code "356") (name "unconnected-(USB1-SBU2-PadB8)") (class "Default")
      (node (ref "USB1") (pin "B8") (pinfunction "SBU2_B8") (pintype "input+no_connect"))
    )
    (net (code "357") (name "unconnected-(X1-ST#-Pad1)") (class "Default")
      (node (ref "X1") (pin "1") (pinfunction "ST#_1") (pintype "input+no_connect"))
    )
    (net (code "358") (name "unconnected-(X2-E{slash}D-Pad1)") (class "Default")
      (node (ref "X2") (pin "1") (pinfunction "E/D_1") (pintype "unspecified+no_connect"))
    )
  )
)
